# 0_1.net
KiCad netlist of a schematic drawn in EAGLE
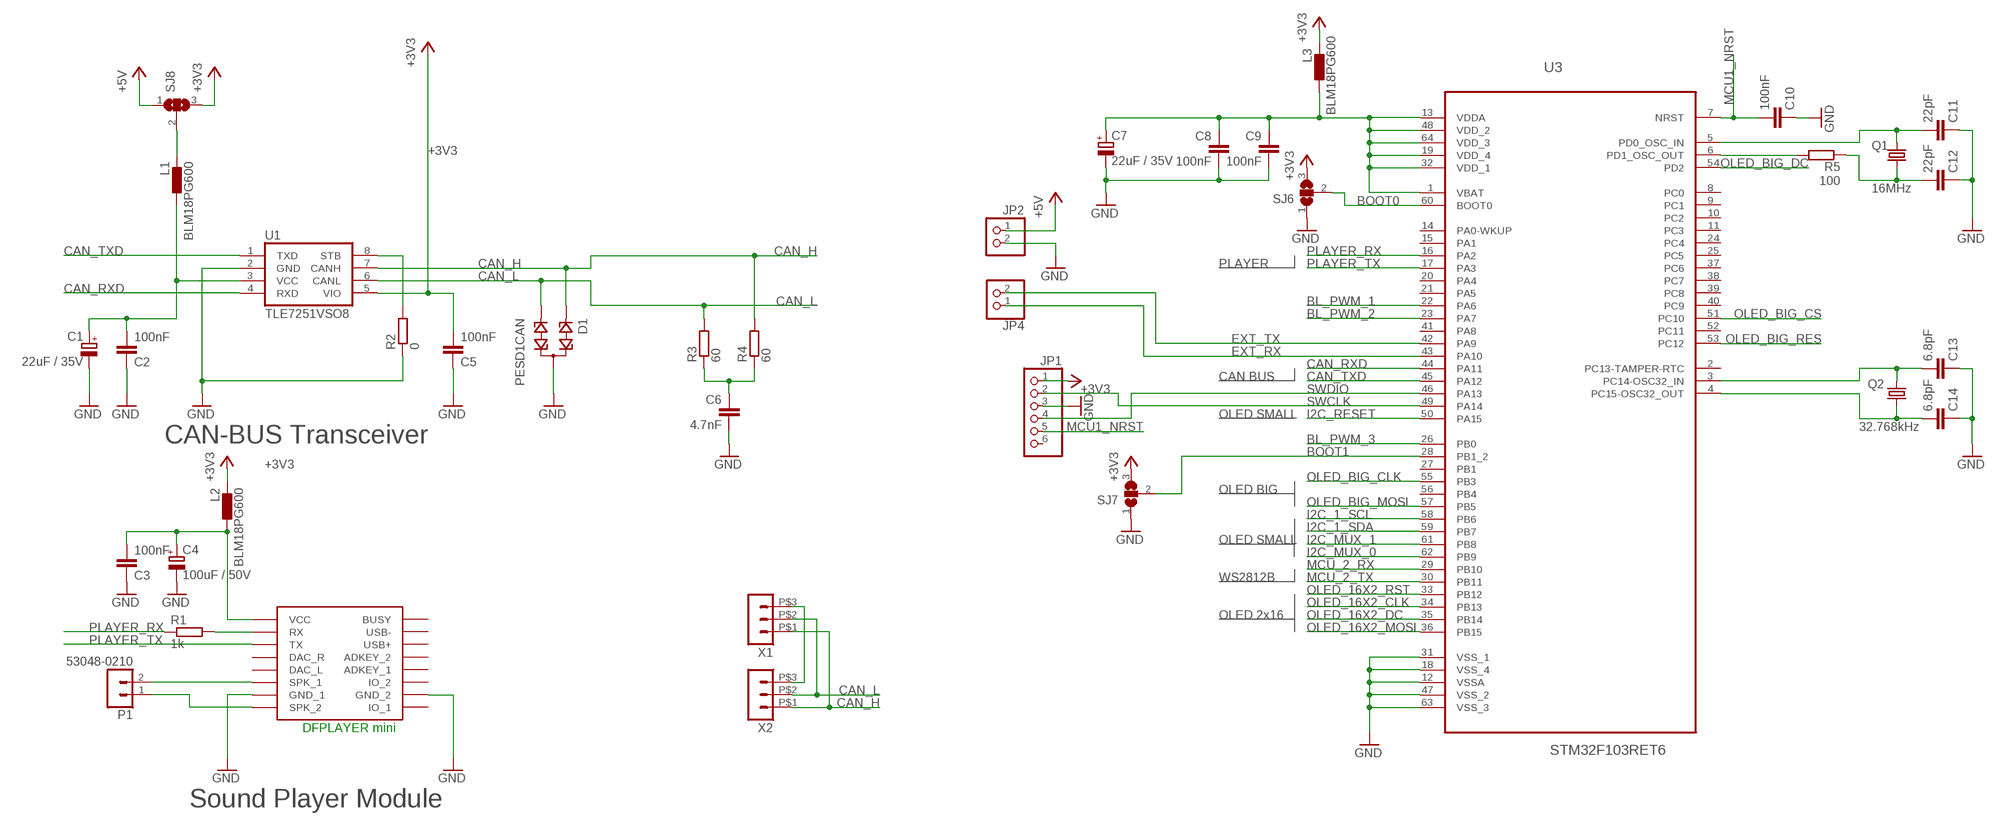
[diagram p0: schematic, sheet 1]
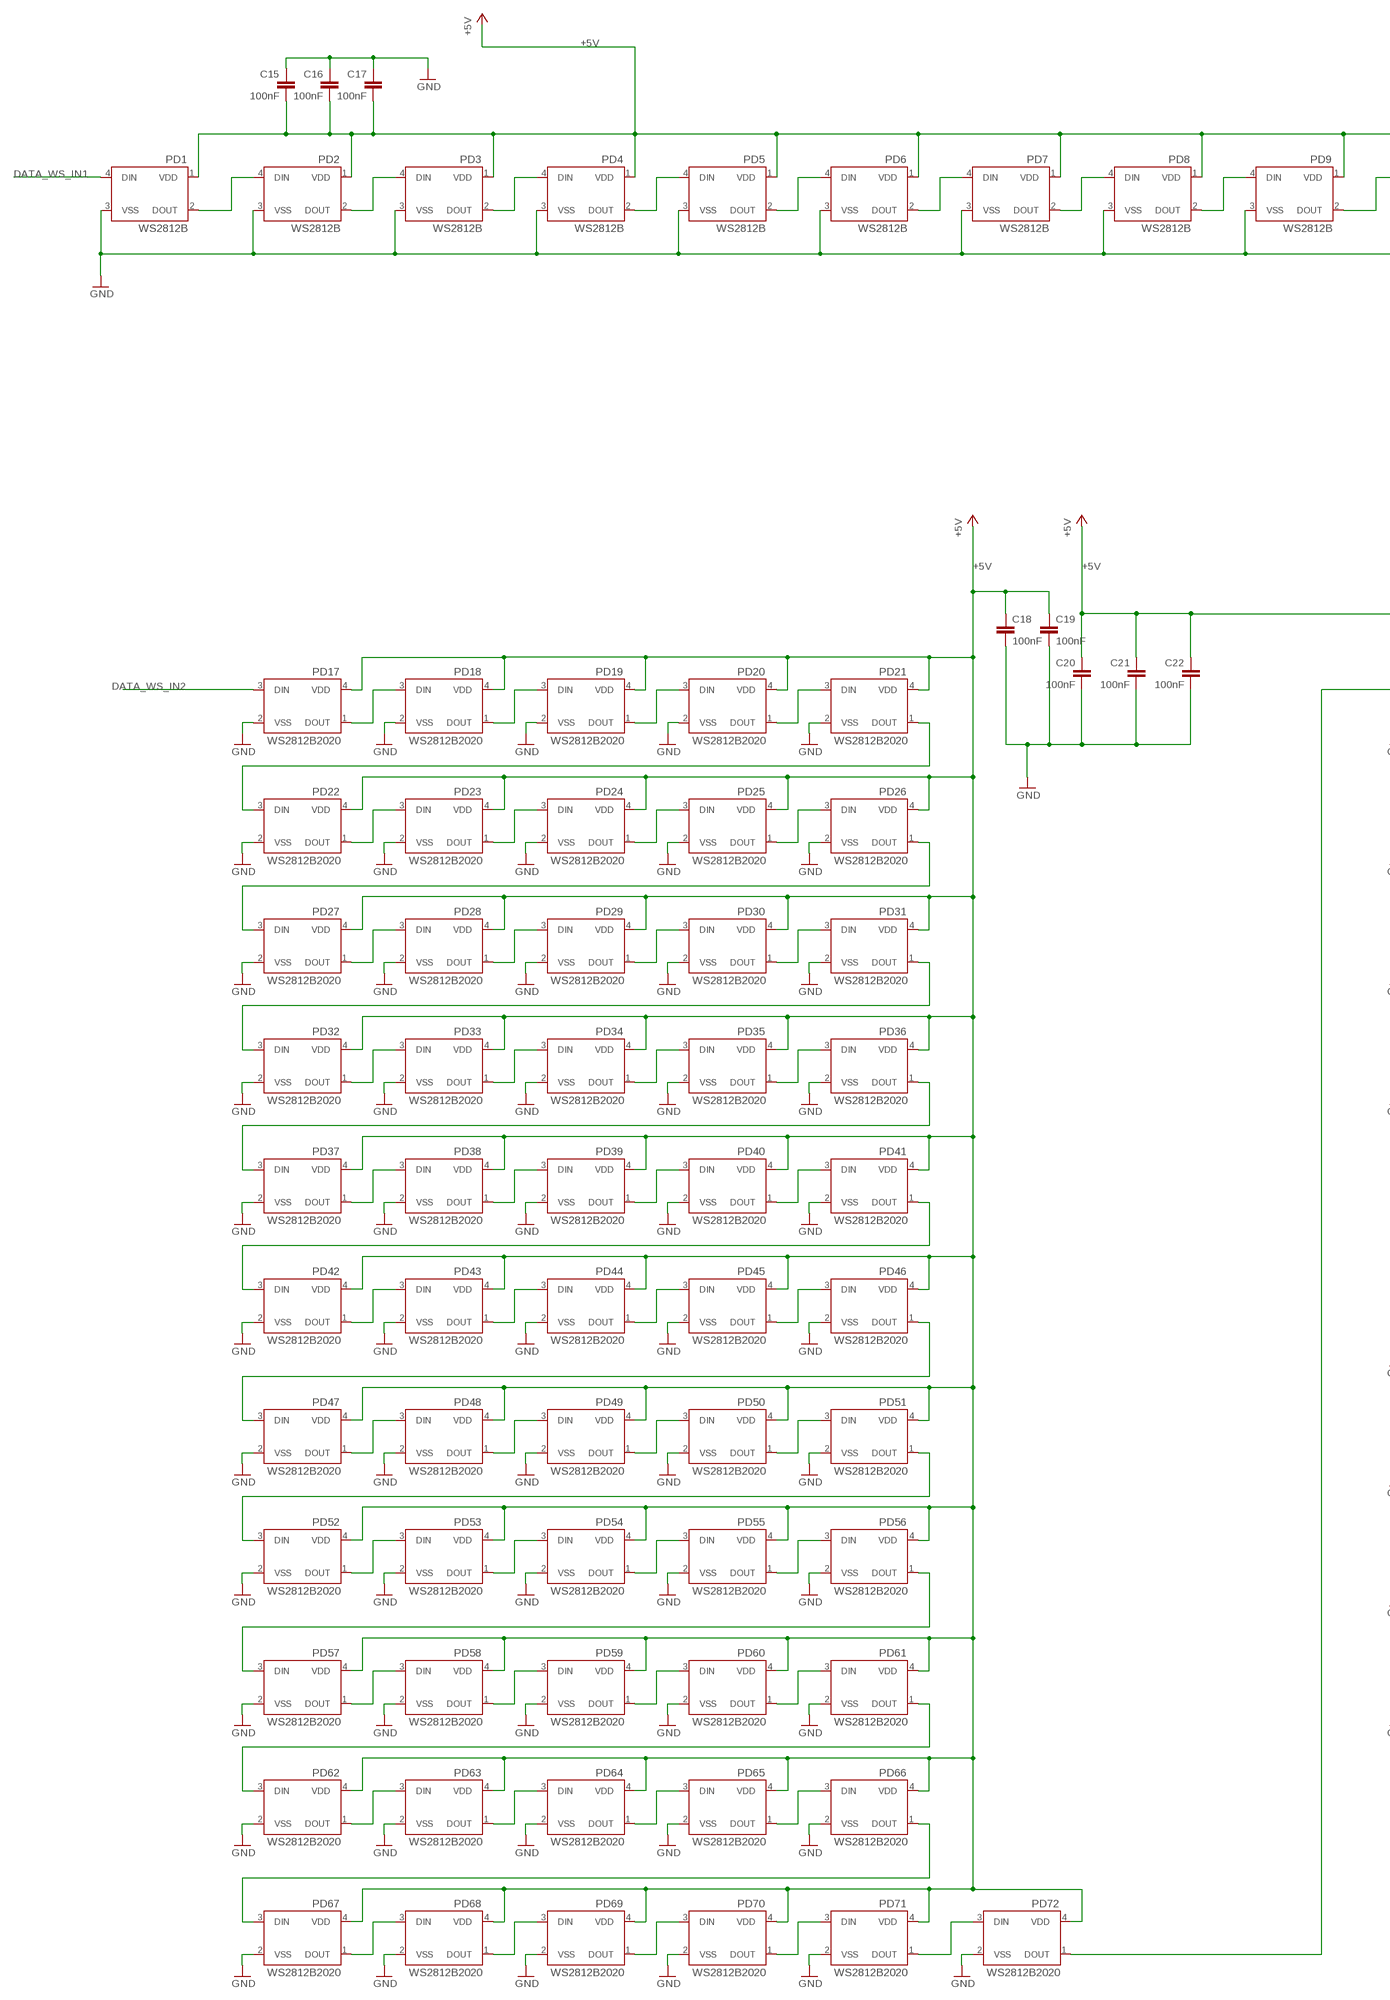
[diagram p1: schematic, sheet 2, part 1 of 2]
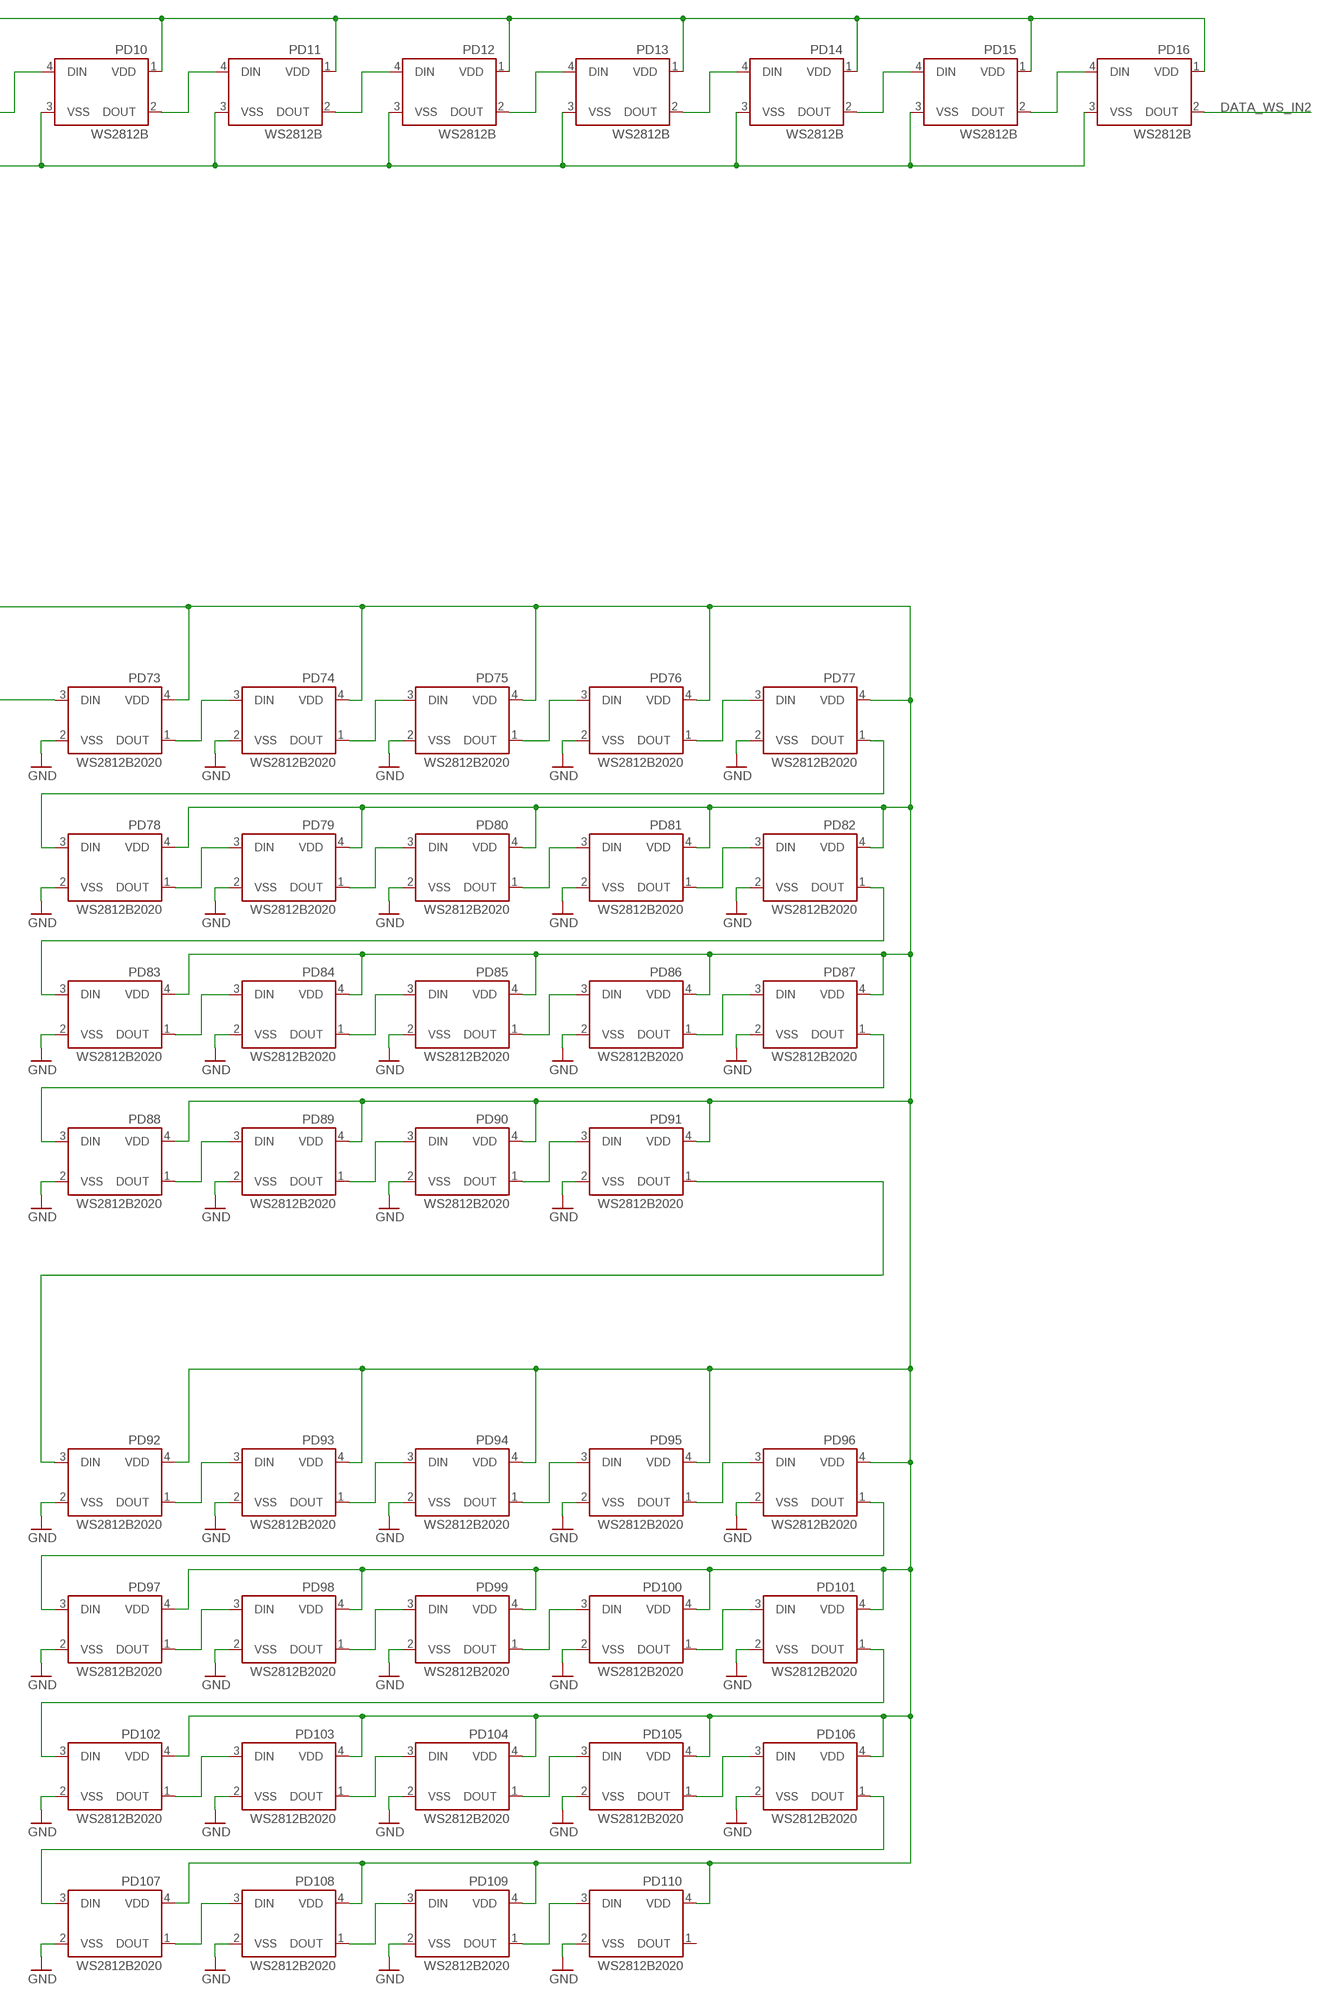
[diagram p2: schematic, sheet 2, part 2 of 2]
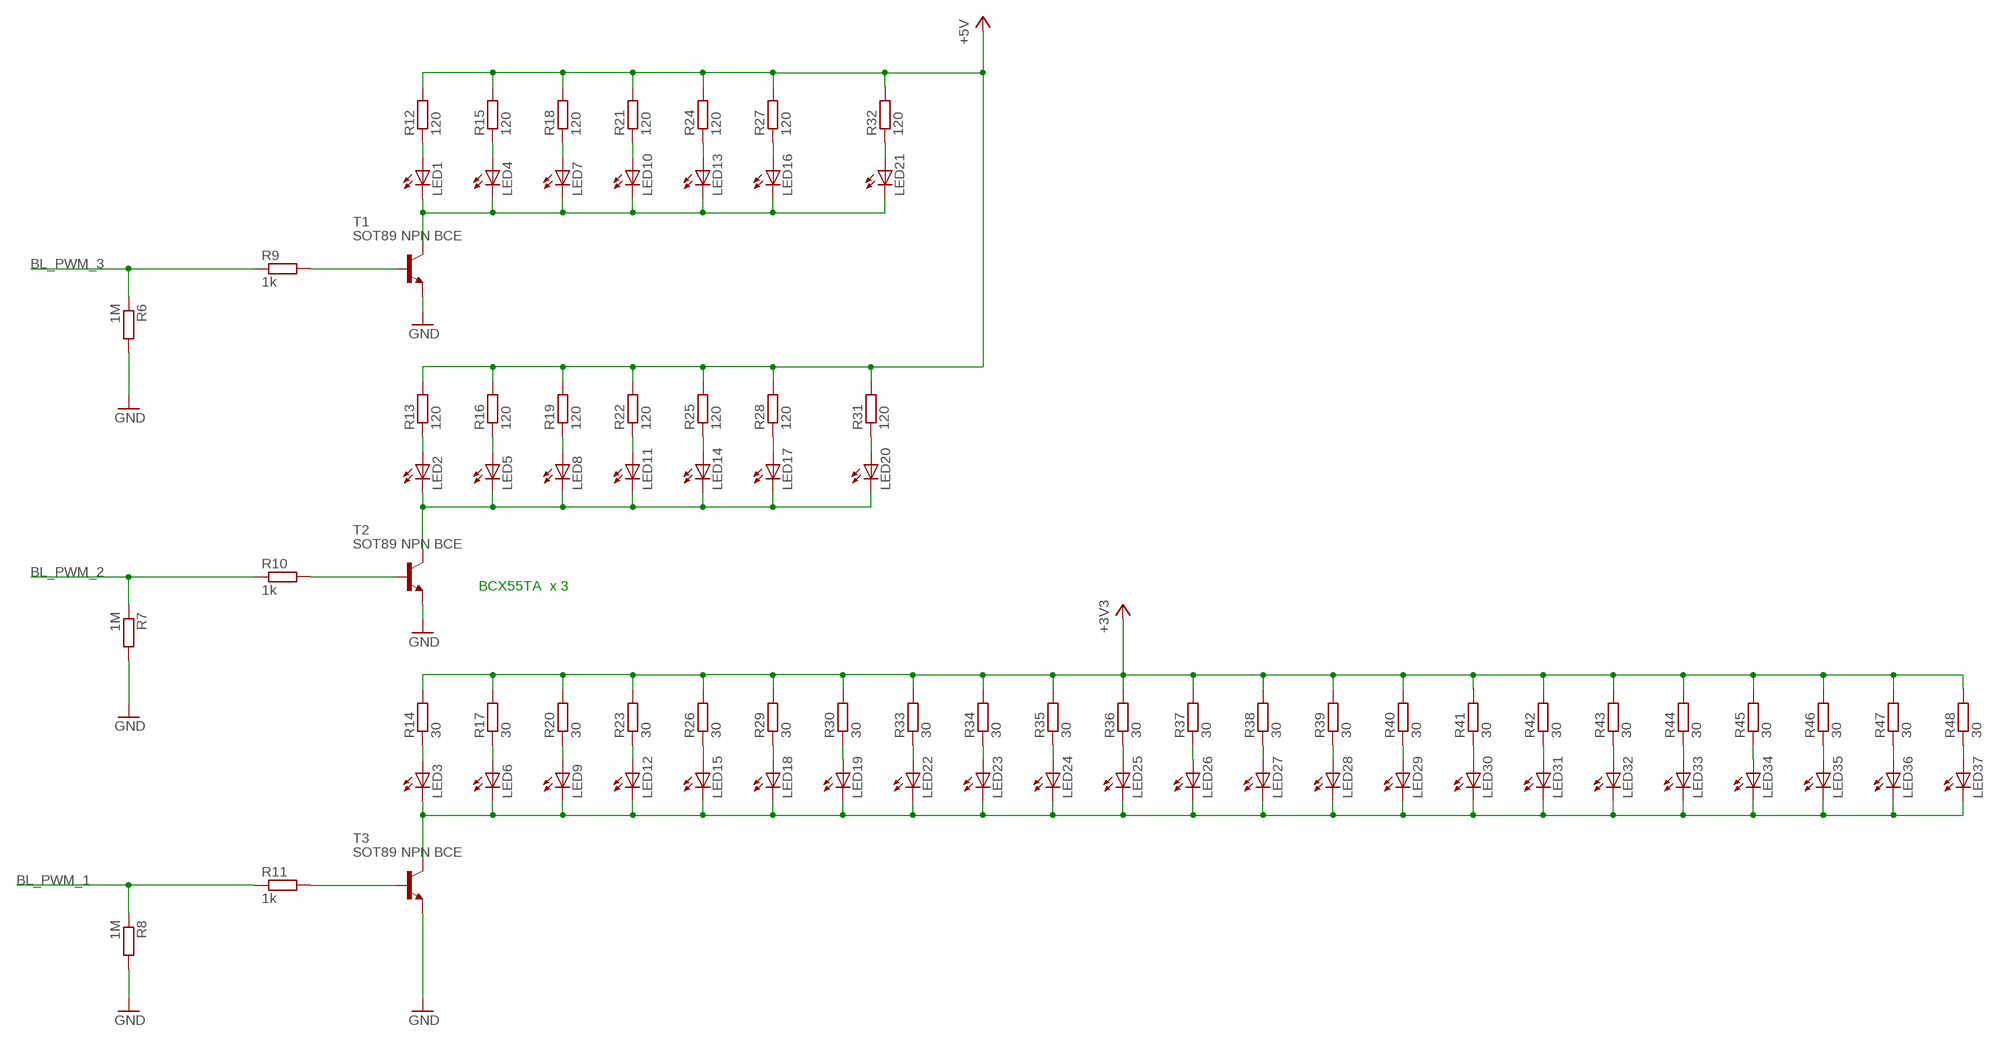
[diagram p3: schematic, sheet 3]
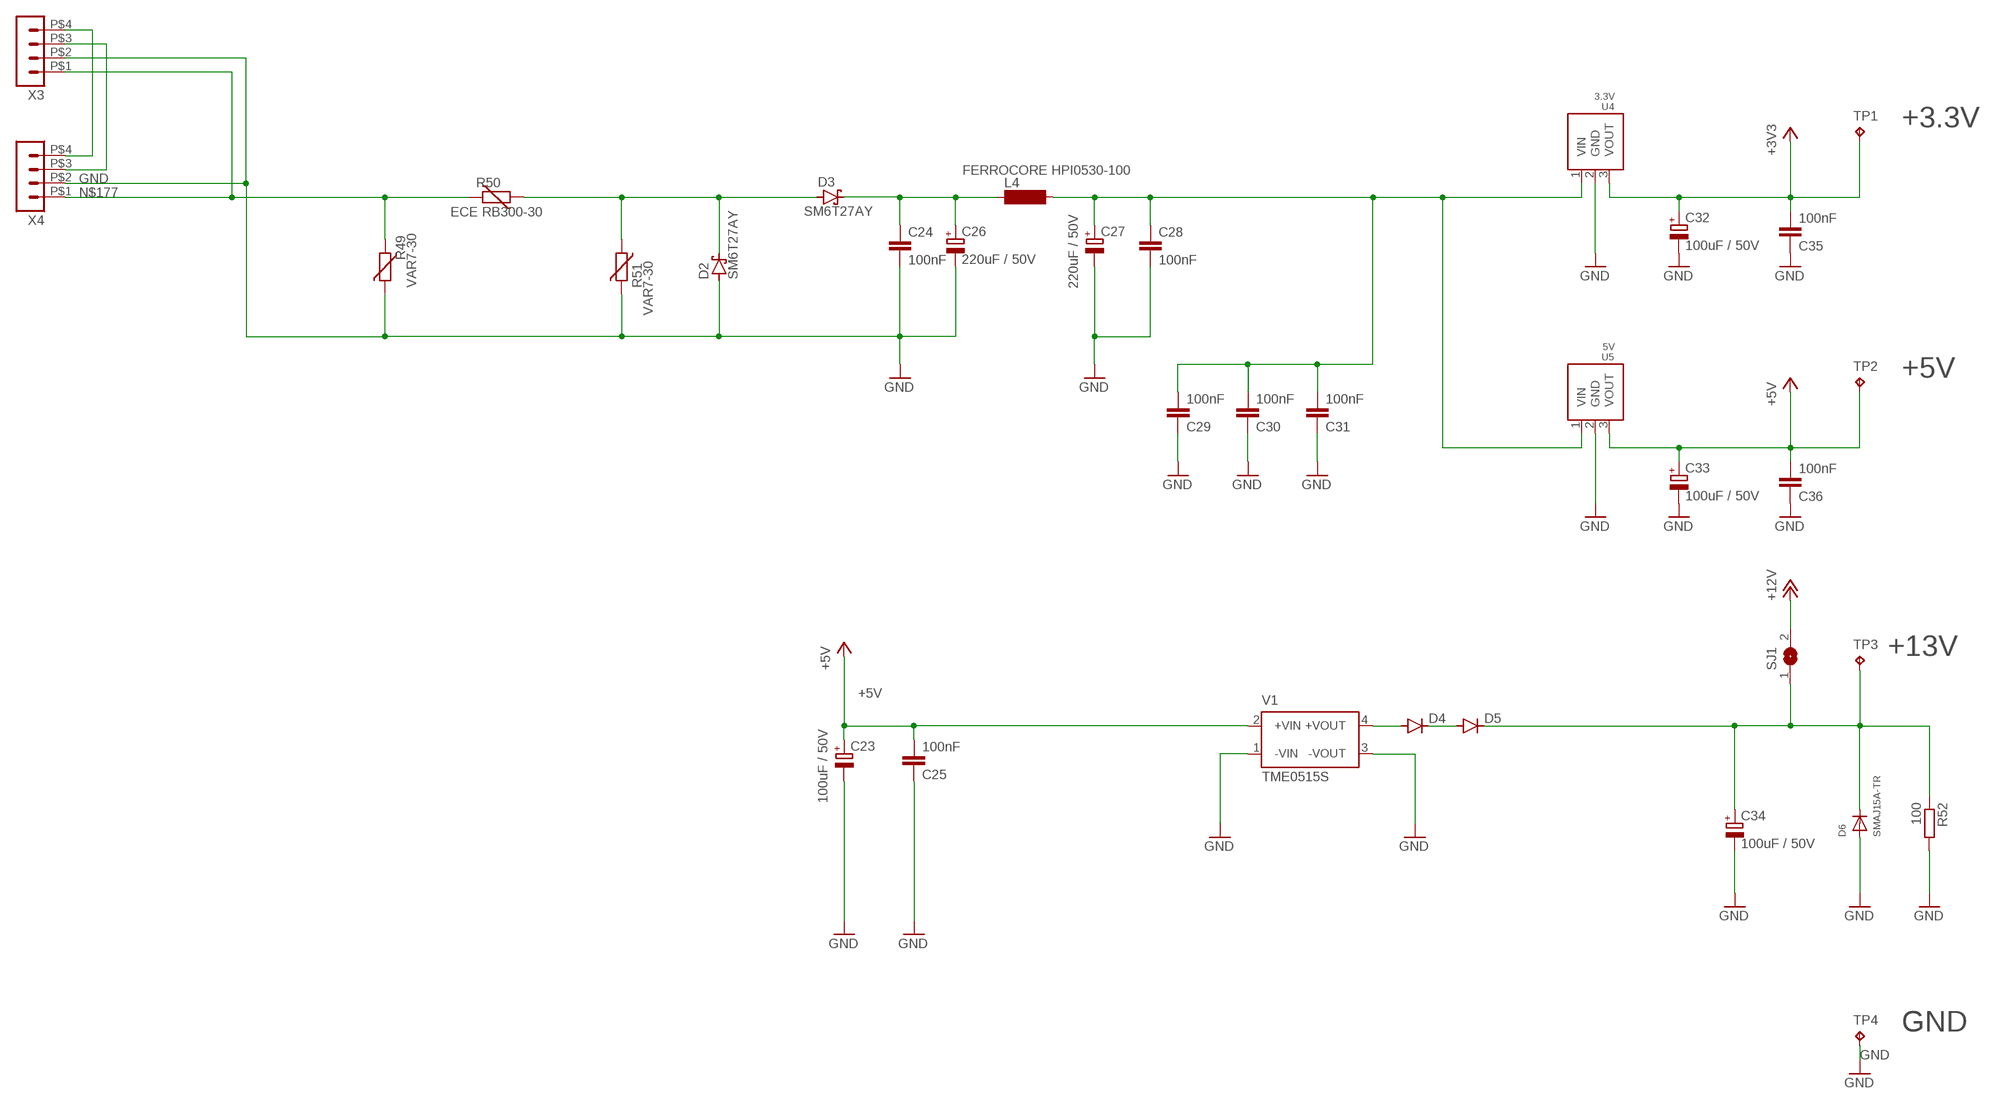
[diagram p4: schematic, sheet 4]
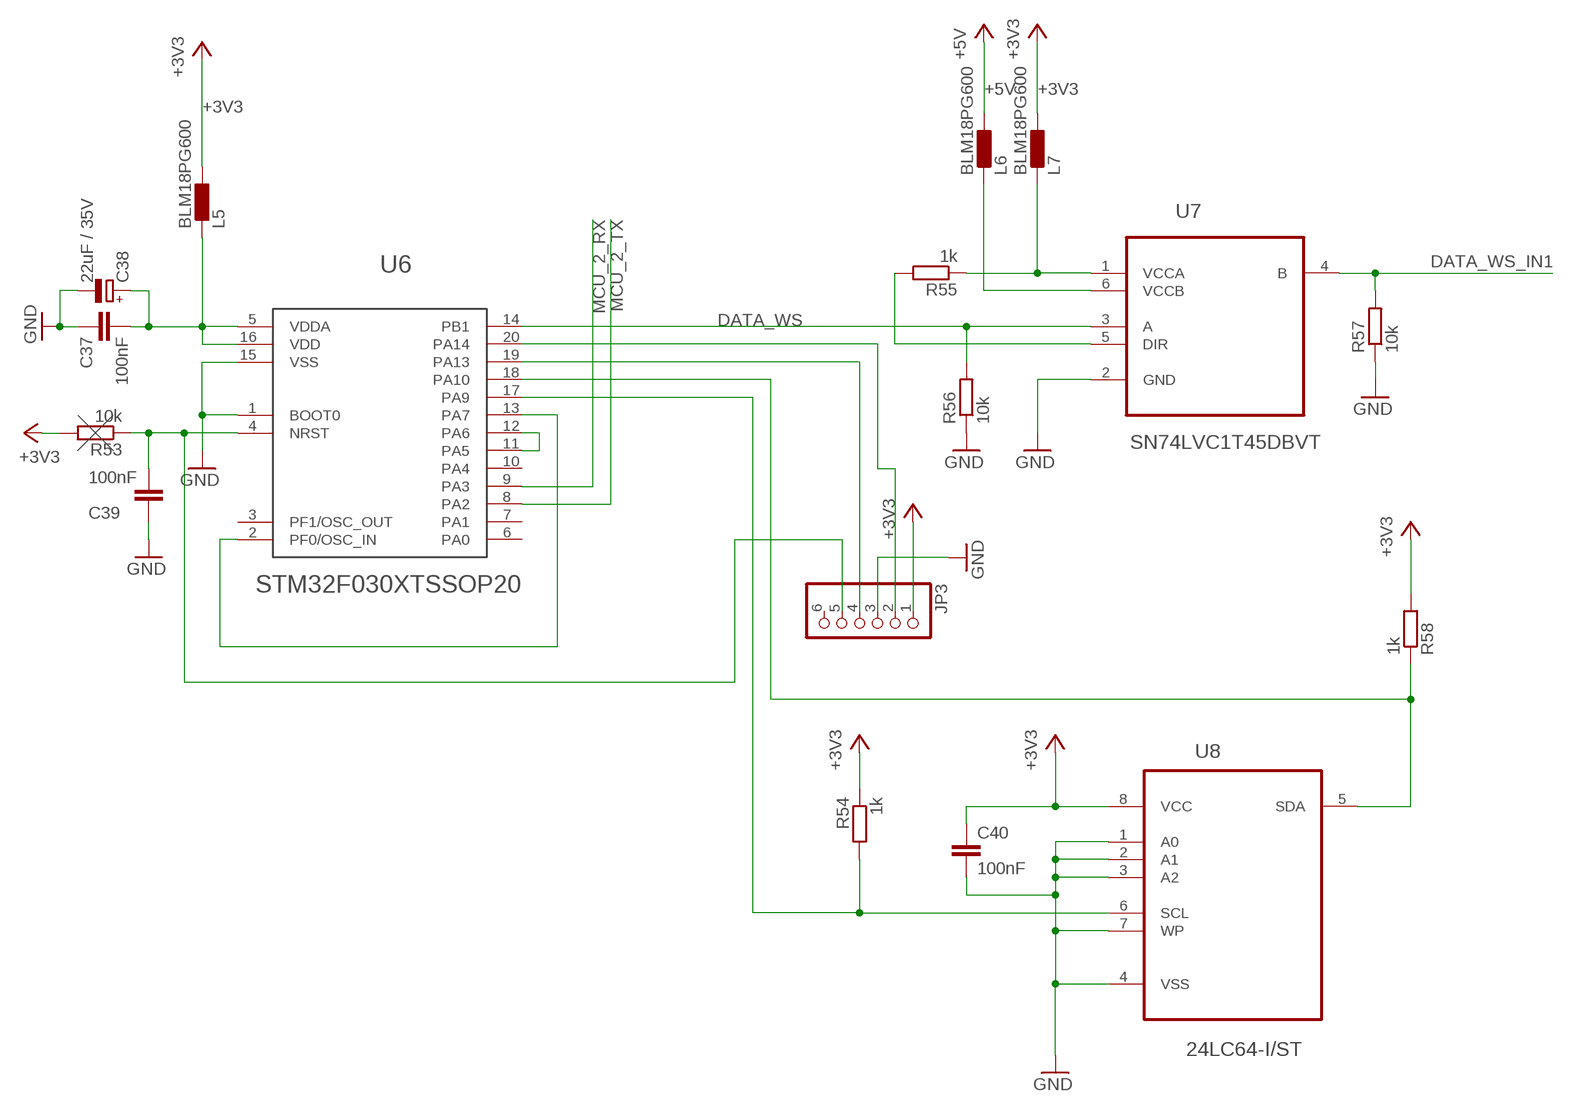
[diagram p5: schematic, sheet 5]
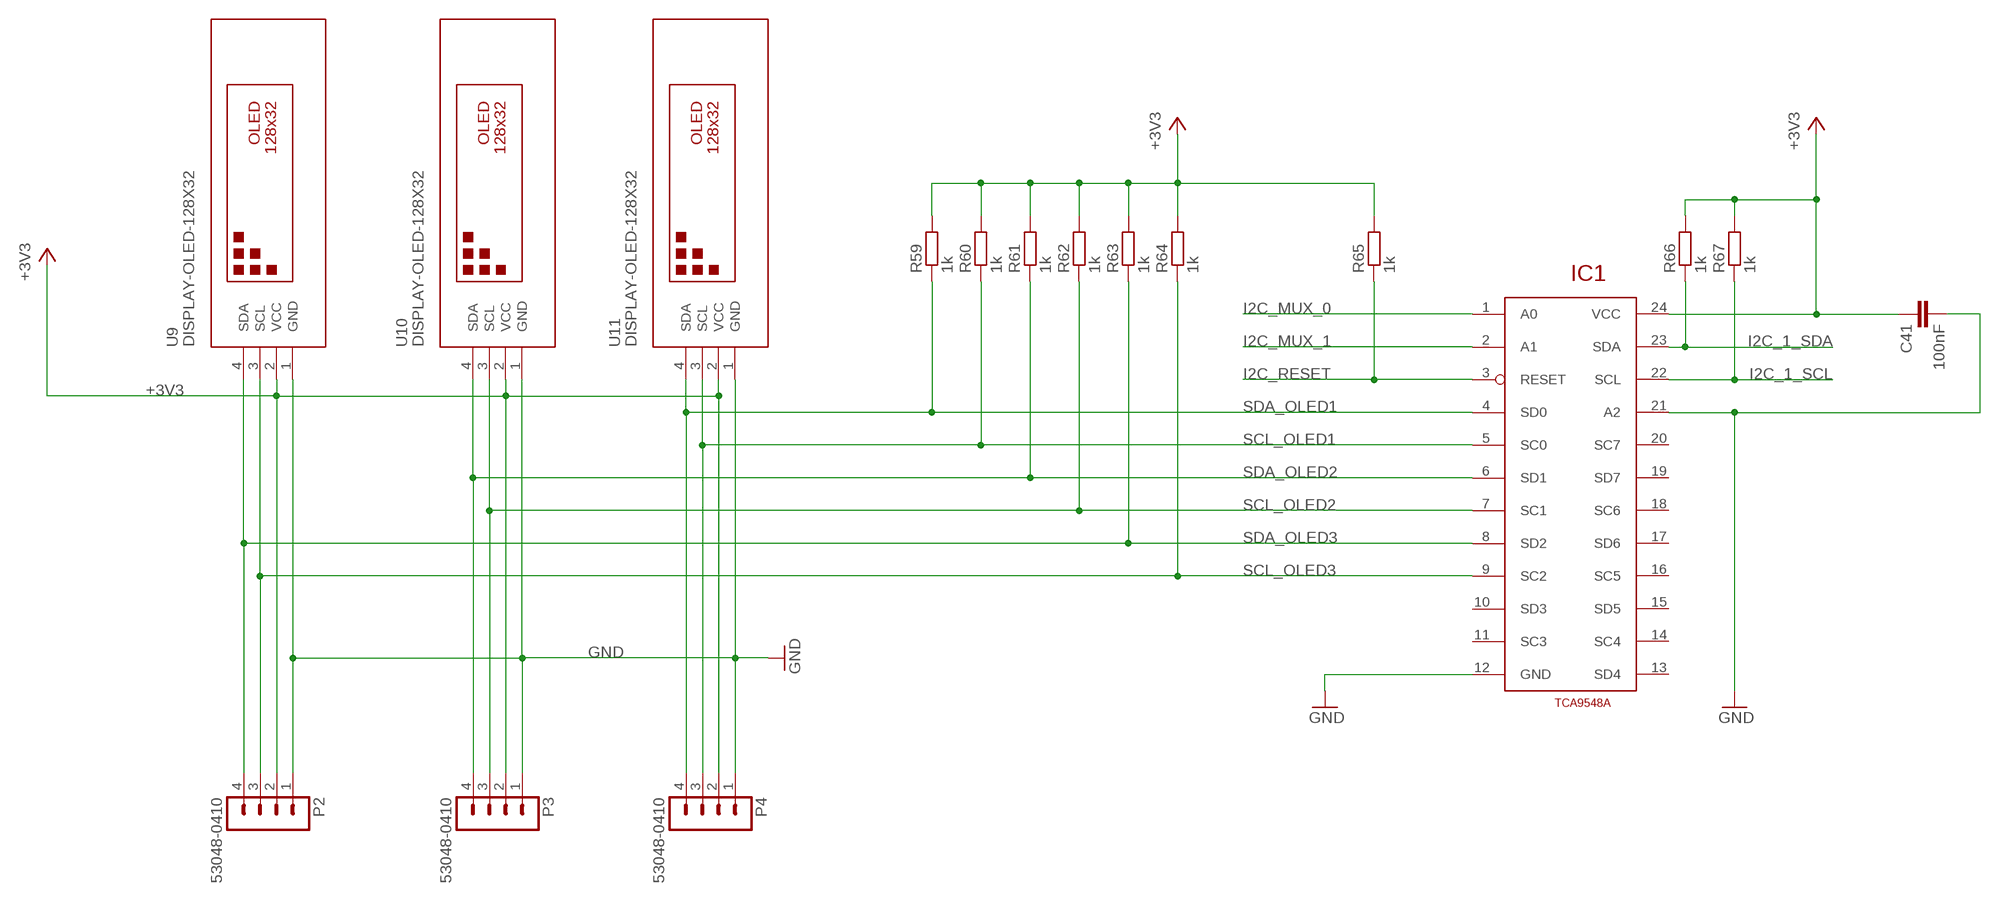
[diagram p6: schematic, sheet 6]
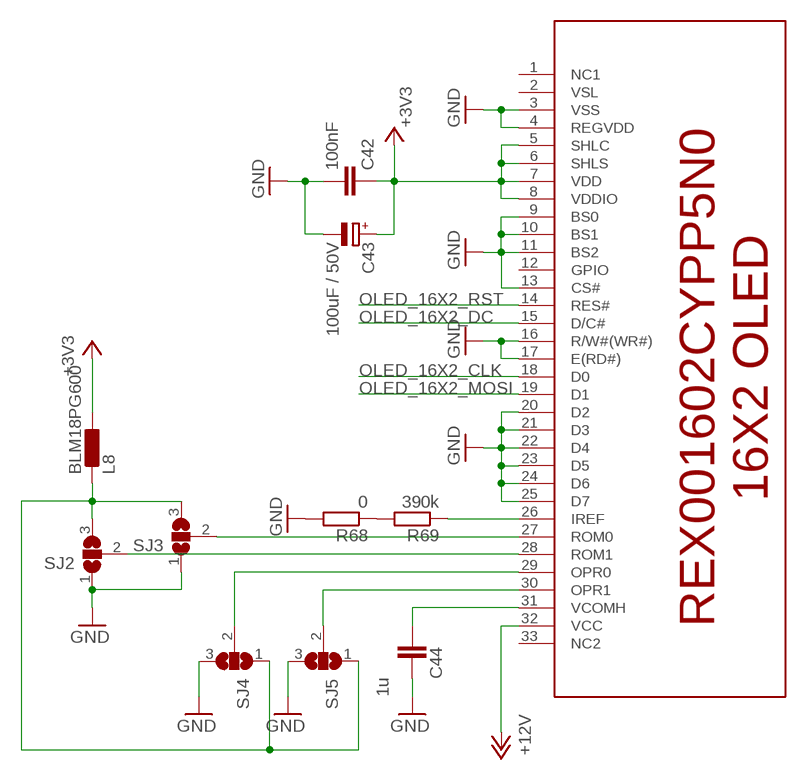
[diagram p7: schematic, sheet 7]
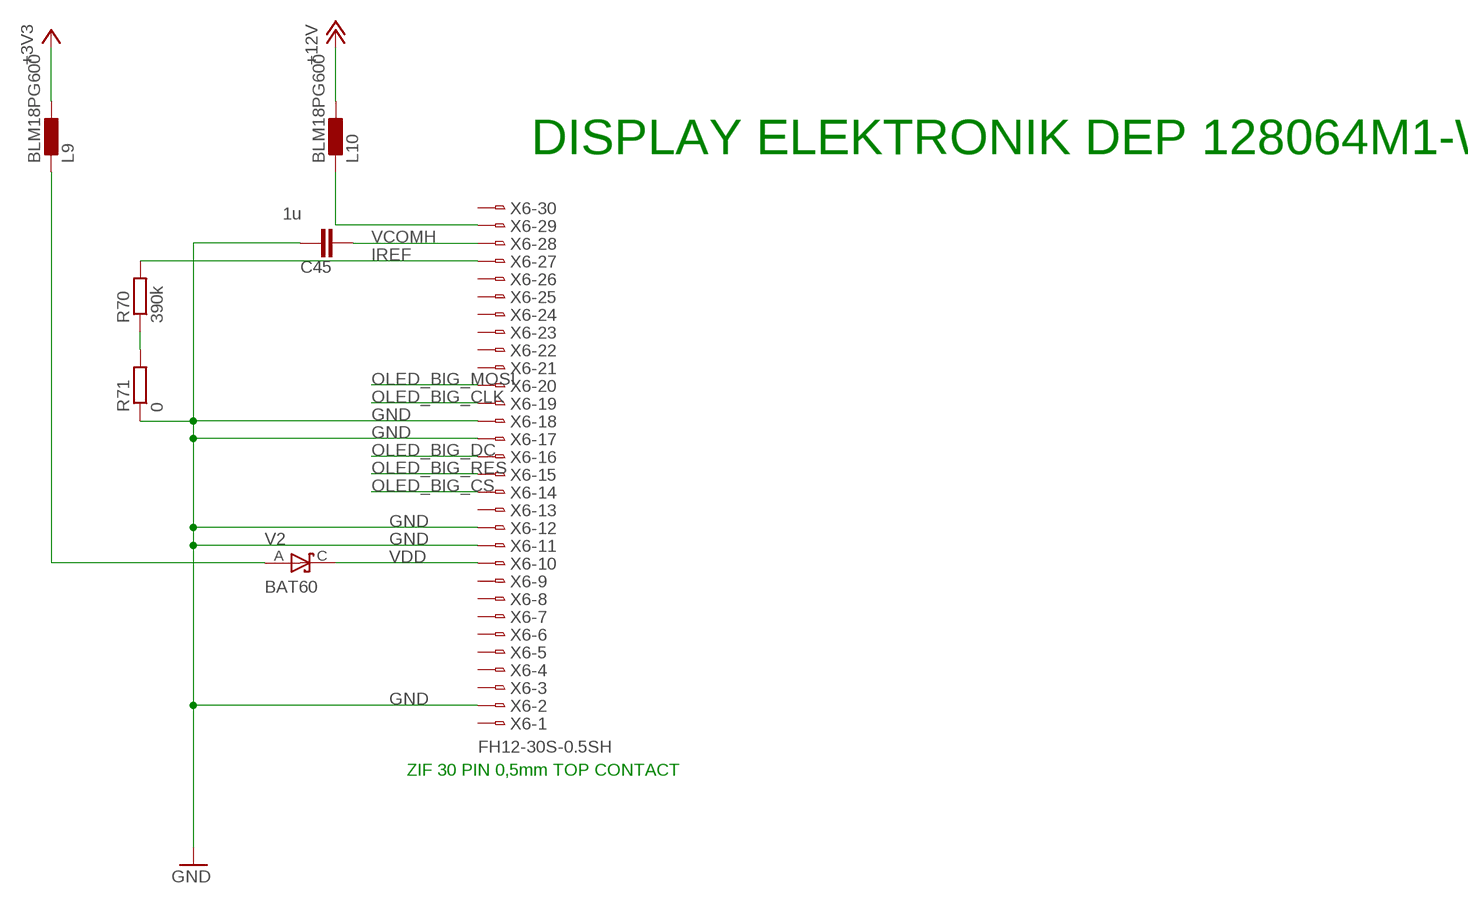
[diagram p8: schematic, sheet 8]

(export (version "E")
  (design (tool "Eeschema 10.0.6"))
  (components
    (comp (ref "C45")
      (value "1u")
      (footprint "eagle-import:C0805K")
      (libsource (lib "eagle-import") (part "C-EUC0805K"))
    )
    (comp (ref "L9")
      (value "BLM18PG600")
      (footprint "eagle-import:L1608")
      (libsource (lib "eagle-import") (part "L_EU_L0603"))
    )
    (comp (ref "L10")
      (value "BLM18PG600")
      (footprint "eagle-import:L1608")
      (libsource (lib "eagle-import") (part "L_EU_L0603"))
    )
    (comp (ref "R70")
      (value "390k")
      (footprint "eagle-import:R0805")
      (libsource (lib "eagle-import") (part "R-EU_R0805"))
    )
    (comp (ref "R71")
      (value "0")
      (footprint "eagle-import:R0805")
      (libsource (lib "eagle-import") (part "R-EU_R0805"))
    )
    (comp (ref "V2")
      (value "BAT60")
      (footprint "eagle-import:SOD323-R")
      (libsource (lib "eagle-import") (part "BAT60"))
    )
    (comp (ref "X6")
      (value "FH12-30S-0.5SH")
      (footprint "eagle-import:FH12-30S-0.5SH")
      (fields (field (name "MPN") "FH12-30S-0.5SH(55)"))
      (libsource (lib "eagle-import") (part "FH12-30S-0.5SH"))
    )
    (comp (ref "C37")
      (value "100nF")
      (footprint "eagle-import:C0805K")
      (libsource (lib "eagle-import") (part "rcl_334_C-EUC0805K"))
    )
    (comp (ref "C38")
      (value "22uF / 35V")
      (footprint "eagle-import:SMC_D")
      (libsource (lib "eagle-import") (part "CPOL-EUSMCD"))
    )
    (comp (ref "C39")
      (value "100nF")
      (footprint "eagle-import:C0805K")
      (libsource (lib "eagle-import") (part "rcl_334_C-EUC0805K"))
    )
    (comp (ref "C40")
      (value "100nF")
      (footprint "eagle-import:C0805K")
      (libsource (lib "eagle-import") (part "rcl_334_C-EUC0805K"))
    )
    (comp (ref "JP3")
      (value "PINHD-1X6")
      (footprint "eagle-import:1X06")
      (libsource (lib "eagle-import") (part "PINHD-1X6"))
    )
    (comp (ref "L5")
      (value "BLM18PG600")
      (footprint "eagle-import:L1608")
      (libsource (lib "eagle-import") (part "L_EU_L0603"))
    )
    (comp (ref "L6")
      (value "BLM18PG600")
      (footprint "eagle-import:L1608")
      (libsource (lib "eagle-import") (part "L_EU_L0603"))
    )
    (comp (ref "L7")
      (value "BLM18PG600")
      (footprint "eagle-import:L1608")
      (libsource (lib "eagle-import") (part "L_EU_L0603"))
    )
    (comp (ref "R53")
      (value "10k")
      (footprint "eagle-import:R0805")
      (libsource (lib "eagle-import") (part "R-EU_R0805"))
    )
    (comp (ref "R54")
      (value "1k")
      (footprint "eagle-import:R0805")
      (libsource (lib "eagle-import") (part "R-EU_R0805"))
    )
    (comp (ref "R55")
      (value "1k")
      (footprint "eagle-import:R0805")
      (libsource (lib "eagle-import") (part "R-EU_R0805"))
    )
    (comp (ref "R56")
      (value "10k")
      (footprint "eagle-import:R0805")
      (libsource (lib "eagle-import") (part "R-EU_R0805"))
    )
    (comp (ref "R57")
      (value "10k")
      (footprint "eagle-import:R0805")
      (libsource (lib "eagle-import") (part "R-EU_R0805"))
    )
    (comp (ref "R58")
      (value "1k")
      (footprint "eagle-import:R0805")
      (libsource (lib "eagle-import") (part "R-EU_R0805"))
    )
    (comp (ref "U6")
      (value "STM32F030XTSSOP20")
      (footprint "eagle-import:TSSOP-20")
      (libsource (lib "eagle-import") (part "STM32F030XTSSOP20"))
    )
    (comp (ref "U7")
      (value "SN74LVC1T45DBVT")
      (footprint "eagle-import:SOT95P280X145-6N")
      (fields (field (name "MF") "Texas Instruments"))
      (libsource (lib "eagle-import") (part "SN74LVC1T45DBVT"))
    )
    (comp (ref "U8")
      (value "24LC64-I/ST")
      (footprint "eagle-import:SOP65P638X110-8N")
      (fields (field (name "MF") "Microchip"))
      (libsource (lib "eagle-import") (part "24LC64-I/ST"))
    )
    (comp (ref "C42")
      (value "100nF")
      (footprint "eagle-import:C0805K")
      (libsource (lib "eagle-import") (part "rcl_334_C-EUC0805K"))
    )
    (comp (ref "C43")
      (value "100uF / 50V")
      (footprint "eagle-import:PANASONIC_F")
      (libsource (lib "eagle-import") (part "CPOL-EUF"))
    )
    (comp (ref "C44")
      (value "1u")
      (footprint "eagle-import:C0805K")
      (libsource (lib "eagle-import") (part "C-EUC0805K"))
    )
    (comp (ref "DISPLAY1")
      (value "REX001602CYPP5N0")
      (footprint "eagle-import:33PIN_LCD16X2")
      (libsource (lib "eagle-import") (part "REX001602CYPP5N0"))
    )
    (comp (ref "L8")
      (value "BLM18PG600")
      (footprint "eagle-import:L1608")
      (libsource (lib "eagle-import") (part "L_EU_L0603"))
    )
    (comp (ref "R68")
      (value "0")
      (footprint "eagle-import:R0805")
      (libsource (lib "eagle-import") (part "R-EU_R0805"))
    )
    (comp (ref "R69")
      (value "390k")
      (footprint "eagle-import:R0805")
      (libsource (lib "eagle-import") (part "R-EU_R0805"))
    )
    (comp (ref "SJ2")
      (value "SJ2W")
      (footprint "eagle-import:SJ_2")
      (libsource (lib "eagle-import") (part "SJ2W"))
    )
    (comp (ref "SJ3")
      (value "SJ2W")
      (footprint "eagle-import:SJ_2")
      (libsource (lib "eagle-import") (part "SJ2W"))
    )
    (comp (ref "SJ4")
      (value "SJ2W")
      (footprint "eagle-import:SJ_2")
      (libsource (lib "eagle-import") (part "SJ2W"))
    )
    (comp (ref "SJ5")
      (value "SJ2W")
      (footprint "eagle-import:SJ_2")
      (libsource (lib "eagle-import") (part "SJ2W"))
    )
    (comp (ref "C23")
      (value "100uF / 50V")
      (footprint "eagle-import:PANASONIC_F")
      (libsource (lib "eagle-import") (part "CPOL-EUF"))
    )
    (comp (ref "C24")
      (value "100nF")
      (footprint "eagle-import:C1206K")
      (libsource (lib "eagle-import") (part "rcl_334_C-EUC1206K"))
    )
    (comp (ref "C25")
      (value "100nF")
      (footprint "eagle-import:C0805K")
      (libsource (lib "eagle-import") (part "rcl_334_C-EUC0805K"))
    )
    (comp (ref "C26")
      (value "220uF / 50V")
      (footprint "eagle-import:PANASONIC_G")
      (libsource (lib "eagle-import") (part "CPOL-EUG"))
    )
    (comp (ref "C27")
      (value "220uF / 50V")
      (footprint "eagle-import:PANASONIC_G")
      (libsource (lib "eagle-import") (part "CPOL-EUG"))
    )
    (comp (ref "C28")
      (value "100nF")
      (footprint "eagle-import:C1206K")
      (libsource (lib "eagle-import") (part "rcl_334_C-EUC1206K"))
    )
    (comp (ref "C29")
      (value "100nF")
      (footprint "eagle-import:C0805K")
      (libsource (lib "eagle-import") (part "rcl_334_C-EUC0805K"))
    )
    (comp (ref "C30")
      (value "100nF")
      (footprint "eagle-import:C0805K")
      (libsource (lib "eagle-import") (part "rcl_334_C-EUC0805K"))
    )
    (comp (ref "C31")
      (value "100nF")
      (footprint "eagle-import:C0805K")
      (libsource (lib "eagle-import") (part "rcl_334_C-EUC0805K"))
    )
    (comp (ref "C32")
      (value "100uF / 50V")
      (footprint "eagle-import:PANASONIC_F")
      (libsource (lib "eagle-import") (part "CPOL-EUF"))
    )
    (comp (ref "C33")
      (value "100uF / 50V")
      (footprint "eagle-import:PANASONIC_F")
      (libsource (lib "eagle-import") (part "CPOL-EUF"))
    )
    (comp (ref "C34")
      (value "100uF / 50V")
      (footprint "eagle-import:PANASONIC_F")
      (libsource (lib "eagle-import") (part "CPOL-EUF"))
    )
    (comp (ref "C35")
      (value "100nF")
      (footprint "eagle-import:C0805K")
      (libsource (lib "eagle-import") (part "rcl_334_C-EUC0805K"))
    )
    (comp (ref "C36")
      (value "100nF")
      (footprint "eagle-import:C0805K")
      (libsource (lib "eagle-import") (part "rcl_334_C-EUC0805K"))
    )
    (comp (ref "D2")
      (value "SM6T27AY")
      (footprint "eagle-import:SMB")
      (libsource (lib "eagle-import") (part "SCHOTTKY-DIODESMD"))
    )
    (comp (ref "D3")
      (value "SM6T27AY")
      (footprint "eagle-import:SMB")
      (libsource (lib "eagle-import") (part "SCHOTTKY-DIODESMD"))
    )
    (comp (ref "D4")
      (value "DIODE-SOD123")
      (footprint "eagle-import:SOD123")
      (libsource (lib "eagle-import") (part "DIODE-SOD123"))
    )
    (comp (ref "D5")
      (value "DIODE-SOD123")
      (footprint "eagle-import:SOD123")
      (libsource (lib "eagle-import") (part "DIODE-SOD123"))
    )
    (comp (ref "D6")
      (value "SMAJ15A-TR")
      (footprint "eagle-import:SMADIODE")
      (libsource (lib "eagle-import") (part "DIODESMA"))
    )
    (comp (ref "L4")
      (value "FERROCORE HPI0530-100")
      (footprint "eagle-import:MS85")
      (libsource (lib "eagle-import") (part "MS85"))
    )
    (comp (ref "R49")
      (value "VAR7-30")
      (footprint "eagle-import:S07K11")
      (libsource (lib "eagle-import") (part "VARISTORS07K11"))
    )
    (comp (ref "R50")
      (value "ECE RB300-30")
      (footprint "eagle-import:S07K11")
      (libsource (lib "eagle-import") (part "VARISTORS07K11"))
    )
    (comp (ref "R51")
      (value "VAR7-30")
      (footprint "eagle-import:S07K11")
      (libsource (lib "eagle-import") (part "VARISTORS07K11"))
    )
    (comp (ref "R52")
      (value "100")
      (footprint "eagle-import:R0805")
      (libsource (lib "eagle-import") (part "R-EU_R0805"))
    )
    (comp (ref "SJ1") (value "SJ") (footprint "eagle-import:SJ") (libsource (lib "eagle-import") (part "SJ")))
    (comp (ref "TP1")
      (value "3V3")
      (footprint "eagle-import:TP18SQ")
      (libsource (lib "eagle-import") (part "TPTP18SQ"))
    )
    (comp (ref "TP2")
      (value "5V")
      (footprint "eagle-import:TP18SQ")
      (libsource (lib "eagle-import") (part "TPTP18SQ"))
    )
    (comp (ref "TP3")
      (value "12V")
      (footprint "eagle-import:TP18SQ")
      (libsource (lib "eagle-import") (part "TPTP18SQ"))
    )
    (comp (ref "TP4")
      (value "GND")
      (footprint "eagle-import:TP18SQ")
      (libsource (lib "eagle-import") (part "TPTP18SQ"))
    )
    (comp (ref "U4")
      (value "3.3V")
      (footprint "eagle-import:FDSM-173XXXX42")
      (libsource (lib "eagle-import") (part "FDSM_SIP-3_173010542"))
    )
    (comp (ref "U5")
      (value "5V")
      (footprint "eagle-import:FDSM-173XXXX42")
      (libsource (lib "eagle-import") (part "FDSM_SIP-3_173010542"))
    )
    (comp (ref "V1")
      (value "TME0515S")
      (footprint "eagle-import:TME")
      (fields (field (name "MPN") "TME 0515S"))
      (libsource (lib "eagle-import") (part "TME?0515S"))
    )
    (comp (ref "X3")
      (value "HEADER_POS4_43045-0412")
      (footprint "eagle-import:43045-0412")
      (libsource (lib "eagle-import") (part "HEADER_POS4_?43045-0412"))
    )
    (comp (ref "X4")
      (value "HEADER_POS4_43045-0412")
      (footprint "eagle-import:43045-0412")
      (libsource (lib "eagle-import") (part "HEADER_POS4_?43045-0412"))
    )
    (comp (ref "C41")
      (value "100nF")
      (footprint "eagle-import:C0805K")
      (libsource (lib "eagle-import") (part "rcl_334_C-EUC0805K"))
    )
    (comp (ref "IC1")
      (value "TCA9548A")
      (footprint "eagle-import:TSSOP24")
      (libsource (lib "eagle-import") (part "TCA9548A"))
    )
    (comp (ref "P2")
      (value "53048-0410")
      (footprint "eagle-import:53048-0410")
      (libsource (lib "eagle-import") (part "53048-0410"))
    )
    (comp (ref "P3")
      (value "53048-0410")
      (footprint "eagle-import:53048-0410")
      (libsource (lib "eagle-import") (part "53048-0410"))
    )
    (comp (ref "P4")
      (value "53048-0410")
      (footprint "eagle-import:53048-0410")
      (libsource (lib "eagle-import") (part "53048-0410"))
    )
    (comp (ref "R59")
      (value "1k")
      (footprint "eagle-import:R0805")
      (libsource (lib "eagle-import") (part "R-EU_R0805"))
    )
    (comp (ref "R60")
      (value "1k")
      (footprint "eagle-import:R0805")
      (libsource (lib "eagle-import") (part "R-EU_R0805"))
    )
    (comp (ref "R61")
      (value "1k")
      (footprint "eagle-import:R0805")
      (libsource (lib "eagle-import") (part "R-EU_R0805"))
    )
    (comp (ref "R62")
      (value "1k")
      (footprint "eagle-import:R0805")
      (libsource (lib "eagle-import") (part "R-EU_R0805"))
    )
    (comp (ref "R63")
      (value "1k")
      (footprint "eagle-import:R0805")
      (libsource (lib "eagle-import") (part "R-EU_R0805"))
    )
    (comp (ref "R64")
      (value "1k")
      (footprint "eagle-import:R0805")
      (libsource (lib "eagle-import") (part "R-EU_R0805"))
    )
    (comp (ref "R65")
      (value "1k")
      (footprint "eagle-import:R0805")
      (libsource (lib "eagle-import") (part "R-EU_R0805"))
    )
    (comp (ref "R66")
      (value "1k")
      (footprint "eagle-import:R0805")
      (libsource (lib "eagle-import") (part "R-EU_R0805"))
    )
    (comp (ref "R67")
      (value "1k")
      (footprint "eagle-import:R0805")
      (libsource (lib "eagle-import") (part "R-EU_R0805"))
    )
    (comp (ref "U9")
      (value "DISPLAY-OLED-128X32")
      (footprint "eagle-import:DISPLAY-OLED-128X32")
      (libsource (lib "eagle-import") (part "DISPLAY-OLED-128X32"))
    )
    (comp (ref "U10")
      (value "DISPLAY-OLED-128X32")
      (footprint "eagle-import:DISPLAY-OLED-128X32")
      (libsource (lib "eagle-import") (part "DISPLAY-OLED-128X32"))
    )
    (comp (ref "U11")
      (value "DISPLAY-OLED-128X32")
      (footprint "eagle-import:DISPLAY-OLED-128X32")
      (libsource (lib "eagle-import") (part "DISPLAY-OLED-128X32"))
    )
    (comp (ref "LED1")
      (value "LEDCHIPLED_0603")
      (footprint "eagle-import:CHIPLED_0603")
      (libsource (lib "eagle-import") (part "LEDCHIPLED_0603"))
    )
    (comp (ref "LED2")
      (value "LEDCHIPLED_0603")
      (footprint "eagle-import:CHIPLED_0603")
      (libsource (lib "eagle-import") (part "LEDCHIPLED_0603"))
    )
    (comp (ref "LED3")
      (value "LEDCHIPLED_0603")
      (footprint "eagle-import:CHIPLED_0603")
      (libsource (lib "eagle-import") (part "LEDCHIPLED_0603"))
    )
    (comp (ref "LED4")
      (value "LEDCHIPLED_0603")
      (footprint "eagle-import:CHIPLED_0603")
      (libsource (lib "eagle-import") (part "LEDCHIPLED_0603"))
    )
    (comp (ref "LED5")
      (value "LEDCHIPLED_0603")
      (footprint "eagle-import:CHIPLED_0603")
      (libsource (lib "eagle-import") (part "LEDCHIPLED_0603"))
    )
    (comp (ref "LED6")
      (value "LEDCHIPLED_0603")
      (footprint "eagle-import:CHIPLED_0603")
      (libsource (lib "eagle-import") (part "LEDCHIPLED_0603"))
    )
    (comp (ref "LED7")
      (value "LEDCHIPLED_0603")
      (footprint "eagle-import:CHIPLED_0603")
      (libsource (lib "eagle-import") (part "LEDCHIPLED_0603"))
    )
    (comp (ref "LED8")
      (value "LEDCHIPLED_0603")
      (footprint "eagle-import:CHIPLED_0603")
      (libsource (lib "eagle-import") (part "LEDCHIPLED_0603"))
    )
    (comp (ref "LED9")
      (value "LEDCHIPLED_0603")
      (footprint "eagle-import:CHIPLED_0603")
      (libsource (lib "eagle-import") (part "LEDCHIPLED_0603"))
    )
    (comp (ref "LED10")
      (value "LEDCHIPLED_0603")
      (footprint "eagle-import:CHIPLED_0603")
      (libsource (lib "eagle-import") (part "LEDCHIPLED_0603"))
    )
    (comp (ref "LED11")
      (value "LEDCHIPLED_0603")
      (footprint "eagle-import:CHIPLED_0603")
      (libsource (lib "eagle-import") (part "LEDCHIPLED_0603"))
    )
    (comp (ref "LED12")
      (value "LEDCHIPLED_0603")
      (footprint "eagle-import:CHIPLED_0603")
      (libsource (lib "eagle-import") (part "LEDCHIPLED_0603"))
    )
    (comp (ref "LED13")
      (value "LEDCHIPLED_0603")
      (footprint "eagle-import:CHIPLED_0603")
      (libsource (lib "eagle-import") (part "LEDCHIPLED_0603"))
    )
    (comp (ref "LED14")
      (value "LEDCHIPLED_0603")
      (footprint "eagle-import:CHIPLED_0603")
      (libsource (lib "eagle-import") (part "LEDCHIPLED_0603"))
    )
    (comp (ref "LED15")
      (value "LEDCHIPLED_0603")
      (footprint "eagle-import:CHIPLED_0603")
      (libsource (lib "eagle-import") (part "LEDCHIPLED_0603"))
    )
    (comp (ref "LED16")
      (value "LEDCHIPLED_0603")
      (footprint "eagle-import:CHIPLED_0603")
      (libsource (lib "eagle-import") (part "LEDCHIPLED_0603"))
    )
    (comp (ref "LED17")
      (value "LEDCHIPLED_0603")
      (footprint "eagle-import:CHIPLED_0603")
      (libsource (lib "eagle-import") (part "LEDCHIPLED_0603"))
    )
    (comp (ref "LED18")
      (value "LEDCHIPLED_0603")
      (footprint "eagle-import:CHIPLED_0603")
      (libsource (lib "eagle-import") (part "LEDCHIPLED_0603"))
    )
    (comp (ref "LED19")
      (value "LEDCHIPLED_0603")
      (footprint "eagle-import:CHIPLED_0603")
      (libsource (lib "eagle-import") (part "LEDCHIPLED_0603"))
    )
    (comp (ref "LED20")
      (value "LEDCHIPLED_0603")
      (footprint "eagle-import:CHIPLED_0603")
      (libsource (lib "eagle-import") (part "LEDCHIPLED_0603"))
    )
    (comp (ref "LED21")
      (value "LEDCHIPLED_0603")
      (footprint "eagle-import:CHIPLED_0603")
      (libsource (lib "eagle-import") (part "LEDCHIPLED_0603"))
    )
    (comp (ref "LED22")
      (value "LEDCHIPLED_0603")
      (footprint "eagle-import:CHIPLED_0603")
      (libsource (lib "eagle-import") (part "LEDCHIPLED_0603"))
    )
    (comp (ref "LED23")
      (value "LEDCHIPLED_0603")
      (footprint "eagle-import:CHIPLED_0603")
      (libsource (lib "eagle-import") (part "LEDCHIPLED_0603"))
    )
    (comp (ref "LED24")
      (value "LEDCHIPLED_0603")
      (footprint "eagle-import:CHIPLED_0603")
      (libsource (lib "eagle-import") (part "LEDCHIPLED_0603"))
    )
    (comp (ref "LED25")
      (value "LEDCHIPLED_0603")
      (footprint "eagle-import:CHIPLED_0603")
      (libsource (lib "eagle-import") (part "LEDCHIPLED_0603"))
    )
    (comp (ref "LED26")
      (value "LEDCHIPLED_0603")
      (footprint "eagle-import:CHIPLED_0603")
      (libsource (lib "eagle-import") (part "LEDCHIPLED_0603"))
    )
    (comp (ref "LED27")
      (value "LEDCHIPLED_0603")
      (footprint "eagle-import:CHIPLED_0603")
      (libsource (lib "eagle-import") (part "LEDCHIPLED_0603"))
    )
    (comp (ref "LED28")
      (value "LEDCHIPLED_0603")
      (footprint "eagle-import:CHIPLED_0603")
      (libsource (lib "eagle-import") (part "LEDCHIPLED_0603"))
    )
    (comp (ref "LED29")
      (value "LEDCHIPLED_0603")
      (footprint "eagle-import:CHIPLED_0603")
      (libsource (lib "eagle-import") (part "LEDCHIPLED_0603"))
    )
    (comp (ref "LED30")
      (value "LEDCHIPLED_0603")
      (footprint "eagle-import:CHIPLED_0603")
      (libsource (lib "eagle-import") (part "LEDCHIPLED_0603"))
    )
    (comp (ref "LED31")
      (value "LEDCHIPLED_0603")
      (footprint "eagle-import:CHIPLED_0603")
      (libsource (lib "eagle-import") (part "LEDCHIPLED_0603"))
    )
    (comp (ref "LED32")
      (value "LEDCHIPLED_0603")
      (footprint "eagle-import:CHIPLED_0603")
      (libsource (lib "eagle-import") (part "LEDCHIPLED_0603"))
    )
    (comp (ref "LED33")
      (value "LEDCHIPLED_0603")
      (footprint "eagle-import:CHIPLED_0603")
      (libsource (lib "eagle-import") (part "LEDCHIPLED_0603"))
    )
    (comp (ref "LED34")
      (value "LEDCHIPLED_0603")
      (footprint "eagle-import:CHIPLED_0603")
      (libsource (lib "eagle-import") (part "LEDCHIPLED_0603"))
    )
    (comp (ref "LED35")
      (value "LEDCHIPLED_0603")
      (footprint "eagle-import:CHIPLED_0603")
      (libsource (lib "eagle-import") (part "LEDCHIPLED_0603"))
    )
    (comp (ref "LED36")
      (value "LEDCHIPLED_0603")
      (footprint "eagle-import:CHIPLED_0603")
      (libsource (lib "eagle-import") (part "LEDCHIPLED_0603"))
    )
    (comp (ref "LED37")
      (value "LEDCHIPLED_0603")
      (footprint "eagle-import:CHIPLED_0603")
      (libsource (lib "eagle-import") (part "LEDCHIPLED_0603"))
    )
    (comp (ref "R6")
      (value "1M")
      (footprint "eagle-import:R0805")
      (libsource (lib "eagle-import") (part "R-EU_R0805"))
    )
    (comp (ref "R7")
      (value "1M")
      (footprint "eagle-import:R0805")
      (libsource (lib "eagle-import") (part "R-EU_R0805"))
    )
    (comp (ref "R8")
      (value "1M")
      (footprint "eagle-import:R0805")
      (libsource (lib "eagle-import") (part "R-EU_R0805"))
    )
    (comp (ref "R9")
      (value "1k")
      (footprint "eagle-import:R0805")
      (libsource (lib "eagle-import") (part "R-EU_R0805"))
    )
    (comp (ref "R10")
      (value "1k")
      (footprint "eagle-import:R0805")
      (libsource (lib "eagle-import") (part "R-EU_R0805"))
    )
    (comp (ref "R11")
      (value "1k")
      (footprint "eagle-import:R0805")
      (libsource (lib "eagle-import") (part "R-EU_R0805"))
    )
    (comp (ref "R12")
      (value "120")
      (footprint "eagle-import:R0805")
      (libsource (lib "eagle-import") (part "R-EU_R0805"))
    )
    (comp (ref "R13")
      (value "120")
      (footprint "eagle-import:R0805")
      (libsource (lib "eagle-import") (part "R-EU_R0805"))
    )
    (comp (ref "R14")
      (value "30")
      (footprint "eagle-import:R0805")
      (libsource (lib "eagle-import") (part "R-EU_R0805"))
    )
    (comp (ref "R15")
      (value "120")
      (footprint "eagle-import:R0805")
      (libsource (lib "eagle-import") (part "R-EU_R0805"))
    )
    (comp (ref "R16")
      (value "120")
      (footprint "eagle-import:R0805")
      (libsource (lib "eagle-import") (part "R-EU_R0805"))
    )
    (comp (ref "R17")
      (value "30")
      (footprint "eagle-import:R0805")
      (libsource (lib "eagle-import") (part "R-EU_R0805"))
    )
    (comp (ref "R18")
      (value "120")
      (footprint "eagle-import:R0805")
      (libsource (lib "eagle-import") (part "R-EU_R0805"))
    )
    (comp (ref "R19")
      (value "120")
      (footprint "eagle-import:R0805")
      (libsource (lib "eagle-import") (part "R-EU_R0805"))
    )
    (comp (ref "R20")
      (value "30")
      (footprint "eagle-import:R0805")
      (libsource (lib "eagle-import") (part "R-EU_R0805"))
    )
    (comp (ref "R21")
      (value "120")
      (footprint "eagle-import:R0805")
      (libsource (lib "eagle-import") (part "R-EU_R0805"))
    )
    (comp (ref "R22")
      (value "120")
      (footprint "eagle-import:R0805")
      (libsource (lib "eagle-import") (part "R-EU_R0805"))
    )
    (comp (ref "R23")
      (value "30")
      (footprint "eagle-import:R0805")
      (libsource (lib "eagle-import") (part "R-EU_R0805"))
    )
    (comp (ref "R24")
      (value "120")
      (footprint "eagle-import:R0805")
      (libsource (lib "eagle-import") (part "R-EU_R0805"))
    )
    (comp (ref "R25")
      (value "120")
      (footprint "eagle-import:R0805")
      (libsource (lib "eagle-import") (part "R-EU_R0805"))
    )
    (comp (ref "R26")
      (value "30")
      (footprint "eagle-import:R0805")
      (libsource (lib "eagle-import") (part "R-EU_R0805"))
    )
    (comp (ref "R27")
      (value "120")
      (footprint "eagle-import:R0805")
      (libsource (lib "eagle-import") (part "R-EU_R0805"))
    )
    (comp (ref "R28")
      (value "120")
      (footprint "eagle-import:R0805")
      (libsource (lib "eagle-import") (part "R-EU_R0805"))
    )
    (comp (ref "R29")
      (value "30")
      (footprint "eagle-import:R0805")
      (libsource (lib "eagle-import") (part "R-EU_R0805"))
    )
    (comp (ref "R30")
      (value "30")
      (footprint "eagle-import:R0805")
      (libsource (lib "eagle-import") (part "R-EU_R0805"))
    )
    (comp (ref "R31")
      (value "120")
      (footprint "eagle-import:R0805")
      (libsource (lib "eagle-import") (part "R-EU_R0805"))
    )
    (comp (ref "R32")
      (value "120")
      (footprint "eagle-import:R0805")
      (libsource (lib "eagle-import") (part "R-EU_R0805"))
    )
    (comp (ref "R33")
      (value "30")
      (footprint "eagle-import:R0805")
      (libsource (lib "eagle-import") (part "R-EU_R0805"))
    )
    (comp (ref "R34")
      (value "30")
      (footprint "eagle-import:R0805")
      (libsource (lib "eagle-import") (part "R-EU_R0805"))
    )
    (comp (ref "R35")
      (value "30")
      (footprint "eagle-import:R0805")
      (libsource (lib "eagle-import") (part "R-EU_R0805"))
    )
    (comp (ref "R36")
      (value "30")
      (footprint "eagle-import:R0805")
      (libsource (lib "eagle-import") (part "R-EU_R0805"))
    )
    (comp (ref "R37")
      (value "30")
      (footprint "eagle-import:R0805")
      (libsource (lib "eagle-import") (part "R-EU_R0805"))
    )
    (comp (ref "R38")
      (value "30")
      (footprint "eagle-import:R0805")
      (libsource (lib "eagle-import") (part "R-EU_R0805"))
    )
    (comp (ref "R39")
      (value "30")
      (footprint "eagle-import:R0805")
      (libsource (lib "eagle-import") (part "R-EU_R0805"))
    )
    (comp (ref "R40")
      (value "30")
      (footprint "eagle-import:R0805")
      (libsource (lib "eagle-import") (part "R-EU_R0805"))
    )
    (comp (ref "R41")
      (value "30")
      (footprint "eagle-import:R0805")
      (libsource (lib "eagle-import") (part "R-EU_R0805"))
    )
    (comp (ref "R42")
      (value "30")
      (footprint "eagle-import:R0805")
      (libsource (lib "eagle-import") (part "R-EU_R0805"))
    )
    (comp (ref "R43")
      (value "30")
      (footprint "eagle-import:R0805")
      (libsource (lib "eagle-import") (part "R-EU_R0805"))
    )
    (comp (ref "R44")
      (value "30")
      (footprint "eagle-import:R0805")
      (libsource (lib "eagle-import") (part "R-EU_R0805"))
    )
    (comp (ref "R45")
      (value "30")
      (footprint "eagle-import:R0805")
      (libsource (lib "eagle-import") (part "R-EU_R0805"))
    )
    (comp (ref "R46")
      (value "30")
      (footprint "eagle-import:R0805")
      (libsource (lib "eagle-import") (part "R-EU_R0805"))
    )
    (comp (ref "R47")
      (value "30")
      (footprint "eagle-import:R0805")
      (libsource (lib "eagle-import") (part "R-EU_R0805"))
    )
    (comp (ref "R48")
      (value "30")
      (footprint "eagle-import:R0805")
      (libsource (lib "eagle-import") (part "R-EU_R0805"))
    )
    (comp (ref "T1")
      (value "SOT89 NPN BCE")
      (footprint "eagle-import:SOT89-BCE")
      (libsource (lib "eagle-import") (part "-NPN-SOT89-BCE"))
    )
    (comp (ref "T2")
      (value "SOT89 NPN BCE")
      (footprint "eagle-import:SOT89-BCE")
      (libsource (lib "eagle-import") (part "-NPN-SOT89-BCE"))
    )
    (comp (ref "T3")
      (value "SOT89 NPN BCE")
      (footprint "eagle-import:SOT89-BCE")
      (libsource (lib "eagle-import") (part "-NPN-SOT89-BCE"))
    )
    (comp (ref "C15")
      (value "100nF")
      (footprint "eagle-import:C0805K")
      (libsource (lib "eagle-import") (part "rcl_334_C-EUC0805K"))
    )
    (comp (ref "C16")
      (value "100nF")
      (footprint "eagle-import:C0805K")
      (libsource (lib "eagle-import") (part "rcl_334_C-EUC0805K"))
    )
    (comp (ref "C17")
      (value "100nF")
      (footprint "eagle-import:C0805K")
      (libsource (lib "eagle-import") (part "rcl_334_C-EUC0805K"))
    )
    (comp (ref "C18")
      (value "100nF")
      (footprint "eagle-import:C0805K")
      (libsource (lib "eagle-import") (part "rcl_334_C-EUC0805K"))
    )
    (comp (ref "C19")
      (value "100nF")
      (footprint "eagle-import:C0805K")
      (libsource (lib "eagle-import") (part "rcl_334_C-EUC0805K"))
    )
    (comp (ref "C20")
      (value "100nF")
      (footprint "eagle-import:C0805K")
      (libsource (lib "eagle-import") (part "rcl_334_C-EUC0805K"))
    )
    (comp (ref "C21")
      (value "100nF")
      (footprint "eagle-import:C0805K")
      (libsource (lib "eagle-import") (part "rcl_334_C-EUC0805K"))
    )
    (comp (ref "C22")
      (value "100nF")
      (footprint "eagle-import:C0805K")
      (libsource (lib "eagle-import") (part "rcl_334_C-EUC0805K"))
    )
    (comp (ref "PD1")
      (value "WS2812B")
      (footprint "eagle-import:5050")
      (fields (field (name "MF") "Adafruit Industries"))
      (libsource (lib "eagle-import") (part "WS2812B"))
    )
    (comp (ref "PD2")
      (value "WS2812B")
      (footprint "eagle-import:5050")
      (fields (field (name "MF") "Adafruit Industries"))
      (libsource (lib "eagle-import") (part "WS2812B"))
    )
    (comp (ref "PD3")
      (value "WS2812B")
      (footprint "eagle-import:5050")
      (fields (field (name "MF") "Adafruit Industries"))
      (libsource (lib "eagle-import") (part "WS2812B"))
    )
    (comp (ref "PD4")
      (value "WS2812B")
      (footprint "eagle-import:5050")
      (fields (field (name "MF") "Adafruit Industries"))
      (libsource (lib "eagle-import") (part "WS2812B"))
    )
    (comp (ref "PD5")
      (value "WS2812B")
      (footprint "eagle-import:5050")
      (fields (field (name "MF") "Adafruit Industries"))
      (libsource (lib "eagle-import") (part "WS2812B"))
    )
    (comp (ref "PD6")
      (value "WS2812B")
      (footprint "eagle-import:5050")
      (fields (field (name "MF") "Adafruit Industries"))
      (libsource (lib "eagle-import") (part "WS2812B"))
    )
    (comp (ref "PD7")
      (value "WS2812B")
      (footprint "eagle-import:5050")
      (fields (field (name "MF") "Adafruit Industries"))
      (libsource (lib "eagle-import") (part "WS2812B"))
    )
    (comp (ref "PD8")
      (value "WS2812B")
      (footprint "eagle-import:5050")
      (fields (field (name "MF") "Adafruit Industries"))
      (libsource (lib "eagle-import") (part "WS2812B"))
    )
    (comp (ref "PD9")
      (value "WS2812B")
      (footprint "eagle-import:5050")
      (fields (field (name "MF") "Adafruit Industries"))
      (libsource (lib "eagle-import") (part "WS2812B"))
    )
    (comp (ref "PD10")
      (value "WS2812B")
      (footprint "eagle-import:5050")
      (fields (field (name "MF") "Adafruit Industries"))
      (libsource (lib "eagle-import") (part "WS2812B"))
    )
    (comp (ref "PD11")
      (value "WS2812B")
      (footprint "eagle-import:5050")
      (fields (field (name "MF") "Adafruit Industries"))
      (libsource (lib "eagle-import") (part "WS2812B"))
    )
    (comp (ref "PD12")
      (value "WS2812B")
      (footprint "eagle-import:5050")
      (fields (field (name "MF") "Adafruit Industries"))
      (libsource (lib "eagle-import") (part "WS2812B"))
    )
    (comp (ref "PD13")
      (value "WS2812B")
      (footprint "eagle-import:5050")
      (fields (field (name "MF") "Adafruit Industries"))
      (libsource (lib "eagle-import") (part "WS2812B"))
    )
    (comp (ref "PD14")
      (value "WS2812B")
      (footprint "eagle-import:5050")
      (fields (field (name "MF") "Adafruit Industries"))
      (libsource (lib "eagle-import") (part "WS2812B"))
    )
    (comp (ref "PD15")
      (value "WS2812B")
      (footprint "eagle-import:5050")
      (fields (field (name "MF") "Adafruit Industries"))
      (libsource (lib "eagle-import") (part "WS2812B"))
    )
    (comp (ref "PD16")
      (value "WS2812B")
      (footprint "eagle-import:5050")
      (fields (field (name "MF") "Adafruit Industries"))
      (libsource (lib "eagle-import") (part "WS2812B"))
    )
    (comp (ref "PD17")
      (value "WS2812B2020")
      (footprint "eagle-import:LED_WS2812-2020")
      (libsource (lib "eagle-import") (part "WS2812B2020"))
    )
    (comp (ref "PD18")
      (value "WS2812B2020")
      (footprint "eagle-import:LED_WS2812-2020")
      (libsource (lib "eagle-import") (part "WS2812B2020"))
    )
    (comp (ref "PD19")
      (value "WS2812B2020")
      (footprint "eagle-import:LED_WS2812-2020")
      (libsource (lib "eagle-import") (part "WS2812B2020"))
    )
    (comp (ref "PD20")
      (value "WS2812B2020")
      (footprint "eagle-import:LED_WS2812-2020")
      (libsource (lib "eagle-import") (part "WS2812B2020"))
    )
    (comp (ref "PD21")
      (value "WS2812B2020")
      (footprint "eagle-import:LED_WS2812-2020")
      (libsource (lib "eagle-import") (part "WS2812B2020"))
    )
    (comp (ref "PD22")
      (value "WS2812B2020")
      (footprint "eagle-import:LED_WS2812-2020")
      (libsource (lib "eagle-import") (part "WS2812B2020"))
    )
    (comp (ref "PD23")
      (value "WS2812B2020")
      (footprint "eagle-import:LED_WS2812-2020")
      (libsource (lib "eagle-import") (part "WS2812B2020"))
    )
    (comp (ref "PD24")
      (value "WS2812B2020")
      (footprint "eagle-import:LED_WS2812-2020")
      (libsource (lib "eagle-import") (part "WS2812B2020"))
    )
    (comp (ref "PD25")
      (value "WS2812B2020")
      (footprint "eagle-import:LED_WS2812-2020")
      (libsource (lib "eagle-import") (part "WS2812B2020"))
    )
    (comp (ref "PD26")
      (value "WS2812B2020")
      (footprint "eagle-import:LED_WS2812-2020")
      (libsource (lib "eagle-import") (part "WS2812B2020"))
    )
    (comp (ref "PD27")
      (value "WS2812B2020")
      (footprint "eagle-import:LED_WS2812-2020")
      (libsource (lib "eagle-import") (part "WS2812B2020"))
    )
    (comp (ref "PD28")
      (value "WS2812B2020")
      (footprint "eagle-import:LED_WS2812-2020")
      (libsource (lib "eagle-import") (part "WS2812B2020"))
    )
    (comp (ref "PD29")
      (value "WS2812B2020")
      (footprint "eagle-import:LED_WS2812-2020")
      (libsource (lib "eagle-import") (part "WS2812B2020"))
    )
    (comp (ref "PD30")
      (value "WS2812B2020")
      (footprint "eagle-import:LED_WS2812-2020")
      (libsource (lib "eagle-import") (part "WS2812B2020"))
    )
    (comp (ref "PD31")
      (value "WS2812B2020")
      (footprint "eagle-import:LED_WS2812-2020")
      (libsource (lib "eagle-import") (part "WS2812B2020"))
    )
    (comp (ref "PD32")
      (value "WS2812B2020")
      (footprint "eagle-import:LED_WS2812-2020")
      (libsource (lib "eagle-import") (part "WS2812B2020"))
    )
    (comp (ref "PD33")
      (value "WS2812B2020")
      (footprint "eagle-import:LED_WS2812-2020")
      (libsource (lib "eagle-import") (part "WS2812B2020"))
    )
    (comp (ref "PD34")
      (value "WS2812B2020")
      (footprint "eagle-import:LED_WS2812-2020")
      (libsource (lib "eagle-import") (part "WS2812B2020"))
    )
    (comp (ref "PD35")
      (value "WS2812B2020")
      (footprint "eagle-import:LED_WS2812-2020")
      (libsource (lib "eagle-import") (part "WS2812B2020"))
    )
    (comp (ref "PD36")
      (value "WS2812B2020")
      (footprint "eagle-import:LED_WS2812-2020")
      (libsource (lib "eagle-import") (part "WS2812B2020"))
    )
    (comp (ref "PD37")
      (value "WS2812B2020")
      (footprint "eagle-import:LED_WS2812-2020")
      (libsource (lib "eagle-import") (part "WS2812B2020"))
    )
    (comp (ref "PD38")
      (value "WS2812B2020")
      (footprint "eagle-import:LED_WS2812-2020")
      (libsource (lib "eagle-import") (part "WS2812B2020"))
    )
    (comp (ref "PD39")
      (value "WS2812B2020")
      (footprint "eagle-import:LED_WS2812-2020")
      (libsource (lib "eagle-import") (part "WS2812B2020"))
    )
    (comp (ref "PD40")
      (value "WS2812B2020")
      (footprint "eagle-import:LED_WS2812-2020")
      (libsource (lib "eagle-import") (part "WS2812B2020"))
    )
    (comp (ref "PD41")
      (value "WS2812B2020")
      (footprint "eagle-import:LED_WS2812-2020")
      (libsource (lib "eagle-import") (part "WS2812B2020"))
    )
    (comp (ref "PD42")
      (value "WS2812B2020")
      (footprint "eagle-import:LED_WS2812-2020")
      (libsource (lib "eagle-import") (part "WS2812B2020"))
    )
    (comp (ref "PD43")
      (value "WS2812B2020")
      (footprint "eagle-import:LED_WS2812-2020")
      (libsource (lib "eagle-import") (part "WS2812B2020"))
    )
    (comp (ref "PD44")
      (value "WS2812B2020")
      (footprint "eagle-import:LED_WS2812-2020")
      (libsource (lib "eagle-import") (part "WS2812B2020"))
    )
    (comp (ref "PD45")
      (value "WS2812B2020")
      (footprint "eagle-import:LED_WS2812-2020")
      (libsource (lib "eagle-import") (part "WS2812B2020"))
    )
    (comp (ref "PD46")
      (value "WS2812B2020")
      (footprint "eagle-import:LED_WS2812-2020")
      (libsource (lib "eagle-import") (part "WS2812B2020"))
    )
    (comp (ref "PD47")
      (value "WS2812B2020")
      (footprint "eagle-import:LED_WS2812-2020")
      (libsource (lib "eagle-import") (part "WS2812B2020"))
    )
    (comp (ref "PD48")
      (value "WS2812B2020")
      (footprint "eagle-import:LED_WS2812-2020")
      (libsource (lib "eagle-import") (part "WS2812B2020"))
    )
    (comp (ref "PD49")
      (value "WS2812B2020")
      (footprint "eagle-import:LED_WS2812-2020")
      (libsource (lib "eagle-import") (part "WS2812B2020"))
    )
    (comp (ref "PD50")
      (value "WS2812B2020")
      (footprint "eagle-import:LED_WS2812-2020")
      (libsource (lib "eagle-import") (part "WS2812B2020"))
    )
    (comp (ref "PD51")
      (value "WS2812B2020")
      (footprint "eagle-import:LED_WS2812-2020")
      (libsource (lib "eagle-import") (part "WS2812B2020"))
    )
    (comp (ref "PD52")
      (value "WS2812B2020")
      (footprint "eagle-import:LED_WS2812-2020")
      (libsource (lib "eagle-import") (part "WS2812B2020"))
    )
    (comp (ref "PD53")
      (value "WS2812B2020")
      (footprint "eagle-import:LED_WS2812-2020")
      (libsource (lib "eagle-import") (part "WS2812B2020"))
    )
    (comp (ref "PD54")
      (value "WS2812B2020")
      (footprint "eagle-import:LED_WS2812-2020")
      (libsource (lib "eagle-import") (part "WS2812B2020"))
    )
    (comp (ref "PD55")
      (value "WS2812B2020")
      (footprint "eagle-import:LED_WS2812-2020")
      (libsource (lib "eagle-import") (part "WS2812B2020"))
    )
    (comp (ref "PD56")
      (value "WS2812B2020")
      (footprint "eagle-import:LED_WS2812-2020")
      (libsource (lib "eagle-import") (part "WS2812B2020"))
    )
    (comp (ref "PD57")
      (value "WS2812B2020")
      (footprint "eagle-import:LED_WS2812-2020")
      (libsource (lib "eagle-import") (part "WS2812B2020"))
    )
    (comp (ref "PD58")
      (value "WS2812B2020")
      (footprint "eagle-import:LED_WS2812-2020")
      (libsource (lib "eagle-import") (part "WS2812B2020"))
    )
    (comp (ref "PD59")
      (value "WS2812B2020")
      (footprint "eagle-import:LED_WS2812-2020")
      (libsource (lib "eagle-import") (part "WS2812B2020"))
    )
    (comp (ref "PD60")
      (value "WS2812B2020")
      (footprint "eagle-import:LED_WS2812-2020")
      (libsource (lib "eagle-import") (part "WS2812B2020"))
    )
    (comp (ref "PD61")
      (value "WS2812B2020")
      (footprint "eagle-import:LED_WS2812-2020")
      (libsource (lib "eagle-import") (part "WS2812B2020"))
    )
    (comp (ref "PD62")
      (value "WS2812B2020")
      (footprint "eagle-import:LED_WS2812-2020")
      (libsource (lib "eagle-import") (part "WS2812B2020"))
    )
    (comp (ref "PD63")
      (value "WS2812B2020")
      (footprint "eagle-import:LED_WS2812-2020")
      (libsource (lib "eagle-import") (part "WS2812B2020"))
    )
    (comp (ref "PD64")
      (value "WS2812B2020")
      (footprint "eagle-import:LED_WS2812-2020")
      (libsource (lib "eagle-import") (part "WS2812B2020"))
    )
    (comp (ref "PD65")
      (value "WS2812B2020")
      (footprint "eagle-import:LED_WS2812-2020")
      (libsource (lib "eagle-import") (part "WS2812B2020"))
    )
    (comp (ref "PD66")
      (value "WS2812B2020")
      (footprint "eagle-import:LED_WS2812-2020")
      (libsource (lib "eagle-import") (part "WS2812B2020"))
    )
    (comp (ref "PD67")
      (value "WS2812B2020")
      (footprint "eagle-import:LED_WS2812-2020")
      (libsource (lib "eagle-import") (part "WS2812B2020"))
    )
    (comp (ref "PD68")
      (value "WS2812B2020")
      (footprint "eagle-import:LED_WS2812-2020")
      (libsource (lib "eagle-import") (part "WS2812B2020"))
    )
    (comp (ref "PD69")
      (value "WS2812B2020")
      (footprint "eagle-import:LED_WS2812-2020")
      (libsource (lib "eagle-import") (part "WS2812B2020"))
    )
    (comp (ref "PD70")
      (value "WS2812B2020")
      (footprint "eagle-import:LED_WS2812-2020")
      (libsource (lib "eagle-import") (part "WS2812B2020"))
    )
    (comp (ref "PD71")
      (value "WS2812B2020")
      (footprint "eagle-import:LED_WS2812-2020")
      (libsource (lib "eagle-import") (part "WS2812B2020"))
    )
    (comp (ref "PD72")
      (value "WS2812B2020")
      (footprint "eagle-import:LED_WS2812-2020")
      (libsource (lib "eagle-import") (part "WS2812B2020"))
    )
    (comp (ref "PD73")
      (value "WS2812B2020")
      (footprint "eagle-import:LED_WS2812-2020")
      (libsource (lib "eagle-import") (part "WS2812B2020"))
    )
    (comp (ref "PD74")
      (value "WS2812B2020")
      (footprint "eagle-import:LED_WS2812-2020")
      (libsource (lib "eagle-import") (part "WS2812B2020"))
    )
    (comp (ref "PD75")
      (value "WS2812B2020")
      (footprint "eagle-import:LED_WS2812-2020")
      (libsource (lib "eagle-import") (part "WS2812B2020"))
    )
    (comp (ref "PD76")
      (value "WS2812B2020")
      (footprint "eagle-import:LED_WS2812-2020")
      (libsource (lib "eagle-import") (part "WS2812B2020"))
    )
    (comp (ref "PD77")
      (value "WS2812B2020")
      (footprint "eagle-import:LED_WS2812-2020")
      (libsource (lib "eagle-import") (part "WS2812B2020"))
    )
    (comp (ref "PD78")
      (value "WS2812B2020")
      (footprint "eagle-import:LED_WS2812-2020")
      (libsource (lib "eagle-import") (part "WS2812B2020"))
    )
    (comp (ref "PD79")
      (value "WS2812B2020")
      (footprint "eagle-import:LED_WS2812-2020")
      (libsource (lib "eagle-import") (part "WS2812B2020"))
    )
    (comp (ref "PD80")
      (value "WS2812B2020")
      (footprint "eagle-import:LED_WS2812-2020")
      (libsource (lib "eagle-import") (part "WS2812B2020"))
    )
    (comp (ref "PD81")
      (value "WS2812B2020")
      (footprint "eagle-import:LED_WS2812-2020")
      (libsource (lib "eagle-import") (part "WS2812B2020"))
    )
    (comp (ref "PD82")
      (value "WS2812B2020")
      (footprint "eagle-import:LED_WS2812-2020")
      (libsource (lib "eagle-import") (part "WS2812B2020"))
    )
    (comp (ref "PD83")
      (value "WS2812B2020")
      (footprint "eagle-import:LED_WS2812-2020")
      (libsource (lib "eagle-import") (part "WS2812B2020"))
    )
    (comp (ref "PD84")
      (value "WS2812B2020")
      (footprint "eagle-import:LED_WS2812-2020")
      (libsource (lib "eagle-import") (part "WS2812B2020"))
    )
    (comp (ref "PD85")
      (value "WS2812B2020")
      (footprint "eagle-import:LED_WS2812-2020")
      (libsource (lib "eagle-import") (part "WS2812B2020"))
    )
    (comp (ref "PD86")
      (value "WS2812B2020")
      (footprint "eagle-import:LED_WS2812-2020")
      (libsource (lib "eagle-import") (part "WS2812B2020"))
    )
    (comp (ref "PD87")
      (value "WS2812B2020")
      (footprint "eagle-import:LED_WS2812-2020")
      (libsource (lib "eagle-import") (part "WS2812B2020"))
    )
    (comp (ref "PD88")
      (value "WS2812B2020")
      (footprint "eagle-import:LED_WS2812-2020")
      (libsource (lib "eagle-import") (part "WS2812B2020"))
    )
    (comp (ref "PD89")
      (value "WS2812B2020")
      (footprint "eagle-import:LED_WS2812-2020")
      (libsource (lib "eagle-import") (part "WS2812B2020"))
    )
    (comp (ref "PD90")
      (value "WS2812B2020")
      (footprint "eagle-import:LED_WS2812-2020")
      (libsource (lib "eagle-import") (part "WS2812B2020"))
    )
    (comp (ref "PD91")
      (value "WS2812B2020")
      (footprint "eagle-import:LED_WS2812-2020")
      (libsource (lib "eagle-import") (part "WS2812B2020"))
    )
    (comp (ref "PD92")
      (value "WS2812B2020")
      (footprint "eagle-import:LED_WS2812-2020")
      (libsource (lib "eagle-import") (part "WS2812B2020"))
    )
    (comp (ref "PD93")
      (value "WS2812B2020")
      (footprint "eagle-import:LED_WS2812-2020")
      (libsource (lib "eagle-import") (part "WS2812B2020"))
    )
    (comp (ref "PD94")
      (value "WS2812B2020")
      (footprint "eagle-import:LED_WS2812-2020")
      (libsource (lib "eagle-import") (part "WS2812B2020"))
    )
    (comp (ref "PD95")
      (value "WS2812B2020")
      (footprint "eagle-import:LED_WS2812-2020")
      (libsource (lib "eagle-import") (part "WS2812B2020"))
    )
    (comp (ref "PD96")
      (value "WS2812B2020")
      (footprint "eagle-import:LED_WS2812-2020")
      (libsource (lib "eagle-import") (part "WS2812B2020"))
    )
    (comp (ref "PD97")
      (value "WS2812B2020")
      (footprint "eagle-import:LED_WS2812-2020")
      (libsource (lib "eagle-import") (part "WS2812B2020"))
    )
    (comp (ref "PD98")
      (value "WS2812B2020")
      (footprint "eagle-import:LED_WS2812-2020")
      (libsource (lib "eagle-import") (part "WS2812B2020"))
    )
    (comp (ref "PD99")
      (value "WS2812B2020")
      (footprint "eagle-import:LED_WS2812-2020")
      (libsource (lib "eagle-import") (part "WS2812B2020"))
    )
    (comp (ref "PD100")
      (value "WS2812B2020")
      (footprint "eagle-import:LED_WS2812-2020")
      (libsource (lib "eagle-import") (part "WS2812B2020"))
    )
    (comp (ref "PD101")
      (value "WS2812B2020")
      (footprint "eagle-import:LED_WS2812-2020")
      (libsource (lib "eagle-import") (part "WS2812B2020"))
    )
    (comp (ref "PD102")
      (value "WS2812B2020")
      (footprint "eagle-import:LED_WS2812-2020")
      (libsource (lib "eagle-import") (part "WS2812B2020"))
    )
    (comp (ref "PD103")
      (value "WS2812B2020")
      (footprint "eagle-import:LED_WS2812-2020")
      (libsource (lib "eagle-import") (part "WS2812B2020"))
    )
    (comp (ref "PD104")
      (value "WS2812B2020")
      (footprint "eagle-import:LED_WS2812-2020")
      (libsource (lib "eagle-import") (part "WS2812B2020"))
    )
    (comp (ref "PD105")
      (value "WS2812B2020")
      (footprint "eagle-import:LED_WS2812-2020")
      (libsource (lib "eagle-import") (part "WS2812B2020"))
    )
    (comp (ref "PD106")
      (value "WS2812B2020")
      (footprint "eagle-import:LED_WS2812-2020")
      (libsource (lib "eagle-import") (part "WS2812B2020"))
    )
    (comp (ref "PD107")
      (value "WS2812B2020")
      (footprint "eagle-import:LED_WS2812-2020")
      (libsource (lib "eagle-import") (part "WS2812B2020"))
    )
    (comp (ref "PD108")
      (value "WS2812B2020")
      (footprint "eagle-import:LED_WS2812-2020")
      (libsource (lib "eagle-import") (part "WS2812B2020"))
    )
    (comp (ref "PD109")
      (value "WS2812B2020")
      (footprint "eagle-import:LED_WS2812-2020")
      (libsource (lib "eagle-import") (part "WS2812B2020"))
    )
    (comp (ref "PD110")
      (value "WS2812B2020")
      (footprint "eagle-import:LED_WS2812-2020")
      (libsource (lib "eagle-import") (part "WS2812B2020"))
    )
    (comp (ref "C1")
      (value "22uF / 35V")
      (footprint "eagle-import:SMC_D")
      (libsource (lib "eagle-import") (part "CPOL-EUSMCD"))
    )
    (comp (ref "C2")
      (value "100nF")
      (footprint "eagle-import:C0805K")
      (libsource (lib "eagle-import") (part "rcl_334_C-EUC0805K"))
    )
    (comp (ref "C3")
      (value "100nF")
      (footprint "eagle-import:C0805K")
      (libsource (lib "eagle-import") (part "rcl_334_C-EUC0805K"))
    )
    (comp (ref "C4")
      (value "100uF / 50V")
      (footprint "eagle-import:PANASONIC_F")
      (libsource (lib "eagle-import") (part "CPOL-EUF"))
    )
    (comp (ref "C5")
      (value "100nF")
      (footprint "eagle-import:C0805K")
      (libsource (lib "eagle-import") (part "rcl_334_C-EUC0805K"))
    )
    (comp (ref "C6")
      (value "4.7nF")
      (footprint "eagle-import:C0805K")
      (libsource (lib "eagle-import") (part "rcl_334_C-EUC0805K"))
    )
    (comp (ref "C7")
      (value "22uF / 35V")
      (footprint "eagle-import:SMC_D")
      (libsource (lib "eagle-import") (part "CPOL-EUSMCD"))
    )
    (comp (ref "C8")
      (value "100nF")
      (footprint "eagle-import:C0805K")
      (libsource (lib "eagle-import") (part "rcl_334_C-EUC0805K"))
    )
    (comp (ref "C9")
      (value "100nF")
      (footprint "eagle-import:C0805K")
      (libsource (lib "eagle-import") (part "rcl_334_C-EUC0805K"))
    )
    (comp (ref "C10")
      (value "100nF")
      (footprint "eagle-import:C0805K")
      (libsource (lib "eagle-import") (part "rcl_334_C-EUC0805K"))
    )
    (comp (ref "C11")
      (value "22pF")
      (footprint "eagle-import:C0805K")
      (libsource (lib "eagle-import") (part "rcl_334_C-EUC0805K"))
    )
    (comp (ref "C12")
      (value "22pF")
      (footprint "eagle-import:C0805K")
      (libsource (lib "eagle-import") (part "rcl_334_C-EUC0805K"))
    )
    (comp (ref "C13")
      (value "6.8pF")
      (footprint "eagle-import:C0805K")
      (libsource (lib "eagle-import") (part "rcl_334_C-EUC0805K"))
    )
    (comp (ref "C14")
      (value "6.8pF")
      (footprint "eagle-import:C0805K")
      (libsource (lib "eagle-import") (part "rcl_334_C-EUC0805K"))
    )
    (comp (ref "D1")
      (value "PESD1CAN")
      (footprint "eagle-import:SOT23")
      (libsource (lib "eagle-import") (part "PESD1CAN"))
    )
    (comp (ref "JP1")
      (value "PINHD-1X6")
      (footprint "eagle-import:1X06")
      (libsource (lib "eagle-import") (part "PINHD-1X6"))
    )
    (comp (ref "JP2")
      (value "PINHD-1X2")
      (footprint "eagle-import:1X02")
      (libsource (lib "eagle-import") (part "PINHD-1X2"))
    )
    (comp (ref "JP4")
      (value "PINHD-1X2")
      (footprint "eagle-import:1X02")
      (libsource (lib "eagle-import") (part "PINHD-1X2"))
    )
    (comp (ref "L1")
      (value "BLM18PG600")
      (footprint "eagle-import:L1608")
      (libsource (lib "eagle-import") (part "L_EU_L0603"))
    )
    (comp (ref "L2")
      (value "BLM18PG600")
      (footprint "eagle-import:L1608")
      (libsource (lib "eagle-import") (part "L_EU_L0603"))
    )
    (comp (ref "L3")
      (value "BLM18PG600")
      (footprint "eagle-import:L1608")
      (libsource (lib "eagle-import") (part "L_EU_L0603"))
    )
    (comp (ref "P1")
      (value "53048-0210")
      (footprint "eagle-import:53048-0210")
      (libsource (lib "eagle-import") (part "53048-0210"))
    )
    (comp (ref "Q1")
      (value "16MHz")
      (footprint "eagle-import:SM49")
      (libsource (lib "eagle-import") (part "CRYSTALSM49"))
    )
    (comp (ref "Q2")
      (value "32.768kHz")
      (footprint "eagle-import:SMD4_270")
      (libsource (lib "eagle-import") (part "MC-306"))
    )
    (comp (ref "R1")
      (value "1k")
      (footprint "eagle-import:R0805")
      (libsource (lib "eagle-import") (part "R-EU_R0805"))
    )
    (comp (ref "R2")
      (value "0")
      (footprint "eagle-import:R0805")
      (libsource (lib "eagle-import") (part "R-EU_R0805"))
    )
    (comp (ref "R3")
      (value "60")
      (footprint "eagle-import:R0805")
      (libsource (lib "eagle-import") (part "R-EU_R0805"))
    )
    (comp (ref "R4")
      (value "60")
      (footprint "eagle-import:R0805")
      (libsource (lib "eagle-import") (part "R-EU_R0805"))
    )
    (comp (ref "R5")
      (value "100")
      (footprint "eagle-import:R0805")
      (libsource (lib "eagle-import") (part "R-EU_R0805"))
    )
    (comp (ref "SJ6")
      (value "SJ2W")
      (footprint "eagle-import:SJ_2")
      (libsource (lib "eagle-import") (part "SJ2W"))
    )
    (comp (ref "SJ7")
      (value "SJ2W")
      (footprint "eagle-import:SJ_2")
      (libsource (lib "eagle-import") (part "SJ2W"))
    )
    (comp (ref "SJ8")
      (value "SJ2W")
      (footprint "eagle-import:SJ_2")
      (libsource (lib "eagle-import") (part "SJ2W"))
    )
    (comp (ref "U1")
      (value "TLE7251VSO8")
      (footprint "eagle-import:SO8")
      (libsource (lib "eagle-import") (part "TLE7251VSO8"))
    )
    (comp (ref "U2")
      (value "DFPLAYER")
      (footprint "eagle-import:DFPLAYER")
      (libsource (lib "eagle-import") (part "DFPLAYER"))
    )
    (comp (ref "U3")
      (value "STM32F103RET6")
      (footprint "eagle-import:QFP50P1200X1200X160-64N")
      (libsource (lib "eagle-import") (part "STM32F103RET6"))
    )
    (comp (ref "X1")
      (value "HEADER_POS3_43650-0315")
      (footprint "eagle-import:43650-0315")
      (libsource (lib "eagle-import") (part "HEADER_POS3_?43650-0315"))
    )
    (comp (ref "X2")
      (value "HEADER_POS3_43650-0315")
      (footprint "eagle-import:43650-0315")
      (libsource (lib "eagle-import") (part "HEADER_POS3_?43650-0315"))
    )
  )
  (nets
    (net (code "1") (name "+3V3") (class "Default")
      (node (ref "C32") (pin "+") (pinfunction "+_+") (pintype "passive"))
      (node (ref "C35") (pin "2") (pinfunction "2_2") (pintype "passive"))
      (node (ref "C40") (pin "1") (pinfunction "1_1") (pintype "passive"))
      (node (ref "C41") (pin "1") (pinfunction "1_1") (pintype "passive"))
      (node (ref "C42") (pin "1") (pinfunction "1_1") (pintype "passive"))
      (node (ref "C43") (pin "+") (pinfunction "+_+") (pintype "passive"))
      (node (ref "C5") (pin "2") (pinfunction "2_2") (pintype "passive"))
      (node (ref "DISPLAY1") (pin "5") (pinfunction "SHLC_5") (pintype "bidirectional"))
      (node (ref "DISPLAY1") (pin "6") (pinfunction "SHLS_6") (pintype "bidirectional"))
      (node (ref "DISPLAY1") (pin "7") (pinfunction "VDD_7") (pintype "bidirectional"))
      (node (ref "DISPLAY1") (pin "8") (pinfunction "VDDIO_8") (pintype "bidirectional"))
      (node (ref "IC1") (pin "24") (pinfunction "VCC_24") (pintype "bidirectional"))
      (node (ref "JP1") (pin "1") (pinfunction "1_1") (pintype "passive"))
      (node (ref "JP3") (pin "1") (pinfunction "1_1") (pintype "passive"))
      (node (ref "L2") (pin "2") (pinfunction "2_2") (pintype "passive"))
      (node (ref "L3") (pin "2") (pinfunction "2_2") (pintype "passive"))
      (node (ref "L5") (pin "1") (pinfunction "1_1") (pintype "passive"))
      (node (ref "L7") (pin "1") (pinfunction "1_1") (pintype "passive"))
      (node (ref "L8") (pin "1") (pinfunction "1_1") (pintype "passive"))
      (node (ref "L9") (pin "1") (pinfunction "1_1") (pintype "passive"))
      (node (ref "P2") (pin "2") (pinfunction "2_2") (pintype "passive"))
      (node (ref "P3") (pin "2") (pinfunction "2_2") (pintype "passive"))
      (node (ref "P4") (pin "2") (pinfunction "2_2") (pintype "passive"))
      (node (ref "R14") (pin "2") (pinfunction "2_2") (pintype "passive"))
      (node (ref "R17") (pin "2") (pinfunction "2_2") (pintype "passive"))
      (node (ref "R20") (pin "2") (pinfunction "2_2") (pintype "passive"))
      (node (ref "R23") (pin "2") (pinfunction "2_2") (pintype "passive"))
      (node (ref "R26") (pin "2") (pinfunction "2_2") (pintype "passive"))
      (node (ref "R29") (pin "2") (pinfunction "2_2") (pintype "passive"))
      (node (ref "R30") (pin "2") (pinfunction "2_2") (pintype "passive"))
      (node (ref "R33") (pin "2") (pinfunction "2_2") (pintype "passive"))
      (node (ref "R34") (pin "2") (pinfunction "2_2") (pintype "passive"))
      (node (ref "R35") (pin "2") (pinfunction "2_2") (pintype "passive"))
      (node (ref "R36") (pin "2") (pinfunction "2_2") (pintype "passive"))
      (node (ref "R37") (pin "2") (pinfunction "2_2") (pintype "passive"))
      (node (ref "R38") (pin "2") (pinfunction "2_2") (pintype "passive"))
      (node (ref "R39") (pin "2") (pinfunction "2_2") (pintype "passive"))
      (node (ref "R40") (pin "2") (pinfunction "2_2") (pintype "passive"))
      (node (ref "R41") (pin "2") (pinfunction "2_2") (pintype "passive"))
      (node (ref "R42") (pin "2") (pinfunction "2_2") (pintype "passive"))
      (node (ref "R43") (pin "2") (pinfunction "2_2") (pintype "passive"))
      (node (ref "R44") (pin "2") (pinfunction "2_2") (pintype "passive"))
      (node (ref "R45") (pin "2") (pinfunction "2_2") (pintype "passive"))
      (node (ref "R46") (pin "2") (pinfunction "2_2") (pintype "passive"))
      (node (ref "R47") (pin "2") (pinfunction "2_2") (pintype "passive"))
      (node (ref "R48") (pin "2") (pinfunction "2_2") (pintype "passive"))
      (node (ref "R53") (pin "2") (pinfunction "2_2") (pintype "passive"))
      (node (ref "R54") (pin "1") (pinfunction "1_1") (pintype "passive"))
      (node (ref "R58") (pin "2") (pinfunction "2_2") (pintype "passive"))
      (node (ref "R59") (pin "2") (pinfunction "2_2") (pintype "passive"))
      (node (ref "R60") (pin "2") (pinfunction "2_2") (pintype "passive"))
      (node (ref "R61") (pin "2") (pinfunction "2_2") (pintype "passive"))
      (node (ref "R62") (pin "2") (pinfunction "2_2") (pintype "passive"))
      (node (ref "R63") (pin "2") (pinfunction "2_2") (pintype "passive"))
      (node (ref "R64") (pin "2") (pinfunction "2_2") (pintype "passive"))
      (node (ref "R65") (pin "2") (pinfunction "2_2") (pintype "passive"))
      (node (ref "R66") (pin "2") (pinfunction "2_2") (pintype "passive"))
      (node (ref "R67") (pin "2") (pinfunction "2_2") (pintype "passive"))
      (node (ref "SJ6") (pin "3") (pinfunction "3_3") (pintype "passive"))
      (node (ref "SJ7") (pin "3") (pinfunction "3_3") (pintype "passive"))
      (node (ref "SJ8") (pin "3") (pinfunction "3_3") (pintype "passive"))
      (node (ref "TP1") (pin "TP") (pinfunction "TP_TP") (pintype "input"))
      (node (ref "U1") (pin "5") (pinfunction "VIO_5") (pintype "bidirectional"))
      (node (ref "U10") (pin "2") (pinfunction "VCC_2") (pintype "power_in"))
      (node (ref "U11") (pin "2") (pinfunction "VCC_2") (pintype "power_in"))
      (node (ref "U4") (pin "3") (pinfunction "VOUT_3") (pintype "output"))
      (node (ref "U8") (pin "8") (pinfunction "VCC_8") (pintype "power_in"))
      (node (ref "U9") (pin "2") (pinfunction "VCC_2") (pintype "power_in"))
    )
    (net (code "2") (name "+5V") (class "Default")
      (node (ref "C15") (pin "2") (pinfunction "2_2") (pintype "passive"))
      (node (ref "C16") (pin "2") (pinfunction "2_2") (pintype "passive"))
      (node (ref "C17") (pin "2") (pinfunction "2_2") (pintype "passive"))
      (node (ref "C18") (pin "1") (pinfunction "1_1") (pintype "passive"))
      (node (ref "C19") (pin "1") (pinfunction "1_1") (pintype "passive"))
      (node (ref "C20") (pin "1") (pinfunction "1_1") (pintype "passive"))
      (node (ref "C21") (pin "1") (pinfunction "1_1") (pintype "passive"))
      (node (ref "C22") (pin "1") (pinfunction "1_1") (pintype "passive"))
      (node (ref "C23") (pin "+") (pinfunction "+_+") (pintype "passive"))
      (node (ref "C25") (pin "2") (pinfunction "2_2") (pintype "passive"))
      (node (ref "C33") (pin "+") (pinfunction "+_+") (pintype "passive"))
      (node (ref "C36") (pin "2") (pinfunction "2_2") (pintype "passive"))
      (node (ref "JP2") (pin "1") (pinfunction "1_1") (pintype "passive"))
      (node (ref "L6") (pin "1") (pinfunction "1_1") (pintype "passive"))
      (node (ref "PD1") (pin "1") (pinfunction "VDD_1") (pintype "power_in"))
      (node (ref "PD10") (pin "1") (pinfunction "VDD_1") (pintype "power_in"))
      (node (ref "PD100") (pin "4") (pinfunction "VDD_4") (pintype "power_in"))
      (node (ref "PD101") (pin "4") (pinfunction "VDD_4") (pintype "power_in"))
      (node (ref "PD102") (pin "4") (pinfunction "VDD_4") (pintype "power_in"))
      (node (ref "PD103") (pin "4") (pinfunction "VDD_4") (pintype "power_in"))
      (node (ref "PD104") (pin "4") (pinfunction "VDD_4") (pintype "power_in"))
      (node (ref "PD105") (pin "4") (pinfunction "VDD_4") (pintype "power_in"))
      (node (ref "PD106") (pin "4") (pinfunction "VDD_4") (pintype "power_in"))
      (node (ref "PD107") (pin "4") (pinfunction "VDD_4") (pintype "power_in"))
      (node (ref "PD108") (pin "4") (pinfunction "VDD_4") (pintype "power_in"))
      (node (ref "PD109") (pin "4") (pinfunction "VDD_4") (pintype "power_in"))
      (node (ref "PD11") (pin "1") (pinfunction "VDD_1") (pintype "power_in"))
      (node (ref "PD110") (pin "4") (pinfunction "VDD_4") (pintype "power_in"))
      (node (ref "PD12") (pin "1") (pinfunction "VDD_1") (pintype "power_in"))
      (node (ref "PD13") (pin "1") (pinfunction "VDD_1") (pintype "power_in"))
      (node (ref "PD14") (pin "1") (pinfunction "VDD_1") (pintype "power_in"))
      (node (ref "PD15") (pin "1") (pinfunction "VDD_1") (pintype "power_in"))
      (node (ref "PD16") (pin "1") (pinfunction "VDD_1") (pintype "power_in"))
      (node (ref "PD17") (pin "4") (pinfunction "VDD_4") (pintype "power_in"))
      (node (ref "PD18") (pin "4") (pinfunction "VDD_4") (pintype "power_in"))
      (node (ref "PD19") (pin "4") (pinfunction "VDD_4") (pintype "power_in"))
      (node (ref "PD2") (pin "1") (pinfunction "VDD_1") (pintype "power_in"))
      (node (ref "PD20") (pin "4") (pinfunction "VDD_4") (pintype "power_in"))
      (node (ref "PD21") (pin "4") (pinfunction "VDD_4") (pintype "power_in"))
      (node (ref "PD22") (pin "4") (pinfunction "VDD_4") (pintype "power_in"))
      (node (ref "PD23") (pin "4") (pinfunction "VDD_4") (pintype "power_in"))
      (node (ref "PD24") (pin "4") (pinfunction "VDD_4") (pintype "power_in"))
      (node (ref "PD25") (pin "4") (pinfunction "VDD_4") (pintype "power_in"))
      (node (ref "PD26") (pin "4") (pinfunction "VDD_4") (pintype "power_in"))
      (node (ref "PD27") (pin "4") (pinfunction "VDD_4") (pintype "power_in"))
      (node (ref "PD28") (pin "4") (pinfunction "VDD_4") (pintype "power_in"))
      (node (ref "PD29") (pin "4") (pinfunction "VDD_4") (pintype "power_in"))
      (node (ref "PD3") (pin "1") (pinfunction "VDD_1") (pintype "power_in"))
      (node (ref "PD30") (pin "4") (pinfunction "VDD_4") (pintype "power_in"))
      (node (ref "PD31") (pin "4") (pinfunction "VDD_4") (pintype "power_in"))
      (node (ref "PD32") (pin "4") (pinfunction "VDD_4") (pintype "power_in"))
      (node (ref "PD33") (pin "4") (pinfunction "VDD_4") (pintype "power_in"))
      (node (ref "PD34") (pin "4") (pinfunction "VDD_4") (pintype "power_in"))
      (node (ref "PD35") (pin "4") (pinfunction "VDD_4") (pintype "power_in"))
      (node (ref "PD36") (pin "4") (pinfunction "VDD_4") (pintype "power_in"))
      (node (ref "PD37") (pin "4") (pinfunction "VDD_4") (pintype "power_in"))
      (node (ref "PD38") (pin "4") (pinfunction "VDD_4") (pintype "power_in"))
      (node (ref "PD39") (pin "4") (pinfunction "VDD_4") (pintype "power_in"))
      (node (ref "PD4") (pin "1") (pinfunction "VDD_1") (pintype "power_in"))
      (node (ref "PD40") (pin "4") (pinfunction "VDD_4") (pintype "power_in"))
      (node (ref "PD41") (pin "4") (pinfunction "VDD_4") (pintype "power_in"))
      (node (ref "PD42") (pin "4") (pinfunction "VDD_4") (pintype "power_in"))
      (node (ref "PD43") (pin "4") (pinfunction "VDD_4") (pintype "power_in"))
      (node (ref "PD44") (pin "4") (pinfunction "VDD_4") (pintype "power_in"))
      (node (ref "PD45") (pin "4") (pinfunction "VDD_4") (pintype "power_in"))
      (node (ref "PD46") (pin "4") (pinfunction "VDD_4") (pintype "power_in"))
      (node (ref "PD47") (pin "4") (pinfunction "VDD_4") (pintype "power_in"))
      (node (ref "PD48") (pin "4") (pinfunction "VDD_4") (pintype "power_in"))
      (node (ref "PD49") (pin "4") (pinfunction "VDD_4") (pintype "power_in"))
      (node (ref "PD5") (pin "1") (pinfunction "VDD_1") (pintype "power_in"))
      (node (ref "PD50") (pin "4") (pinfunction "VDD_4") (pintype "power_in"))
      (node (ref "PD51") (pin "4") (pinfunction "VDD_4") (pintype "power_in"))
      (node (ref "PD52") (pin "4") (pinfunction "VDD_4") (pintype "power_in"))
      (node (ref "PD53") (pin "4") (pinfunction "VDD_4") (pintype "power_in"))
      (node (ref "PD54") (pin "4") (pinfunction "VDD_4") (pintype "power_in"))
      (node (ref "PD55") (pin "4") (pinfunction "VDD_4") (pintype "power_in"))
      (node (ref "PD56") (pin "4") (pinfunction "VDD_4") (pintype "power_in"))
      (node (ref "PD57") (pin "4") (pinfunction "VDD_4") (pintype "power_in"))
      (node (ref "PD58") (pin "4") (pinfunction "VDD_4") (pintype "power_in"))
      (node (ref "PD59") (pin "4") (pinfunction "VDD_4") (pintype "power_in"))
      (node (ref "PD6") (pin "1") (pinfunction "VDD_1") (pintype "power_in"))
      (node (ref "PD60") (pin "4") (pinfunction "VDD_4") (pintype "power_in"))
      (node (ref "PD61") (pin "4") (pinfunction "VDD_4") (pintype "power_in"))
      (node (ref "PD62") (pin "4") (pinfunction "VDD_4") (pintype "power_in"))
      (node (ref "PD63") (pin "4") (pinfunction "VDD_4") (pintype "power_in"))
      (node (ref "PD64") (pin "4") (pinfunction "VDD_4") (pintype "power_in"))
      (node (ref "PD65") (pin "4") (pinfunction "VDD_4") (pintype "power_in"))
      (node (ref "PD66") (pin "4") (pinfunction "VDD_4") (pintype "power_in"))
      (node (ref "PD67") (pin "4") (pinfunction "VDD_4") (pintype "power_in"))
      (node (ref "PD68") (pin "4") (pinfunction "VDD_4") (pintype "power_in"))
      (node (ref "PD69") (pin "4") (pinfunction "VDD_4") (pintype "power_in"))
      (node (ref "PD7") (pin "1") (pinfunction "VDD_1") (pintype "power_in"))
      (node (ref "PD70") (pin "4") (pinfunction "VDD_4") (pintype "power_in"))
      (node (ref "PD71") (pin "4") (pinfunction "VDD_4") (pintype "power_in"))
      (node (ref "PD72") (pin "4") (pinfunction "VDD_4") (pintype "power_in"))
      (node (ref "PD73") (pin "4") (pinfunction "VDD_4") (pintype "power_in"))
      (node (ref "PD74") (pin "4") (pinfunction "VDD_4") (pintype "power_in"))
      (node (ref "PD75") (pin "4") (pinfunction "VDD_4") (pintype "power_in"))
      (node (ref "PD76") (pin "4") (pinfunction "VDD_4") (pintype "power_in"))
      (node (ref "PD77") (pin "4") (pinfunction "VDD_4") (pintype "power_in"))
      (node (ref "PD78") (pin "4") (pinfunction "VDD_4") (pintype "power_in"))
      (node (ref "PD79") (pin "4") (pinfunction "VDD_4") (pintype "power_in"))
      (node (ref "PD8") (pin "1") (pinfunction "VDD_1") (pintype "power_in"))
      (node (ref "PD80") (pin "4") (pinfunction "VDD_4") (pintype "power_in"))
      (node (ref "PD81") (pin "4") (pinfunction "VDD_4") (pintype "power_in"))
      (node (ref "PD82") (pin "4") (pinfunction "VDD_4") (pintype "power_in"))
      (node (ref "PD83") (pin "4") (pinfunction "VDD_4") (pintype "power_in"))
      (node (ref "PD84") (pin "4") (pinfunction "VDD_4") (pintype "power_in"))
      (node (ref "PD85") (pin "4") (pinfunction "VDD_4") (pintype "power_in"))
      (node (ref "PD86") (pin "4") (pinfunction "VDD_4") (pintype "power_in"))
      (node (ref "PD87") (pin "4") (pinfunction "VDD_4") (pintype "power_in"))
      (node (ref "PD88") (pin "4") (pinfunction "VDD_4") (pintype "power_in"))
      (node (ref "PD89") (pin "4") (pinfunction "VDD_4") (pintype "power_in"))
      (node (ref "PD9") (pin "1") (pinfunction "VDD_1") (pintype "power_in"))
      (node (ref "PD90") (pin "4") (pinfunction "VDD_4") (pintype "power_in"))
      (node (ref "PD91") (pin "4") (pinfunction "VDD_4") (pintype "power_in"))
      (node (ref "PD92") (pin "4") (pinfunction "VDD_4") (pintype "power_in"))
      (node (ref "PD93") (pin "4") (pinfunction "VDD_4") (pintype "power_in"))
      (node (ref "PD94") (pin "4") (pinfunction "VDD_4") (pintype "power_in"))
      (node (ref "PD95") (pin "4") (pinfunction "VDD_4") (pintype "power_in"))
      (node (ref "PD96") (pin "4") (pinfunction "VDD_4") (pintype "power_in"))
      (node (ref "PD97") (pin "4") (pinfunction "VDD_4") (pintype "power_in"))
      (node (ref "PD98") (pin "4") (pinfunction "VDD_4") (pintype "power_in"))
      (node (ref "PD99") (pin "4") (pinfunction "VDD_4") (pintype "power_in"))
      (node (ref "R12") (pin "2") (pinfunction "2_2") (pintype "passive"))
      (node (ref "R13") (pin "2") (pinfunction "2_2") (pintype "passive"))
      (node (ref "R15") (pin "2") (pinfunction "2_2") (pintype "passive"))
      (node (ref "R16") (pin "2") (pinfunction "2_2") (pintype "passive"))
      (node (ref "R18") (pin "2") (pinfunction "2_2") (pintype "passive"))
      (node (ref "R19") (pin "2") (pinfunction "2_2") (pintype "passive"))
      (node (ref "R21") (pin "2") (pinfunction "2_2") (pintype "passive"))
      (node (ref "R22") (pin "2") (pinfunction "2_2") (pintype "passive"))
      (node (ref "R24") (pin "2") (pinfunction "2_2") (pintype "passive"))
      (node (ref "R25") (pin "2") (pinfunction "2_2") (pintype "passive"))
      (node (ref "R27") (pin "2") (pinfunction "2_2") (pintype "passive"))
      (node (ref "R28") (pin "2") (pinfunction "2_2") (pintype "passive"))
      (node (ref "R31") (pin "2") (pinfunction "2_2") (pintype "passive"))
      (node (ref "R32") (pin "2") (pinfunction "2_2") (pintype "passive"))
      (node (ref "SJ8") (pin "1") (pinfunction "1_1") (pintype "passive"))
      (node (ref "TP2") (pin "TP") (pinfunction "TP_TP") (pintype "input"))
      (node (ref "U5") (pin "3") (pinfunction "VOUT_3") (pintype "output"))
      (node (ref "V1") (pin "2") (pinfunction "+VIN_2") (pintype "passive"))
    )
    (net (code "3") (name "+12V") (class "Default")
      (node (ref "DISPLAY1") (pin "32") (pinfunction "VCC_32") (pintype "bidirectional"))
      (node (ref "L10") (pin "1") (pinfunction "1_1") (pintype "passive"))
      (node (ref "SJ1") (pin "2") (pinfunction "2_2") (pintype "passive"))
    )
    (net (code "4") (name "BL_PWM_1") (class "Default")
      (node (ref "R11") (pin "1") (pinfunction "1_1") (pintype "passive"))
      (node (ref "R8") (pin "1") (pinfunction "1_1") (pintype "passive"))
      (node (ref "U3") (pin "22") (pinfunction "PA6_22") (pintype "bidirectional"))
    )
    (net (code "5") (name "BL_PWM_2") (class "Default")
      (node (ref "R10") (pin "1") (pinfunction "1_1") (pintype "passive"))
      (node (ref "R7") (pin "1") (pinfunction "1_1") (pintype "passive"))
      (node (ref "U3") (pin "23") (pinfunction "PA7_23") (pintype "power_in"))
    )
    (net (code "6") (name "BL_PWM_3") (class "Default")
      (node (ref "R6") (pin "1") (pinfunction "1_1") (pintype "passive"))
      (node (ref "R9") (pin "1") (pinfunction "1_1") (pintype "passive"))
      (node (ref "U3") (pin "26") (pinfunction "PB0_26") (pintype "bidirectional"))
    )
    (net (code "7") (name "BOOT0") (class "Default")
      (node (ref "SJ6") (pin "2") (pinfunction "2_2") (pintype "passive"))
      (node (ref "U3") (pin "60") (pinfunction "BOOT0_60") (pintype "passive"))
    )
    (net (code "8") (name "BOOT1") (class "Default")
      (node (ref "SJ7") (pin "2") (pinfunction "2_2") (pintype "passive"))
      (node (ref "U3") (pin "28") (pinfunction "PB1_2_28") (pintype "bidirectional"))
    )
    (net (code "9") (name "CAN_H") (class "Default")
      (node (ref "D1") (pin "1") (pinfunction "1_1") (pintype "passive"))
      (node (ref "R4") (pin "2") (pinfunction "2_2") (pintype "passive"))
      (node (ref "U1") (pin "7") (pinfunction "CANH_7") (pintype "bidirectional"))
      (node (ref "X1") (pin "P$1") (pinfunction "1_P$1") (pintype "passive"))
      (node (ref "X2") (pin "P$1") (pinfunction "1_P$1") (pintype "passive"))
    )
    (net (code "10") (name "CAN_L") (class "Default")
      (node (ref "D1") (pin "2") (pinfunction "2_2") (pintype "passive"))
      (node (ref "R3") (pin "2") (pinfunction "2_2") (pintype "passive"))
      (node (ref "U1") (pin "6") (pinfunction "CANL_6") (pintype "bidirectional"))
      (node (ref "X1") (pin "P$2") (pinfunction "2_P$2") (pintype "passive"))
      (node (ref "X2") (pin "P$2") (pinfunction "2_P$2") (pintype "passive"))
    )
    (net (code "11") (name "CAN_RXD") (class "Default")
      (node (ref "U1") (pin "4") (pinfunction "RXD_4") (pintype "bidirectional"))
      (node (ref "U3") (pin "44") (pinfunction "PA11_44") (pintype "bidirectional"))
    )
    (net (code "12") (name "CAN_TXD") (class "Default")
      (node (ref "U1") (pin "1") (pinfunction "TXD_1") (pintype "bidirectional"))
      (node (ref "U3") (pin "45") (pinfunction "PA12_45") (pintype "bidirectional"))
    )
    (net (code "13") (name "DATA_WS") (class "Default")
      (node (ref "R56") (pin "2") (pinfunction "2_2") (pintype "passive"))
      (node (ref "U6") (pin "14") (pinfunction "PB1_14") (pintype "bidirectional"))
      (node (ref "U7") (pin "3") (pinfunction "A_3") (pintype "input"))
    )
    (net (code "14") (name "DATA_WS_IN1") (class "Default")
      (node (ref "PD1") (pin "4") (pinfunction "DIN_4") (pintype "input"))
      (node (ref "R57") (pin "2") (pinfunction "2_2") (pintype "passive"))
      (node (ref "U7") (pin "4") (pinfunction "B_4") (pintype "output"))
    )
    (net (code "15") (name "DATA_WS_IN2") (class "Default")
      (node (ref "PD16") (pin "2") (pinfunction "DOUT_2") (pintype "output"))
      (node (ref "PD17") (pin "3") (pinfunction "DIN_3") (pintype "input"))
    )
    (net (code "16") (name "EXT_RX") (class "Default")
      (node (ref "JP4") (pin "1") (pinfunction "1_1") (pintype "passive"))
      (node (ref "U3") (pin "43") (pinfunction "PA10_43") (pintype "bidirectional"))
    )
    (net (code "17") (name "EXT_TX") (class "Default")
      (node (ref "JP4") (pin "2") (pinfunction "2_2") (pintype "passive"))
      (node (ref "U3") (pin "42") (pinfunction "PA9_42") (pintype "bidirectional"))
    )
    (net (code "18") (name "GND") (class "Default")
      (node (ref "C1") (pin "-") (pinfunction "-_-") (pintype "passive"))
      (node (ref "C10") (pin "1") (pinfunction "1_1") (pintype "passive"))
      (node (ref "C11") (pin "1") (pinfunction "1_1") (pintype "passive"))
      (node (ref "C12") (pin "1") (pinfunction "1_1") (pintype "passive"))
      (node (ref "C13") (pin "1") (pinfunction "1_1") (pintype "passive"))
      (node (ref "C14") (pin "1") (pinfunction "1_1") (pintype "passive"))
      (node (ref "C15") (pin "1") (pinfunction "1_1") (pintype "passive"))
      (node (ref "C16") (pin "1") (pinfunction "1_1") (pintype "passive"))
      (node (ref "C17") (pin "1") (pinfunction "1_1") (pintype "passive"))
      (node (ref "C18") (pin "2") (pinfunction "2_2") (pintype "passive"))
      (node (ref "C19") (pin "2") (pinfunction "2_2") (pintype "passive"))
      (node (ref "C2") (pin "1") (pinfunction "1_1") (pintype "passive"))
      (node (ref "C20") (pin "2") (pinfunction "2_2") (pintype "passive"))
      (node (ref "C21") (pin "2") (pinfunction "2_2") (pintype "passive"))
      (node (ref "C22") (pin "2") (pinfunction "2_2") (pintype "passive"))
      (node (ref "C23") (pin "-") (pinfunction "-_-") (pintype "passive"))
      (node (ref "C24") (pin "2") (pinfunction "2_2") (pintype "passive"))
      (node (ref "C25") (pin "1") (pinfunction "1_1") (pintype "passive"))
      (node (ref "C26") (pin "-") (pinfunction "-_-") (pintype "passive"))
      (node (ref "C27") (pin "-") (pinfunction "-_-") (pintype "passive"))
      (node (ref "C28") (pin "2") (pinfunction "2_2") (pintype "passive"))
      (node (ref "C29") (pin "1") (pinfunction "1_1") (pintype "passive"))
      (node (ref "C3") (pin "1") (pinfunction "1_1") (pintype "passive"))
      (node (ref "C30") (pin "1") (pinfunction "1_1") (pintype "passive"))
      (node (ref "C31") (pin "1") (pinfunction "1_1") (pintype "passive"))
      (node (ref "C32") (pin "-") (pinfunction "-_-") (pintype "passive"))
      (node (ref "C33") (pin "-") (pinfunction "-_-") (pintype "passive"))
      (node (ref "C34") (pin "-") (pinfunction "-_-") (pintype "passive"))
      (node (ref "C35") (pin "1") (pinfunction "1_1") (pintype "passive"))
      (node (ref "C36") (pin "1") (pinfunction "1_1") (pintype "passive"))
      (node (ref "C37") (pin "1") (pinfunction "1_1") (pintype "passive"))
      (node (ref "C38") (pin "-") (pinfunction "-_-") (pintype "passive"))
      (node (ref "C39") (pin "1") (pinfunction "1_1") (pintype "passive"))
      (node (ref "C4") (pin "-") (pinfunction "-_-") (pintype "passive"))
      (node (ref "C40") (pin "2") (pinfunction "2_2") (pintype "passive"))
      (node (ref "C41") (pin "2") (pinfunction "2_2") (pintype "passive"))
      (node (ref "C42") (pin "2") (pinfunction "2_2") (pintype "passive"))
      (node (ref "C43") (pin "-") (pinfunction "-_-") (pintype "passive"))
      (node (ref "C44") (pin "1") (pinfunction "1_1") (pintype "passive"))
      (node (ref "C45") (pin "1") (pinfunction "1_1") (pintype "passive"))
      (node (ref "C5") (pin "1") (pinfunction "1_1") (pintype "passive"))
      (node (ref "C6") (pin "2") (pinfunction "2_2") (pintype "passive"))
      (node (ref "C7") (pin "-") (pinfunction "-_-") (pintype "passive"))
      (node (ref "C8") (pin "2") (pinfunction "2_2") (pintype "passive"))
      (node (ref "C9") (pin "2") (pinfunction "2_2") (pintype "passive"))
      (node (ref "D1") (pin "3") (pinfunction "3_3") (pintype "passive"))
      (node (ref "D2") (pin "A") (pinfunction "A_A") (pintype "passive"))
      (node (ref "D6") (pin "A") (pinfunction "A_A") (pintype "passive"))
      (node (ref "DISPLAY1") (pin "10") (pinfunction "BS1_10") (pintype "bidirectional"))
      (node (ref "DISPLAY1") (pin "11") (pinfunction "BS2_11") (pintype "bidirectional"))
      (node (ref "DISPLAY1") (pin "13") (pinfunction "CS#_13") (pintype "bidirectional"))
      (node (ref "DISPLAY1") (pin "16") (pinfunction "R/W#(WR#)_16") (pintype "bidirectional"))
      (node (ref "DISPLAY1") (pin "17") (pinfunction "E(RD#)_17") (pintype "bidirectional"))
      (node (ref "DISPLAY1") (pin "20") (pinfunction "D2_20") (pintype "bidirectional"))
      (node (ref "DISPLAY1") (pin "21") (pinfunction "D3_21") (pintype "bidirectional"))
      (node (ref "DISPLAY1") (pin "22") (pinfunction "D4_22") (pintype "bidirectional"))
      (node (ref "DISPLAY1") (pin "23") (pinfunction "D5_23") (pintype "bidirectional"))
      (node (ref "DISPLAY1") (pin "24") (pinfunction "D6_24") (pintype "bidirectional"))
      (node (ref "DISPLAY1") (pin "25") (pinfunction "D7_25") (pintype "bidirectional"))
      (node (ref "DISPLAY1") (pin "3") (pinfunction "VSS_3") (pintype "bidirectional"))
      (node (ref "DISPLAY1") (pin "4") (pinfunction "REGVDD_4") (pintype "bidirectional"))
      (node (ref "DISPLAY1") (pin "9") (pinfunction "BS0_9") (pintype "bidirectional"))
      (node (ref "IC1") (pin "12") (pinfunction "GND_12") (pintype "bidirectional"))
      (node (ref "IC1") (pin "21") (pinfunction "A2_21") (pintype "bidirectional"))
      (node (ref "JP1") (pin "3") (pinfunction "3_3") (pintype "passive"))
      (node (ref "JP2") (pin "2") (pinfunction "2_2") (pintype "passive"))
      (node (ref "JP3") (pin "3") (pinfunction "3_3") (pintype "passive"))
      (node (ref "P2") (pin "1") (pinfunction "1_1") (pintype "passive"))
      (node (ref "P3") (pin "1") (pinfunction "1_1") (pintype "passive"))
      (node (ref "P4") (pin "1") (pinfunction "1_1") (pintype "passive"))
      (node (ref "PD1") (pin "3") (pinfunction "VSS_3") (pintype "power_in"))
      (node (ref "PD10") (pin "3") (pinfunction "VSS_3") (pintype "power_in"))
      (node (ref "PD100") (pin "2") (pinfunction "VSS_2") (pintype "power_in"))
      (node (ref "PD101") (pin "2") (pinfunction "VSS_2") (pintype "power_in"))
      (node (ref "PD102") (pin "2") (pinfunction "VSS_2") (pintype "power_in"))
      (node (ref "PD103") (pin "2") (pinfunction "VSS_2") (pintype "power_in"))
      (node (ref "PD104") (pin "2") (pinfunction "VSS_2") (pintype "power_in"))
      (node (ref "PD105") (pin "2") (pinfunction "VSS_2") (pintype "power_in"))
      (node (ref "PD106") (pin "2") (pinfunction "VSS_2") (pintype "power_in"))
      (node (ref "PD107") (pin "2") (pinfunction "VSS_2") (pintype "power_in"))
      (node (ref "PD108") (pin "2") (pinfunction "VSS_2") (pintype "power_in"))
      (node (ref "PD109") (pin "2") (pinfunction "VSS_2") (pintype "power_in"))
      (node (ref "PD11") (pin "3") (pinfunction "VSS_3") (pintype "power_in"))
      (node (ref "PD110") (pin "2") (pinfunction "VSS_2") (pintype "power_in"))
      (node (ref "PD12") (pin "3") (pinfunction "VSS_3") (pintype "power_in"))
      (node (ref "PD13") (pin "3") (pinfunction "VSS_3") (pintype "power_in"))
      (node (ref "PD14") (pin "3") (pinfunction "VSS_3") (pintype "power_in"))
      (node (ref "PD15") (pin "3") (pinfunction "VSS_3") (pintype "power_in"))
      (node (ref "PD16") (pin "3") (pinfunction "VSS_3") (pintype "power_in"))
      (node (ref "PD17") (pin "2") (pinfunction "VSS_2") (pintype "power_in"))
      (node (ref "PD18") (pin "2") (pinfunction "VSS_2") (pintype "power_in"))
      (node (ref "PD19") (pin "2") (pinfunction "VSS_2") (pintype "power_in"))
      (node (ref "PD2") (pin "3") (pinfunction "VSS_3") (pintype "power_in"))
      (node (ref "PD20") (pin "2") (pinfunction "VSS_2") (pintype "power_in"))
      (node (ref "PD21") (pin "2") (pinfunction "VSS_2") (pintype "power_in"))
      (node (ref "PD22") (pin "2") (pinfunction "VSS_2") (pintype "power_in"))
      (node (ref "PD23") (pin "2") (pinfunction "VSS_2") (pintype "power_in"))
      (node (ref "PD24") (pin "2") (pinfunction "VSS_2") (pintype "power_in"))
      (node (ref "PD25") (pin "2") (pinfunction "VSS_2") (pintype "power_in"))
      (node (ref "PD26") (pin "2") (pinfunction "VSS_2") (pintype "power_in"))
      (node (ref "PD27") (pin "2") (pinfunction "VSS_2") (pintype "power_in"))
      (node (ref "PD28") (pin "2") (pinfunction "VSS_2") (pintype "power_in"))
      (node (ref "PD29") (pin "2") (pinfunction "VSS_2") (pintype "power_in"))
      (node (ref "PD3") (pin "3") (pinfunction "VSS_3") (pintype "power_in"))
      (node (ref "PD30") (pin "2") (pinfunction "VSS_2") (pintype "power_in"))
      (node (ref "PD31") (pin "2") (pinfunction "VSS_2") (pintype "power_in"))
      (node (ref "PD32") (pin "2") (pinfunction "VSS_2") (pintype "power_in"))
      (node (ref "PD33") (pin "2") (pinfunction "VSS_2") (pintype "power_in"))
      (node (ref "PD34") (pin "2") (pinfunction "VSS_2") (pintype "power_in"))
      (node (ref "PD35") (pin "2") (pinfunction "VSS_2") (pintype "power_in"))
      (node (ref "PD36") (pin "2") (pinfunction "VSS_2") (pintype "power_in"))
      (node (ref "PD37") (pin "2") (pinfunction "VSS_2") (pintype "power_in"))
      (node (ref "PD38") (pin "2") (pinfunction "VSS_2") (pintype "power_in"))
      (node (ref "PD39") (pin "2") (pinfunction "VSS_2") (pintype "power_in"))
      (node (ref "PD4") (pin "3") (pinfunction "VSS_3") (pintype "power_in"))
      (node (ref "PD40") (pin "2") (pinfunction "VSS_2") (pintype "power_in"))
      (node (ref "PD41") (pin "2") (pinfunction "VSS_2") (pintype "power_in"))
      (node (ref "PD42") (pin "2") (pinfunction "VSS_2") (pintype "power_in"))
      (node (ref "PD43") (pin "2") (pinfunction "VSS_2") (pintype "power_in"))
      (node (ref "PD44") (pin "2") (pinfunction "VSS_2") (pintype "power_in"))
      (node (ref "PD45") (pin "2") (pinfunction "VSS_2") (pintype "power_in"))
      (node (ref "PD46") (pin "2") (pinfunction "VSS_2") (pintype "power_in"))
      (node (ref "PD47") (pin "2") (pinfunction "VSS_2") (pintype "power_in"))
      (node (ref "PD48") (pin "2") (pinfunction "VSS_2") (pintype "power_in"))
      (node (ref "PD49") (pin "2") (pinfunction "VSS_2") (pintype "power_in"))
      (node (ref "PD5") (pin "3") (pinfunction "VSS_3") (pintype "power_in"))
      (node (ref "PD50") (pin "2") (pinfunction "VSS_2") (pintype "power_in"))
      (node (ref "PD51") (pin "2") (pinfunction "VSS_2") (pintype "power_in"))
      (node (ref "PD52") (pin "2") (pinfunction "VSS_2") (pintype "power_in"))
      (node (ref "PD53") (pin "2") (pinfunction "VSS_2") (pintype "power_in"))
      (node (ref "PD54") (pin "2") (pinfunction "VSS_2") (pintype "power_in"))
      (node (ref "PD55") (pin "2") (pinfunction "VSS_2") (pintype "power_in"))
      (node (ref "PD56") (pin "2") (pinfunction "VSS_2") (pintype "power_in"))
      (node (ref "PD57") (pin "2") (pinfunction "VSS_2") (pintype "power_in"))
      (node (ref "PD58") (pin "2") (pinfunction "VSS_2") (pintype "power_in"))
      (node (ref "PD59") (pin "2") (pinfunction "VSS_2") (pintype "power_in"))
      (node (ref "PD6") (pin "3") (pinfunction "VSS_3") (pintype "power_in"))
      (node (ref "PD60") (pin "2") (pinfunction "VSS_2") (pintype "power_in"))
      (node (ref "PD61") (pin "2") (pinfunction "VSS_2") (pintype "power_in"))
      (node (ref "PD62") (pin "2") (pinfunction "VSS_2") (pintype "power_in"))
      (node (ref "PD63") (pin "2") (pinfunction "VSS_2") (pintype "power_in"))
      (node (ref "PD64") (pin "2") (pinfunction "VSS_2") (pintype "power_in"))
      (node (ref "PD65") (pin "2") (pinfunction "VSS_2") (pintype "power_in"))
      (node (ref "PD66") (pin "2") (pinfunction "VSS_2") (pintype "power_in"))
      (node (ref "PD67") (pin "2") (pinfunction "VSS_2") (pintype "power_in"))
      (node (ref "PD68") (pin "2") (pinfunction "VSS_2") (pintype "power_in"))
      (node (ref "PD69") (pin "2") (pinfunction "VSS_2") (pintype "power_in"))
      (node (ref "PD7") (pin "3") (pinfunction "VSS_3") (pintype "power_in"))
      (node (ref "PD70") (pin "2") (pinfunction "VSS_2") (pintype "power_in"))
      (node (ref "PD71") (pin "2") (pinfunction "VSS_2") (pintype "power_in"))
      (node (ref "PD72") (pin "2") (pinfunction "VSS_2") (pintype "power_in"))
      (node (ref "PD73") (pin "2") (pinfunction "VSS_2") (pintype "power_in"))
      (node (ref "PD74") (pin "2") (pinfunction "VSS_2") (pintype "power_in"))
      (node (ref "PD75") (pin "2") (pinfunction "VSS_2") (pintype "power_in"))
      (node (ref "PD76") (pin "2") (pinfunction "VSS_2") (pintype "power_in"))
      (node (ref "PD77") (pin "2") (pinfunction "VSS_2") (pintype "power_in"))
      (node (ref "PD78") (pin "2") (pinfunction "VSS_2") (pintype "power_in"))
      (node (ref "PD79") (pin "2") (pinfunction "VSS_2") (pintype "power_in"))
      (node (ref "PD8") (pin "3") (pinfunction "VSS_3") (pintype "power_in"))
      (node (ref "PD80") (pin "2") (pinfunction "VSS_2") (pintype "power_in"))
      (node (ref "PD81") (pin "2") (pinfunction "VSS_2") (pintype "power_in"))
      (node (ref "PD82") (pin "2") (pinfunction "VSS_2") (pintype "power_in"))
      (node (ref "PD83") (pin "2") (pinfunction "VSS_2") (pintype "power_in"))
      (node (ref "PD84") (pin "2") (pinfunction "VSS_2") (pintype "power_in"))
      (node (ref "PD85") (pin "2") (pinfunction "VSS_2") (pintype "power_in"))
      (node (ref "PD86") (pin "2") (pinfunction "VSS_2") (pintype "power_in"))
      (node (ref "PD87") (pin "2") (pinfunction "VSS_2") (pintype "power_in"))
      (node (ref "PD88") (pin "2") (pinfunction "VSS_2") (pintype "power_in"))
      (node (ref "PD89") (pin "2") (pinfunction "VSS_2") (pintype "power_in"))
      (node (ref "PD9") (pin "3") (pinfunction "VSS_3") (pintype "power_in"))
      (node (ref "PD90") (pin "2") (pinfunction "VSS_2") (pintype "power_in"))
      (node (ref "PD91") (pin "2") (pinfunction "VSS_2") (pintype "power_in"))
      (node (ref "PD92") (pin "2") (pinfunction "VSS_2") (pintype "power_in"))
      (node (ref "PD93") (pin "2") (pinfunction "VSS_2") (pintype "power_in"))
      (node (ref "PD94") (pin "2") (pinfunction "VSS_2") (pintype "power_in"))
      (node (ref "PD95") (pin "2") (pinfunction "VSS_2") (pintype "power_in"))
      (node (ref "PD96") (pin "2") (pinfunction "VSS_2") (pintype "power_in"))
      (node (ref "PD97") (pin "2") (pinfunction "VSS_2") (pintype "power_in"))
      (node (ref "PD98") (pin "2") (pinfunction "VSS_2") (pintype "power_in"))
      (node (ref "PD99") (pin "2") (pinfunction "VSS_2") (pintype "power_in"))
      (node (ref "R2") (pin "1") (pinfunction "1_1") (pintype "passive"))
      (node (ref "R49") (pin "2") (pinfunction "2_2") (pintype "passive"))
      (node (ref "R51") (pin "2") (pinfunction "2_2") (pintype "passive"))
      (node (ref "R52") (pin "2") (pinfunction "2_2") (pintype "passive"))
      (node (ref "R56") (pin "1") (pinfunction "1_1") (pintype "passive"))
      (node (ref "R57") (pin "1") (pinfunction "1_1") (pintype "passive"))
      (node (ref "R6") (pin "2") (pinfunction "2_2") (pintype "passive"))
      (node (ref "R68") (pin "2") (pinfunction "2_2") (pintype "passive"))
      (node (ref "R7") (pin "2") (pinfunction "2_2") (pintype "passive"))
      (node (ref "R71") (pin "1") (pinfunction "1_1") (pintype "passive"))
      (node (ref "R8") (pin "2") (pinfunction "2_2") (pintype "passive"))
      (node (ref "SJ2") (pin "1") (pinfunction "1_1") (pintype "passive"))
      (node (ref "SJ3") (pin "1") (pinfunction "1_1") (pintype "passive"))
      (node (ref "SJ4") (pin "3") (pinfunction "3_3") (pintype "passive"))
      (node (ref "SJ5") (pin "3") (pinfunction "3_3") (pintype "passive"))
      (node (ref "SJ6") (pin "1") (pinfunction "1_1") (pintype "passive"))
      (node (ref "SJ7") (pin "1") (pinfunction "1_1") (pintype "passive"))
      (node (ref "T1") (pin "E") (pinfunction "E_E") (pintype "passive"))
      (node (ref "T2") (pin "E") (pinfunction "E_E") (pintype "passive"))
      (node (ref "T3") (pin "E") (pinfunction "E_E") (pintype "passive"))
      (node (ref "TP4") (pin "TP") (pinfunction "TP_TP") (pintype "input"))
      (node (ref "U1") (pin "2") (pinfunction "GND_2") (pintype "bidirectional"))
      (node (ref "U10") (pin "1") (pinfunction "GND_1") (pintype "power_in"))
      (node (ref "U11") (pin "1") (pinfunction "GND_1") (pintype "power_in"))
      (node (ref "U2") (pin "GND_1") (pinfunction "GND_1_GND_1") (pintype "bidirectional"))
      (node (ref "U2") (pin "GND_2") (pinfunction "GND_2_GND_2") (pintype "bidirectional"))
      (node (ref "U3") (pin "12") (pinfunction "VSSA_12") (pintype "passive"))
      (node (ref "U3") (pin "18") (pinfunction "VSS_4_18") (pintype "passive"))
      (node (ref "U3") (pin "31") (pinfunction "VSS_1_31") (pintype "passive"))
      (node (ref "U3") (pin "47") (pinfunction "VSS_2_47") (pintype "passive"))
      (node (ref "U3") (pin "63") (pinfunction "VSS_3_63") (pintype "passive"))
      (node (ref "U4") (pin "2") (pinfunction "GND_2") (pintype "power_in"))
      (node (ref "U5") (pin "2") (pinfunction "GND_2") (pintype "power_in"))
      (node (ref "U6") (pin "1") (pinfunction "BOOT0_1") (pintype "bidirectional"))
      (node (ref "U6") (pin "15") (pinfunction "VSS_15") (pintype "bidirectional"))
      (node (ref "U7") (pin "2") (pinfunction "GND_2") (pintype "passive"))
      (node (ref "U8") (pin "1") (pinfunction "A0_1") (pintype "input"))
      (node (ref "U8") (pin "2") (pinfunction "A1_2") (pintype "input"))
      (node (ref "U8") (pin "3") (pinfunction "A2_3") (pintype "input"))
      (node (ref "U8") (pin "4") (pinfunction "VSS_4") (pintype "passive"))
      (node (ref "U8") (pin "7") (pinfunction "WP_7") (pintype "input"))
      (node (ref "U9") (pin "1") (pinfunction "GND_1") (pintype "power_in"))
      (node (ref "V1") (pin "1") (pinfunction "-VIN_1") (pintype "passive"))
      (node (ref "V1") (pin "3") (pinfunction "-VOUT_3") (pintype "passive"))
      (node (ref "X3") (pin "P$2") (pinfunction "2_P$2") (pintype "passive"))
      (node (ref "X4") (pin "P$2") (pinfunction "2_P$2") (pintype "passive"))
      (node (ref "X6") (pin "11") (pinfunction "1_11") (pintype "passive"))
      (node (ref "X6") (pin "12") (pinfunction "1_12") (pintype "passive"))
      (node (ref "X6") (pin "17") (pinfunction "1_17") (pintype "passive"))
      (node (ref "X6") (pin "18") (pinfunction "1_18") (pintype "passive"))
      (node (ref "X6") (pin "2") (pinfunction "1_2") (pintype "passive"))
    )
    (net (code "19") (name "I2C_1_SCL") (class "Default")
      (node (ref "IC1") (pin "22") (pinfunction "SCL_22") (pintype "bidirectional"))
      (node (ref "R67") (pin "1") (pinfunction "1_1") (pintype "passive"))
      (node (ref "U3") (pin "58") (pinfunction "PB6_58") (pintype "bidirectional"))
    )
    (net (code "20") (name "I2C_1_SDA") (class "Default")
      (node (ref "IC1") (pin "23") (pinfunction "SDA_23") (pintype "bidirectional"))
      (node (ref "R66") (pin "1") (pinfunction "1_1") (pintype "passive"))
      (node (ref "U3") (pin "59") (pinfunction "PB7_59") (pintype "power_in"))
    )
    (net (code "21") (name "I2C_MUX_0") (class "Default")
      (node (ref "IC1") (pin "1") (pinfunction "A0_1") (pintype "bidirectional"))
      (node (ref "U3") (pin "62") (pinfunction "PB9_62") (pintype "bidirectional"))
    )
    (net (code "22") (name "I2C_MUX_1") (class "Default")
      (node (ref "IC1") (pin "2") (pinfunction "A1_2") (pintype "bidirectional"))
      (node (ref "U3") (pin "61") (pinfunction "PB8_61") (pintype "bidirectional"))
    )
    (net (code "23") (name "I2C_RESET") (class "Default")
      (node (ref "IC1") (pin "3") (pinfunction "RESET_3") (pintype "bidirectional"))
      (node (ref "R65") (pin "1") (pinfunction "1_1") (pintype "passive"))
      (node (ref "U3") (pin "50") (pinfunction "PA15_50") (pintype "bidirectional"))
    )
    (net (code "24") (name "IREF") (class "Default")
      (node (ref "R70") (pin "2") (pinfunction "2_2") (pintype "passive"))
      (node (ref "X6") (pin "27") (pinfunction "1_27") (pintype "passive"))
    )
    (net (code "25") (name "MCU1_NRST") (class "Default")
      (node (ref "C10") (pin "2") (pinfunction "2_2") (pintype "passive"))
      (node (ref "JP1") (pin "5") (pinfunction "5_5") (pintype "passive"))
      (node (ref "U3") (pin "7") (pinfunction "NRST_7") (pintype "output"))
    )
    (net (code "26") (name "MCU_2_RX") (class "Default")
      (node (ref "U3") (pin "29") (pinfunction "PB10_29") (pintype "bidirectional"))
      (node (ref "U6") (pin "9") (pinfunction "PA3_9") (pintype "bidirectional"))
    )
    (net (code "27") (name "MCU_2_TX") (class "Default")
      (node (ref "U3") (pin "30") (pinfunction "PB11_30") (pintype "bidirectional"))
      (node (ref "U6") (pin "8") (pinfunction "PA2_8") (pintype "bidirectional"))
    )
    (net (code "28") (name "N$177") (class "Default")
      (node (ref "R49") (pin "1") (pinfunction "1_1") (pintype "passive"))
      (node (ref "R50") (pin "2") (pinfunction "2_2") (pintype "passive"))
      (node (ref "X3") (pin "P$1") (pinfunction "1_P$1") (pintype "passive"))
      (node (ref "X4") (pin "P$1") (pinfunction "1_P$1") (pintype "passive"))
    )
    (net (code "29") (name "Net-(C3-Pad2)") (class "Default")
      (node (ref "C3") (pin "2") (pinfunction "2_2") (pintype "passive"))
      (node (ref "C4") (pin "+") (pinfunction "+_+") (pintype "passive"))
      (node (ref "L2") (pin "1") (pinfunction "1_1") (pintype "passive"))
      (node (ref "U2") (pin "VCC") (pinfunction "VCC_VCC") (pintype "bidirectional"))
    )
    (net (code "30") (name "Net-(C6-Pad1)") (class "Default")
      (node (ref "C6") (pin "1") (pinfunction "1_1") (pintype "passive"))
      (node (ref "R3") (pin "1") (pinfunction "1_1") (pintype "passive"))
      (node (ref "R4") (pin "1") (pinfunction "1_1") (pintype "passive"))
    )
    (net (code "31") (name "Net-(C12-Pad2)") (class "Default")
      (node (ref "C12") (pin "2") (pinfunction "2_2") (pintype "passive"))
      (node (ref "Q1") (pin "2") (pinfunction "2_2") (pintype "passive"))
      (node (ref "R5") (pin "1") (pinfunction "1_1") (pintype "passive"))
    )
    (net (code "32") (name "Net-(C24-Pad1)") (class "Default")
      (node (ref "C24") (pin "1") (pinfunction "1_1") (pintype "passive"))
      (node (ref "C26") (pin "+") (pinfunction "+_+") (pintype "passive"))
      (node (ref "D3") (pin "C") (pinfunction "C_C") (pintype "passive"))
      (node (ref "L4") (pin "1") (pinfunction "1_1") (pintype "passive"))
    )
    (net (code "33") (name "Net-(C34-Pad+)") (class "Default")
      (node (ref "C34") (pin "+") (pinfunction "+_+") (pintype "passive"))
      (node (ref "D5") (pin "C") (pinfunction "C_C") (pintype "passive"))
      (node (ref "D6") (pin "C") (pinfunction "C_C") (pintype "passive"))
      (node (ref "R52") (pin "1") (pinfunction "1_1") (pintype "passive"))
      (node (ref "SJ1") (pin "1") (pinfunction "1_1") (pintype "passive"))
      (node (ref "TP3") (pin "TP") (pinfunction "TP_TP") (pintype "input"))
    )
    (net (code "34") (name "Net-(D2-PadC)") (class "Default")
      (node (ref "D2") (pin "C") (pinfunction "C_C") (pintype "passive"))
      (node (ref "D3") (pin "A") (pinfunction "A_A") (pintype "passive"))
      (node (ref "R50") (pin "1") (pinfunction "1_1") (pintype "passive"))
      (node (ref "R51") (pin "1") (pinfunction "1_1") (pintype "passive"))
    )
    (net (code "35") (name "Net-(D4-PadC)") (class "Default")
      (node (ref "D4") (pin "C") (pinfunction "C_C") (pintype "passive"))
      (node (ref "D5") (pin "A") (pinfunction "A_A") (pintype "passive"))
    )
    (net (code "36") (name "Net-(DISPLAY1-IREF)") (class "Default")
      (node (ref "DISPLAY1") (pin "26") (pinfunction "IREF_26") (pintype "bidirectional"))
      (node (ref "R69") (pin "1") (pinfunction "1_1") (pintype "passive"))
    )
    (net (code "37") (name "Net-(DISPLAY1-OPR0)") (class "Default")
      (node (ref "DISPLAY1") (pin "29") (pinfunction "OPR0_29") (pintype "bidirectional"))
      (node (ref "SJ4") (pin "2") (pinfunction "2_2") (pintype "passive"))
    )
    (net (code "38") (name "Net-(DISPLAY1-OPR1)") (class "Default")
      (node (ref "DISPLAY1") (pin "30") (pinfunction "OPR1_30") (pintype "bidirectional"))
      (node (ref "SJ5") (pin "2") (pinfunction "2_2") (pintype "passive"))
    )
    (net (code "39") (name "Net-(DISPLAY1-ROM0)") (class "Default")
      (node (ref "DISPLAY1") (pin "27") (pinfunction "ROM0_27") (pintype "bidirectional"))
      (node (ref "SJ3") (pin "2") (pinfunction "2_2") (pintype "passive"))
    )
    (net (code "40") (name "Net-(DISPLAY1-ROM1)") (class "Default")
      (node (ref "DISPLAY1") (pin "28") (pinfunction "ROM1_28") (pintype "bidirectional"))
      (node (ref "SJ2") (pin "2") (pinfunction "2_2") (pintype "passive"))
    )
    (net (code "41") (name "Net-(DISPLAY1-VCOMH)") (class "Default")
      (node (ref "C44") (pin "2") (pinfunction "2_2") (pintype "passive"))
      (node (ref "DISPLAY1") (pin "31") (pinfunction "VCOMH_31") (pintype "bidirectional"))
    )
    (net (code "42") (name "Net-(L1-Pad2)") (class "Default")
      (node (ref "L1") (pin "2") (pinfunction "2_2") (pintype "passive"))
      (node (ref "SJ8") (pin "2") (pinfunction "2_2") (pintype "passive"))
    )
    (net (code "43") (name "Net-(L8-Pad2)") (class "Default")
      (node (ref "L8") (pin "2") (pinfunction "2_2") (pintype "passive"))
      (node (ref "SJ2") (pin "3") (pinfunction "3_3") (pintype "passive"))
      (node (ref "SJ3") (pin "3") (pinfunction "3_3") (pintype "passive"))
      (node (ref "SJ4") (pin "1") (pinfunction "1_1") (pintype "passive"))
      (node (ref "SJ5") (pin "1") (pinfunction "1_1") (pintype "passive"))
    )
    (net (code "44") (name "Net-(L9-Pad2)") (class "Default")
      (node (ref "L9") (pin "2") (pinfunction "2_2") (pintype "passive"))
      (node (ref "V2") (pin "A") (pinfunction "A_A") (pintype "passive"))
    )
    (net (code "45") (name "Net-(LED1-PadA)") (class "Default")
      (node (ref "LED1") (pin "A") (pinfunction "A_A") (pintype "passive"))
      (node (ref "R12") (pin "1") (pinfunction "1_1") (pintype "passive"))
    )
    (net (code "46") (name "Net-(LED1-PadC)") (class "Default")
      (node (ref "LED1") (pin "C") (pinfunction "C_C") (pintype "passive"))
      (node (ref "LED10") (pin "C") (pinfunction "C_C") (pintype "passive"))
      (node (ref "LED13") (pin "C") (pinfunction "C_C") (pintype "passive"))
      (node (ref "LED16") (pin "C") (pinfunction "C_C") (pintype "passive"))
      (node (ref "LED21") (pin "C") (pinfunction "C_C") (pintype "passive"))
      (node (ref "LED4") (pin "C") (pinfunction "C_C") (pintype "passive"))
      (node (ref "LED7") (pin "C") (pinfunction "C_C") (pintype "passive"))
      (node (ref "T1") (pin "C") (pinfunction "C_C") (pintype "passive"))
    )
    (net (code "47") (name "Net-(LED2-PadA)") (class "Default")
      (node (ref "LED2") (pin "A") (pinfunction "A_A") (pintype "passive"))
      (node (ref "R13") (pin "1") (pinfunction "1_1") (pintype "passive"))
    )
    (net (code "48") (name "Net-(LED3-PadA)") (class "Default")
      (node (ref "LED3") (pin "A") (pinfunction "A_A") (pintype "passive"))
      (node (ref "R14") (pin "1") (pinfunction "1_1") (pintype "passive"))
    )
    (net (code "49") (name "Net-(LED4-PadA)") (class "Default")
      (node (ref "LED4") (pin "A") (pinfunction "A_A") (pintype "passive"))
      (node (ref "R15") (pin "1") (pinfunction "1_1") (pintype "passive"))
    )
    (net (code "50") (name "Net-(LED5-PadA)") (class "Default")
      (node (ref "LED5") (pin "A") (pinfunction "A_A") (pintype "passive"))
      (node (ref "R16") (pin "1") (pinfunction "1_1") (pintype "passive"))
    )
    (net (code "51") (name "Net-(LED6-PadA)") (class "Default")
      (node (ref "LED6") (pin "A") (pinfunction "A_A") (pintype "passive"))
      (node (ref "R17") (pin "1") (pinfunction "1_1") (pintype "passive"))
    )
    (net (code "52") (name "Net-(LED7-PadA)") (class "Default")
      (node (ref "LED7") (pin "A") (pinfunction "A_A") (pintype "passive"))
      (node (ref "R18") (pin "1") (pinfunction "1_1") (pintype "passive"))
    )
    (net (code "53") (name "Net-(LED8-PadA)") (class "Default")
      (node (ref "LED8") (pin "A") (pinfunction "A_A") (pintype "passive"))
      (node (ref "R19") (pin "1") (pinfunction "1_1") (pintype "passive"))
    )
    (net (code "54") (name "Net-(LED9-PadA)") (class "Default")
      (node (ref "LED9") (pin "A") (pinfunction "A_A") (pintype "passive"))
      (node (ref "R20") (pin "1") (pinfunction "1_1") (pintype "passive"))
    )
    (net (code "55") (name "Net-(LED10-PadA)") (class "Default")
      (node (ref "LED10") (pin "A") (pinfunction "A_A") (pintype "passive"))
      (node (ref "R21") (pin "1") (pinfunction "1_1") (pintype "passive"))
    )
    (net (code "56") (name "Net-(LED11-PadA)") (class "Default")
      (node (ref "LED11") (pin "A") (pinfunction "A_A") (pintype "passive"))
      (node (ref "R22") (pin "1") (pinfunction "1_1") (pintype "passive"))
    )
    (net (code "57") (name "Net-(LED11-PadC)") (class "Default")
      (node (ref "LED11") (pin "C") (pinfunction "C_C") (pintype "passive"))
      (node (ref "LED14") (pin "C") (pinfunction "C_C") (pintype "passive"))
      (node (ref "LED17") (pin "C") (pinfunction "C_C") (pintype "passive"))
      (node (ref "LED2") (pin "C") (pinfunction "C_C") (pintype "passive"))
      (node (ref "LED20") (pin "C") (pinfunction "C_C") (pintype "passive"))
      (node (ref "LED5") (pin "C") (pinfunction "C_C") (pintype "passive"))
      (node (ref "LED8") (pin "C") (pinfunction "C_C") (pintype "passive"))
      (node (ref "T2") (pin "C") (pinfunction "C_C") (pintype "passive"))
    )
    (net (code "58") (name "Net-(LED12-PadA)") (class "Default")
      (node (ref "LED12") (pin "A") (pinfunction "A_A") (pintype "passive"))
      (node (ref "R23") (pin "1") (pinfunction "1_1") (pintype "passive"))
    )
    (net (code "59") (name "Net-(LED12-PadC)") (class "Default")
      (node (ref "LED12") (pin "C") (pinfunction "C_C") (pintype "passive"))
      (node (ref "LED15") (pin "C") (pinfunction "C_C") (pintype "passive"))
      (node (ref "LED18") (pin "C") (pinfunction "C_C") (pintype "passive"))
      (node (ref "LED19") (pin "C") (pinfunction "C_C") (pintype "passive"))
      (node (ref "LED22") (pin "C") (pinfunction "C_C") (pintype "passive"))
      (node (ref "LED23") (pin "C") (pinfunction "C_C") (pintype "passive"))
      (node (ref "LED24") (pin "C") (pinfunction "C_C") (pintype "passive"))
      (node (ref "LED25") (pin "C") (pinfunction "C_C") (pintype "passive"))
      (node (ref "LED26") (pin "C") (pinfunction "C_C") (pintype "passive"))
      (node (ref "LED27") (pin "C") (pinfunction "C_C") (pintype "passive"))
      (node (ref "LED28") (pin "C") (pinfunction "C_C") (pintype "passive"))
      (node (ref "LED29") (pin "C") (pinfunction "C_C") (pintype "passive"))
      (node (ref "LED3") (pin "C") (pinfunction "C_C") (pintype "passive"))
      (node (ref "LED30") (pin "C") (pinfunction "C_C") (pintype "passive"))
      (node (ref "LED31") (pin "C") (pinfunction "C_C") (pintype "passive"))
      (node (ref "LED32") (pin "C") (pinfunction "C_C") (pintype "passive"))
      (node (ref "LED33") (pin "C") (pinfunction "C_C") (pintype "passive"))
      (node (ref "LED34") (pin "C") (pinfunction "C_C") (pintype "passive"))
      (node (ref "LED35") (pin "C") (pinfunction "C_C") (pintype "passive"))
      (node (ref "LED36") (pin "C") (pinfunction "C_C") (pintype "passive"))
      (node (ref "LED37") (pin "C") (pinfunction "C_C") (pintype "passive"))
      (node (ref "LED6") (pin "C") (pinfunction "C_C") (pintype "passive"))
      (node (ref "LED9") (pin "C") (pinfunction "C_C") (pintype "passive"))
      (node (ref "T3") (pin "C") (pinfunction "C_C") (pintype "passive"))
    )
    (net (code "60") (name "Net-(LED13-PadA)") (class "Default")
      (node (ref "LED13") (pin "A") (pinfunction "A_A") (pintype "passive"))
      (node (ref "R24") (pin "1") (pinfunction "1_1") (pintype "passive"))
    )
    (net (code "61") (name "Net-(LED14-PadA)") (class "Default")
      (node (ref "LED14") (pin "A") (pinfunction "A_A") (pintype "passive"))
      (node (ref "R25") (pin "1") (pinfunction "1_1") (pintype "passive"))
    )
    (net (code "62") (name "Net-(LED15-PadA)") (class "Default")
      (node (ref "LED15") (pin "A") (pinfunction "A_A") (pintype "passive"))
      (node (ref "R26") (pin "1") (pinfunction "1_1") (pintype "passive"))
    )
    (net (code "63") (name "Net-(LED16-PadA)") (class "Default")
      (node (ref "LED16") (pin "A") (pinfunction "A_A") (pintype "passive"))
      (node (ref "R27") (pin "1") (pinfunction "1_1") (pintype "passive"))
    )
    (net (code "64") (name "Net-(LED17-PadA)") (class "Default")
      (node (ref "LED17") (pin "A") (pinfunction "A_A") (pintype "passive"))
      (node (ref "R28") (pin "1") (pinfunction "1_1") (pintype "passive"))
    )
    (net (code "65") (name "Net-(LED18-PadA)") (class "Default")
      (node (ref "LED18") (pin "A") (pinfunction "A_A") (pintype "passive"))
      (node (ref "R29") (pin "1") (pinfunction "1_1") (pintype "passive"))
    )
    (net (code "66") (name "Net-(LED19-PadA)") (class "Default")
      (node (ref "LED19") (pin "A") (pinfunction "A_A") (pintype "passive"))
      (node (ref "R30") (pin "1") (pinfunction "1_1") (pintype "passive"))
    )
    (net (code "67") (name "Net-(LED20-PadA)") (class "Default")
      (node (ref "LED20") (pin "A") (pinfunction "A_A") (pintype "passive"))
      (node (ref "R31") (pin "1") (pinfunction "1_1") (pintype "passive"))
    )
    (net (code "68") (name "Net-(LED21-PadA)") (class "Default")
      (node (ref "LED21") (pin "A") (pinfunction "A_A") (pintype "passive"))
      (node (ref "R32") (pin "1") (pinfunction "1_1") (pintype "passive"))
    )
    (net (code "69") (name "Net-(LED22-PadA)") (class "Default")
      (node (ref "LED22") (pin "A") (pinfunction "A_A") (pintype "passive"))
      (node (ref "R33") (pin "1") (pinfunction "1_1") (pintype "passive"))
    )
    (net (code "70") (name "Net-(LED23-PadA)") (class "Default")
      (node (ref "LED23") (pin "A") (pinfunction "A_A") (pintype "passive"))
      (node (ref "R34") (pin "1") (pinfunction "1_1") (pintype "passive"))
    )
    (net (code "71") (name "Net-(LED24-PadA)") (class "Default")
      (node (ref "LED24") (pin "A") (pinfunction "A_A") (pintype "passive"))
      (node (ref "R35") (pin "1") (pinfunction "1_1") (pintype "passive"))
    )
    (net (code "72") (name "Net-(LED25-PadA)") (class "Default")
      (node (ref "LED25") (pin "A") (pinfunction "A_A") (pintype "passive"))
      (node (ref "R36") (pin "1") (pinfunction "1_1") (pintype "passive"))
    )
    (net (code "73") (name "Net-(LED26-PadA)") (class "Default")
      (node (ref "LED26") (pin "A") (pinfunction "A_A") (pintype "passive"))
      (node (ref "R37") (pin "1") (pinfunction "1_1") (pintype "passive"))
    )
    (net (code "74") (name "Net-(LED27-PadA)") (class "Default")
      (node (ref "LED27") (pin "A") (pinfunction "A_A") (pintype "passive"))
      (node (ref "R38") (pin "1") (pinfunction "1_1") (pintype "passive"))
    )
    (net (code "75") (name "Net-(LED28-PadA)") (class "Default")
      (node (ref "LED28") (pin "A") (pinfunction "A_A") (pintype "passive"))
      (node (ref "R39") (pin "1") (pinfunction "1_1") (pintype "passive"))
    )
    (net (code "76") (name "Net-(LED29-PadA)") (class "Default")
      (node (ref "LED29") (pin "A") (pinfunction "A_A") (pintype "passive"))
      (node (ref "R40") (pin "1") (pinfunction "1_1") (pintype "passive"))
    )
    (net (code "77") (name "Net-(LED30-PadA)") (class "Default")
      (node (ref "LED30") (pin "A") (pinfunction "A_A") (pintype "passive"))
      (node (ref "R41") (pin "1") (pinfunction "1_1") (pintype "passive"))
    )
    (net (code "78") (name "Net-(LED31-PadA)") (class "Default")
      (node (ref "LED31") (pin "A") (pinfunction "A_A") (pintype "passive"))
      (node (ref "R42") (pin "1") (pinfunction "1_1") (pintype "passive"))
    )
    (net (code "79") (name "Net-(LED32-PadA)") (class "Default")
      (node (ref "LED32") (pin "A") (pinfunction "A_A") (pintype "passive"))
      (node (ref "R43") (pin "1") (pinfunction "1_1") (pintype "passive"))
    )
    (net (code "80") (name "Net-(LED33-PadA)") (class "Default")
      (node (ref "LED33") (pin "A") (pinfunction "A_A") (pintype "passive"))
      (node (ref "R44") (pin "1") (pinfunction "1_1") (pintype "passive"))
    )
    (net (code "81") (name "Net-(LED34-PadA)") (class "Default")
      (node (ref "LED34") (pin "A") (pinfunction "A_A") (pintype "passive"))
      (node (ref "R45") (pin "1") (pinfunction "1_1") (pintype "passive"))
    )
    (net (code "82") (name "Net-(LED35-PadA)") (class "Default")
      (node (ref "LED35") (pin "A") (pinfunction "A_A") (pintype "passive"))
      (node (ref "R46") (pin "1") (pinfunction "1_1") (pintype "passive"))
    )
    (net (code "83") (name "Net-(LED36-PadA)") (class "Default")
      (node (ref "LED36") (pin "A") (pinfunction "A_A") (pintype "passive"))
      (node (ref "R47") (pin "1") (pinfunction "1_1") (pintype "passive"))
    )
    (net (code "84") (name "Net-(LED37-PadA)") (class "Default")
      (node (ref "LED37") (pin "A") (pinfunction "A_A") (pintype "passive"))
      (node (ref "R48") (pin "1") (pinfunction "1_1") (pintype "passive"))
    )
    (net (code "85") (name "Net-(PD1-DOUT)") (class "Default")
      (node (ref "PD1") (pin "2") (pinfunction "DOUT_2") (pintype "output"))
      (node (ref "PD2") (pin "4") (pinfunction "DIN_4") (pintype "input"))
    )
    (net (code "86") (name "Net-(PD2-DOUT)") (class "Default")
      (node (ref "PD2") (pin "2") (pinfunction "DOUT_2") (pintype "output"))
      (node (ref "PD3") (pin "4") (pinfunction "DIN_4") (pintype "input"))
    )
    (net (code "87") (name "Net-(PD3-DOUT)") (class "Default")
      (node (ref "PD3") (pin "2") (pinfunction "DOUT_2") (pintype "output"))
      (node (ref "PD4") (pin "4") (pinfunction "DIN_4") (pintype "input"))
    )
    (net (code "88") (name "Net-(PD4-DOUT)") (class "Default")
      (node (ref "PD4") (pin "2") (pinfunction "DOUT_2") (pintype "output"))
      (node (ref "PD5") (pin "4") (pinfunction "DIN_4") (pintype "input"))
    )
    (net (code "89") (name "Net-(PD5-DOUT)") (class "Default")
      (node (ref "PD5") (pin "2") (pinfunction "DOUT_2") (pintype "output"))
      (node (ref "PD6") (pin "4") (pinfunction "DIN_4") (pintype "input"))
    )
    (net (code "90") (name "Net-(PD6-DOUT)") (class "Default")
      (node (ref "PD6") (pin "2") (pinfunction "DOUT_2") (pintype "output"))
      (node (ref "PD7") (pin "4") (pinfunction "DIN_4") (pintype "input"))
    )
    (net (code "91") (name "Net-(PD7-DOUT)") (class "Default")
      (node (ref "PD7") (pin "2") (pinfunction "DOUT_2") (pintype "output"))
      (node (ref "PD8") (pin "4") (pinfunction "DIN_4") (pintype "input"))
    )
    (net (code "92") (name "Net-(PD8-DOUT)") (class "Default")
      (node (ref "PD8") (pin "2") (pinfunction "DOUT_2") (pintype "output"))
      (node (ref "PD9") (pin "4") (pinfunction "DIN_4") (pintype "input"))
    )
    (net (code "93") (name "Net-(PD10-DIN)") (class "Default")
      (node (ref "PD10") (pin "4") (pinfunction "DIN_4") (pintype "input"))
      (node (ref "PD9") (pin "2") (pinfunction "DOUT_2") (pintype "output"))
    )
    (net (code "94") (name "Net-(PD10-DOUT)") (class "Default")
      (node (ref "PD10") (pin "2") (pinfunction "DOUT_2") (pintype "output"))
      (node (ref "PD11") (pin "4") (pinfunction "DIN_4") (pintype "input"))
    )
    (net (code "95") (name "Net-(PD11-DOUT)") (class "Default")
      (node (ref "PD11") (pin "2") (pinfunction "DOUT_2") (pintype "output"))
      (node (ref "PD12") (pin "4") (pinfunction "DIN_4") (pintype "input"))
    )
    (net (code "96") (name "Net-(PD12-DOUT)") (class "Default")
      (node (ref "PD12") (pin "2") (pinfunction "DOUT_2") (pintype "output"))
      (node (ref "PD13") (pin "4") (pinfunction "DIN_4") (pintype "input"))
    )
    (net (code "97") (name "Net-(PD13-DOUT)") (class "Default")
      (node (ref "PD13") (pin "2") (pinfunction "DOUT_2") (pintype "output"))
      (node (ref "PD14") (pin "4") (pinfunction "DIN_4") (pintype "input"))
    )
    (net (code "98") (name "Net-(PD14-DOUT)") (class "Default")
      (node (ref "PD14") (pin "2") (pinfunction "DOUT_2") (pintype "output"))
      (node (ref "PD15") (pin "4") (pinfunction "DIN_4") (pintype "input"))
    )
    (net (code "99") (name "Net-(PD15-DOUT)") (class "Default")
      (node (ref "PD15") (pin "2") (pinfunction "DOUT_2") (pintype "output"))
      (node (ref "PD16") (pin "4") (pinfunction "DIN_4") (pintype "input"))
    )
    (net (code "100") (name "Net-(PD17-DOUT)") (class "Default")
      (node (ref "PD17") (pin "1") (pinfunction "DOUT_1") (pintype "output"))
      (node (ref "PD18") (pin "3") (pinfunction "DIN_3") (pintype "input"))
    )
    (net (code "101") (name "Net-(PD18-DOUT)") (class "Default")
      (node (ref "PD18") (pin "1") (pinfunction "DOUT_1") (pintype "output"))
      (node (ref "PD19") (pin "3") (pinfunction "DIN_3") (pintype "input"))
    )
    (net (code "102") (name "Net-(PD19-DOUT)") (class "Default")
      (node (ref "PD19") (pin "1") (pinfunction "DOUT_1") (pintype "output"))
      (node (ref "PD20") (pin "3") (pinfunction "DIN_3") (pintype "input"))
    )
    (net (code "103") (name "Net-(PD20-DOUT)") (class "Default")
      (node (ref "PD20") (pin "1") (pinfunction "DOUT_1") (pintype "output"))
      (node (ref "PD21") (pin "3") (pinfunction "DIN_3") (pintype "input"))
    )
    (net (code "104") (name "Net-(PD21-DOUT)") (class "Default")
      (node (ref "PD21") (pin "1") (pinfunction "DOUT_1") (pintype "output"))
      (node (ref "PD22") (pin "3") (pinfunction "DIN_3") (pintype "input"))
    )
    (net (code "105") (name "Net-(PD22-DOUT)") (class "Default")
      (node (ref "PD22") (pin "1") (pinfunction "DOUT_1") (pintype "output"))
      (node (ref "PD23") (pin "3") (pinfunction "DIN_3") (pintype "input"))
    )
    (net (code "106") (name "Net-(PD23-DOUT)") (class "Default")
      (node (ref "PD23") (pin "1") (pinfunction "DOUT_1") (pintype "output"))
      (node (ref "PD24") (pin "3") (pinfunction "DIN_3") (pintype "input"))
    )
    (net (code "107") (name "Net-(PD24-DOUT)") (class "Default")
      (node (ref "PD24") (pin "1") (pinfunction "DOUT_1") (pintype "output"))
      (node (ref "PD25") (pin "3") (pinfunction "DIN_3") (pintype "input"))
    )
    (net (code "108") (name "Net-(PD25-DOUT)") (class "Default")
      (node (ref "PD25") (pin "1") (pinfunction "DOUT_1") (pintype "output"))
      (node (ref "PD26") (pin "3") (pinfunction "DIN_3") (pintype "input"))
    )
    (net (code "109") (name "Net-(PD26-DOUT)") (class "Default")
      (node (ref "PD26") (pin "1") (pinfunction "DOUT_1") (pintype "output"))
      (node (ref "PD27") (pin "3") (pinfunction "DIN_3") (pintype "input"))
    )
    (net (code "110") (name "Net-(PD27-DOUT)") (class "Default")
      (node (ref "PD27") (pin "1") (pinfunction "DOUT_1") (pintype "output"))
      (node (ref "PD28") (pin "3") (pinfunction "DIN_3") (pintype "input"))
    )
    (net (code "111") (name "Net-(PD28-DOUT)") (class "Default")
      (node (ref "PD28") (pin "1") (pinfunction "DOUT_1") (pintype "output"))
      (node (ref "PD29") (pin "3") (pinfunction "DIN_3") (pintype "input"))
    )
    (net (code "112") (name "Net-(PD29-DOUT)") (class "Default")
      (node (ref "PD29") (pin "1") (pinfunction "DOUT_1") (pintype "output"))
      (node (ref "PD30") (pin "3") (pinfunction "DIN_3") (pintype "input"))
    )
    (net (code "113") (name "Net-(PD30-DOUT)") (class "Default")
      (node (ref "PD30") (pin "1") (pinfunction "DOUT_1") (pintype "output"))
      (node (ref "PD31") (pin "3") (pinfunction "DIN_3") (pintype "input"))
    )
    (net (code "114") (name "Net-(PD31-DOUT)") (class "Default")
      (node (ref "PD31") (pin "1") (pinfunction "DOUT_1") (pintype "output"))
      (node (ref "PD32") (pin "3") (pinfunction "DIN_3") (pintype "input"))
    )
    (net (code "115") (name "Net-(PD32-DOUT)") (class "Default")
      (node (ref "PD32") (pin "1") (pinfunction "DOUT_1") (pintype "output"))
      (node (ref "PD33") (pin "3") (pinfunction "DIN_3") (pintype "input"))
    )
    (net (code "116") (name "Net-(PD33-DOUT)") (class "Default")
      (node (ref "PD33") (pin "1") (pinfunction "DOUT_1") (pintype "output"))
      (node (ref "PD34") (pin "3") (pinfunction "DIN_3") (pintype "input"))
    )
    (net (code "117") (name "Net-(PD34-DOUT)") (class "Default")
      (node (ref "PD34") (pin "1") (pinfunction "DOUT_1") (pintype "output"))
      (node (ref "PD35") (pin "3") (pinfunction "DIN_3") (pintype "input"))
    )
    (net (code "118") (name "Net-(PD35-DOUT)") (class "Default")
      (node (ref "PD35") (pin "1") (pinfunction "DOUT_1") (pintype "output"))
      (node (ref "PD36") (pin "3") (pinfunction "DIN_3") (pintype "input"))
    )
    (net (code "119") (name "Net-(PD36-DOUT)") (class "Default")
      (node (ref "PD36") (pin "1") (pinfunction "DOUT_1") (pintype "output"))
      (node (ref "PD37") (pin "3") (pinfunction "DIN_3") (pintype "input"))
    )
    (net (code "120") (name "Net-(PD37-DOUT)") (class "Default")
      (node (ref "PD37") (pin "1") (pinfunction "DOUT_1") (pintype "output"))
      (node (ref "PD38") (pin "3") (pinfunction "DIN_3") (pintype "input"))
    )
    (net (code "121") (name "Net-(PD38-DOUT)") (class "Default")
      (node (ref "PD38") (pin "1") (pinfunction "DOUT_1") (pintype "output"))
      (node (ref "PD39") (pin "3") (pinfunction "DIN_3") (pintype "input"))
    )
    (net (code "122") (name "Net-(PD39-DOUT)") (class "Default")
      (node (ref "PD39") (pin "1") (pinfunction "DOUT_1") (pintype "output"))
      (node (ref "PD40") (pin "3") (pinfunction "DIN_3") (pintype "input"))
    )
    (net (code "123") (name "Net-(PD40-DOUT)") (class "Default")
      (node (ref "PD40") (pin "1") (pinfunction "DOUT_1") (pintype "output"))
      (node (ref "PD41") (pin "3") (pinfunction "DIN_3") (pintype "input"))
    )
    (net (code "124") (name "Net-(PD41-DOUT)") (class "Default")
      (node (ref "PD41") (pin "1") (pinfunction "DOUT_1") (pintype "output"))
      (node (ref "PD42") (pin "3") (pinfunction "DIN_3") (pintype "input"))
    )
    (net (code "125") (name "Net-(PD42-DOUT)") (class "Default")
      (node (ref "PD42") (pin "1") (pinfunction "DOUT_1") (pintype "output"))
      (node (ref "PD43") (pin "3") (pinfunction "DIN_3") (pintype "input"))
    )
    (net (code "126") (name "Net-(PD43-DOUT)") (class "Default")
      (node (ref "PD43") (pin "1") (pinfunction "DOUT_1") (pintype "output"))
      (node (ref "PD44") (pin "3") (pinfunction "DIN_3") (pintype "input"))
    )
    (net (code "127") (name "Net-(PD44-DOUT)") (class "Default")
      (node (ref "PD44") (pin "1") (pinfunction "DOUT_1") (pintype "output"))
      (node (ref "PD45") (pin "3") (pinfunction "DIN_3") (pintype "input"))
    )
    (net (code "128") (name "Net-(PD45-DOUT)") (class "Default")
      (node (ref "PD45") (pin "1") (pinfunction "DOUT_1") (pintype "output"))
      (node (ref "PD46") (pin "3") (pinfunction "DIN_3") (pintype "input"))
    )
    (net (code "129") (name "Net-(PD46-DOUT)") (class "Default")
      (node (ref "PD46") (pin "1") (pinfunction "DOUT_1") (pintype "output"))
      (node (ref "PD47") (pin "3") (pinfunction "DIN_3") (pintype "input"))
    )
    (net (code "130") (name "Net-(PD47-DOUT)") (class "Default")
      (node (ref "PD47") (pin "1") (pinfunction "DOUT_1") (pintype "output"))
      (node (ref "PD48") (pin "3") (pinfunction "DIN_3") (pintype "input"))
    )
    (net (code "131") (name "Net-(PD48-DOUT)") (class "Default")
      (node (ref "PD48") (pin "1") (pinfunction "DOUT_1") (pintype "output"))
      (node (ref "PD49") (pin "3") (pinfunction "DIN_3") (pintype "input"))
    )
    (net (code "132") (name "Net-(PD49-DOUT)") (class "Default")
      (node (ref "PD49") (pin "1") (pinfunction "DOUT_1") (pintype "output"))
      (node (ref "PD50") (pin "3") (pinfunction "DIN_3") (pintype "input"))
    )
    (net (code "133") (name "Net-(PD50-DOUT)") (class "Default")
      (node (ref "PD50") (pin "1") (pinfunction "DOUT_1") (pintype "output"))
      (node (ref "PD51") (pin "3") (pinfunction "DIN_3") (pintype "input"))
    )
    (net (code "134") (name "Net-(PD51-DOUT)") (class "Default")
      (node (ref "PD51") (pin "1") (pinfunction "DOUT_1") (pintype "output"))
      (node (ref "PD52") (pin "3") (pinfunction "DIN_3") (pintype "input"))
    )
    (net (code "135") (name "Net-(PD52-DOUT)") (class "Default")
      (node (ref "PD52") (pin "1") (pinfunction "DOUT_1") (pintype "output"))
      (node (ref "PD53") (pin "3") (pinfunction "DIN_3") (pintype "input"))
    )
    (net (code "136") (name "Net-(PD53-DOUT)") (class "Default")
      (node (ref "PD53") (pin "1") (pinfunction "DOUT_1") (pintype "output"))
      (node (ref "PD54") (pin "3") (pinfunction "DIN_3") (pintype "input"))
    )
    (net (code "137") (name "Net-(PD54-DOUT)") (class "Default")
      (node (ref "PD54") (pin "1") (pinfunction "DOUT_1") (pintype "output"))
      (node (ref "PD55") (pin "3") (pinfunction "DIN_3") (pintype "input"))
    )
    (net (code "138") (name "Net-(PD55-DOUT)") (class "Default")
      (node (ref "PD55") (pin "1") (pinfunction "DOUT_1") (pintype "output"))
      (node (ref "PD56") (pin "3") (pinfunction "DIN_3") (pintype "input"))
    )
    (net (code "139") (name "Net-(PD56-DOUT)") (class "Default")
      (node (ref "PD56") (pin "1") (pinfunction "DOUT_1") (pintype "output"))
      (node (ref "PD57") (pin "3") (pinfunction "DIN_3") (pintype "input"))
    )
    (net (code "140") (name "Net-(PD57-DOUT)") (class "Default")
      (node (ref "PD57") (pin "1") (pinfunction "DOUT_1") (pintype "output"))
      (node (ref "PD58") (pin "3") (pinfunction "DIN_3") (pintype "input"))
    )
    (net (code "141") (name "Net-(PD58-DOUT)") (class "Default")
      (node (ref "PD58") (pin "1") (pinfunction "DOUT_1") (pintype "output"))
      (node (ref "PD59") (pin "3") (pinfunction "DIN_3") (pintype "input"))
    )
    (net (code "142") (name "Net-(PD59-DOUT)") (class "Default")
      (node (ref "PD59") (pin "1") (pinfunction "DOUT_1") (pintype "output"))
      (node (ref "PD60") (pin "3") (pinfunction "DIN_3") (pintype "input"))
    )
    (net (code "143") (name "Net-(PD60-DOUT)") (class "Default")
      (node (ref "PD60") (pin "1") (pinfunction "DOUT_1") (pintype "output"))
      (node (ref "PD61") (pin "3") (pinfunction "DIN_3") (pintype "input"))
    )
    (net (code "144") (name "Net-(PD61-DOUT)") (class "Default")
      (node (ref "PD61") (pin "1") (pinfunction "DOUT_1") (pintype "output"))
      (node (ref "PD62") (pin "3") (pinfunction "DIN_3") (pintype "input"))
    )
    (net (code "145") (name "Net-(PD62-DOUT)") (class "Default")
      (node (ref "PD62") (pin "1") (pinfunction "DOUT_1") (pintype "output"))
      (node (ref "PD63") (pin "3") (pinfunction "DIN_3") (pintype "input"))
    )
    (net (code "146") (name "Net-(PD63-DOUT)") (class "Default")
      (node (ref "PD63") (pin "1") (pinfunction "DOUT_1") (pintype "output"))
      (node (ref "PD64") (pin "3") (pinfunction "DIN_3") (pintype "input"))
    )
    (net (code "147") (name "Net-(PD64-DOUT)") (class "Default")
      (node (ref "PD64") (pin "1") (pinfunction "DOUT_1") (pintype "output"))
      (node (ref "PD65") (pin "3") (pinfunction "DIN_3") (pintype "input"))
    )
    (net (code "148") (name "Net-(PD65-DOUT)") (class "Default")
      (node (ref "PD65") (pin "1") (pinfunction "DOUT_1") (pintype "output"))
      (node (ref "PD66") (pin "3") (pinfunction "DIN_3") (pintype "input"))
    )
    (net (code "149") (name "Net-(PD66-DOUT)") (class "Default")
      (node (ref "PD66") (pin "1") (pinfunction "DOUT_1") (pintype "output"))
      (node (ref "PD67") (pin "3") (pinfunction "DIN_3") (pintype "input"))
    )
    (net (code "150") (name "Net-(PD67-DOUT)") (class "Default")
      (node (ref "PD67") (pin "1") (pinfunction "DOUT_1") (pintype "output"))
      (node (ref "PD68") (pin "3") (pinfunction "DIN_3") (pintype "input"))
    )
    (net (code "151") (name "Net-(PD68-DOUT)") (class "Default")
      (node (ref "PD68") (pin "1") (pinfunction "DOUT_1") (pintype "output"))
      (node (ref "PD69") (pin "3") (pinfunction "DIN_3") (pintype "input"))
    )
    (net (code "152") (name "Net-(PD69-DOUT)") (class "Default")
      (node (ref "PD69") (pin "1") (pinfunction "DOUT_1") (pintype "output"))
      (node (ref "PD70") (pin "3") (pinfunction "DIN_3") (pintype "input"))
    )
    (net (code "153") (name "Net-(PD70-DOUT)") (class "Default")
      (node (ref "PD70") (pin "1") (pinfunction "DOUT_1") (pintype "output"))
      (node (ref "PD71") (pin "3") (pinfunction "DIN_3") (pintype "input"))
    )
    (net (code "154") (name "Net-(PD71-DOUT)") (class "Default")
      (node (ref "PD71") (pin "1") (pinfunction "DOUT_1") (pintype "output"))
      (node (ref "PD72") (pin "3") (pinfunction "DIN_3") (pintype "input"))
    )
    (net (code "155") (name "Net-(PD72-DOUT)") (class "Default")
      (node (ref "PD72") (pin "1") (pinfunction "DOUT_1") (pintype "output"))
      (node (ref "PD73") (pin "3") (pinfunction "DIN_3") (pintype "input"))
    )
    (net (code "156") (name "Net-(PD73-DOUT)") (class "Default")
      (node (ref "PD73") (pin "1") (pinfunction "DOUT_1") (pintype "output"))
      (node (ref "PD74") (pin "3") (pinfunction "DIN_3") (pintype "input"))
    )
    (net (code "157") (name "Net-(PD74-DOUT)") (class "Default")
      (node (ref "PD74") (pin "1") (pinfunction "DOUT_1") (pintype "output"))
      (node (ref "PD75") (pin "3") (pinfunction "DIN_3") (pintype "input"))
    )
    (net (code "158") (name "Net-(PD75-DOUT)") (class "Default")
      (node (ref "PD75") (pin "1") (pinfunction "DOUT_1") (pintype "output"))
      (node (ref "PD76") (pin "3") (pinfunction "DIN_3") (pintype "input"))
    )
    (net (code "159") (name "Net-(PD76-DOUT)") (class "Default")
      (node (ref "PD76") (pin "1") (pinfunction "DOUT_1") (pintype "output"))
      (node (ref "PD77") (pin "3") (pinfunction "DIN_3") (pintype "input"))
    )
    (net (code "160") (name "Net-(PD77-DOUT)") (class "Default")
      (node (ref "PD77") (pin "1") (pinfunction "DOUT_1") (pintype "output"))
      (node (ref "PD78") (pin "3") (pinfunction "DIN_3") (pintype "input"))
    )
    (net (code "161") (name "Net-(PD78-DOUT)") (class "Default")
      (node (ref "PD78") (pin "1") (pinfunction "DOUT_1") (pintype "output"))
      (node (ref "PD79") (pin "3") (pinfunction "DIN_3") (pintype "input"))
    )
    (net (code "162") (name "Net-(PD79-DOUT)") (class "Default")
      (node (ref "PD79") (pin "1") (pinfunction "DOUT_1") (pintype "output"))
      (node (ref "PD80") (pin "3") (pinfunction "DIN_3") (pintype "input"))
    )
    (net (code "163") (name "Net-(PD80-DOUT)") (class "Default")
      (node (ref "PD80") (pin "1") (pinfunction "DOUT_1") (pintype "output"))
      (node (ref "PD81") (pin "3") (pinfunction "DIN_3") (pintype "input"))
    )
    (net (code "164") (name "Net-(PD81-DOUT)") (class "Default")
      (node (ref "PD81") (pin "1") (pinfunction "DOUT_1") (pintype "output"))
      (node (ref "PD82") (pin "3") (pinfunction "DIN_3") (pintype "input"))
    )
    (net (code "165") (name "Net-(PD82-DOUT)") (class "Default")
      (node (ref "PD82") (pin "1") (pinfunction "DOUT_1") (pintype "output"))
      (node (ref "PD83") (pin "3") (pinfunction "DIN_3") (pintype "input"))
    )
    (net (code "166") (name "Net-(PD83-DOUT)") (class "Default")
      (node (ref "PD83") (pin "1") (pinfunction "DOUT_1") (pintype "output"))
      (node (ref "PD84") (pin "3") (pinfunction "DIN_3") (pintype "input"))
    )
    (net (code "167") (name "Net-(PD84-DOUT)") (class "Default")
      (node (ref "PD84") (pin "1") (pinfunction "DOUT_1") (pintype "output"))
      (node (ref "PD85") (pin "3") (pinfunction "DIN_3") (pintype "input"))
    )
    (net (code "168") (name "Net-(PD85-DOUT)") (class "Default")
      (node (ref "PD85") (pin "1") (pinfunction "DOUT_1") (pintype "output"))
      (node (ref "PD86") (pin "3") (pinfunction "DIN_3") (pintype "input"))
    )
    (net (code "169") (name "Net-(PD86-DOUT)") (class "Default")
      (node (ref "PD86") (pin "1") (pinfunction "DOUT_1") (pintype "output"))
      (node (ref "PD87") (pin "3") (pinfunction "DIN_3") (pintype "input"))
    )
    (net (code "170") (name "Net-(PD87-DOUT)") (class "Default")
      (node (ref "PD87") (pin "1") (pinfunction "DOUT_1") (pintype "output"))
      (node (ref "PD88") (pin "3") (pinfunction "DIN_3") (pintype "input"))
    )
    (net (code "171") (name "Net-(PD88-DOUT)") (class "Default")
      (node (ref "PD88") (pin "1") (pinfunction "DOUT_1") (pintype "output"))
      (node (ref "PD89") (pin "3") (pinfunction "DIN_3") (pintype "input"))
    )
    (net (code "172") (name "Net-(PD89-DOUT)") (class "Default")
      (node (ref "PD89") (pin "1") (pinfunction "DOUT_1") (pintype "output"))
      (node (ref "PD90") (pin "3") (pinfunction "DIN_3") (pintype "input"))
    )
    (net (code "173") (name "Net-(PD90-DOUT)") (class "Default")
      (node (ref "PD90") (pin "1") (pinfunction "DOUT_1") (pintype "output"))
      (node (ref "PD91") (pin "3") (pinfunction "DIN_3") (pintype "input"))
    )
    (net (code "174") (name "Net-(PD91-DOUT)") (class "Default")
      (node (ref "PD91") (pin "1") (pinfunction "DOUT_1") (pintype "output"))
      (node (ref "PD92") (pin "3") (pinfunction "DIN_3") (pintype "input"))
    )
    (net (code "175") (name "Net-(PD92-DOUT)") (class "Default")
      (node (ref "PD92") (pin "1") (pinfunction "DOUT_1") (pintype "output"))
      (node (ref "PD93") (pin "3") (pinfunction "DIN_3") (pintype "input"))
    )
    (net (code "176") (name "Net-(PD93-DOUT)") (class "Default")
      (node (ref "PD93") (pin "1") (pinfunction "DOUT_1") (pintype "output"))
      (node (ref "PD94") (pin "3") (pinfunction "DIN_3") (pintype "input"))
    )
    (net (code "177") (name "Net-(PD94-DOUT)") (class "Default")
      (node (ref "PD94") (pin "1") (pinfunction "DOUT_1") (pintype "output"))
      (node (ref "PD95") (pin "3") (pinfunction "DIN_3") (pintype "input"))
    )
    (net (code "178") (name "Net-(PD95-DOUT)") (class "Default")
      (node (ref "PD95") (pin "1") (pinfunction "DOUT_1") (pintype "output"))
      (node (ref "PD96") (pin "3") (pinfunction "DIN_3") (pintype "input"))
    )
    (net (code "179") (name "Net-(PD96-DOUT)") (class "Default")
      (node (ref "PD96") (pin "1") (pinfunction "DOUT_1") (pintype "output"))
      (node (ref "PD97") (pin "3") (pinfunction "DIN_3") (pintype "input"))
    )
    (net (code "180") (name "Net-(PD97-DOUT)") (class "Default")
      (node (ref "PD97") (pin "1") (pinfunction "DOUT_1") (pintype "output"))
      (node (ref "PD98") (pin "3") (pinfunction "DIN_3") (pintype "input"))
    )
    (net (code "181") (name "Net-(PD98-DOUT)") (class "Default")
      (node (ref "PD98") (pin "1") (pinfunction "DOUT_1") (pintype "output"))
      (node (ref "PD99") (pin "3") (pinfunction "DIN_3") (pintype "input"))
    )
    (net (code "182") (name "Net-(PD100-DIN)") (class "Default")
      (node (ref "PD100") (pin "3") (pinfunction "DIN_3") (pintype "input"))
      (node (ref "PD99") (pin "1") (pinfunction "DOUT_1") (pintype "output"))
    )
    (net (code "183") (name "Net-(PD100-DOUT)") (class "Default")
      (node (ref "PD100") (pin "1") (pinfunction "DOUT_1") (pintype "output"))
      (node (ref "PD101") (pin "3") (pinfunction "DIN_3") (pintype "input"))
    )
    (net (code "184") (name "Net-(PD101-DOUT)") (class "Default")
      (node (ref "PD101") (pin "1") (pinfunction "DOUT_1") (pintype "output"))
      (node (ref "PD102") (pin "3") (pinfunction "DIN_3") (pintype "input"))
    )
    (net (code "185") (name "Net-(PD102-DOUT)") (class "Default")
      (node (ref "PD102") (pin "1") (pinfunction "DOUT_1") (pintype "output"))
      (node (ref "PD103") (pin "3") (pinfunction "DIN_3") (pintype "input"))
    )
    (net (code "186") (name "Net-(PD103-DOUT)") (class "Default")
      (node (ref "PD103") (pin "1") (pinfunction "DOUT_1") (pintype "output"))
      (node (ref "PD104") (pin "3") (pinfunction "DIN_3") (pintype "input"))
    )
    (net (code "187") (name "Net-(PD104-DOUT)") (class "Default")
      (node (ref "PD104") (pin "1") (pinfunction "DOUT_1") (pintype "output"))
      (node (ref "PD105") (pin "3") (pinfunction "DIN_3") (pintype "input"))
    )
    (net (code "188") (name "Net-(PD105-DOUT)") (class "Default")
      (node (ref "PD105") (pin "1") (pinfunction "DOUT_1") (pintype "output"))
      (node (ref "PD106") (pin "3") (pinfunction "DIN_3") (pintype "input"))
    )
    (net (code "189") (name "Net-(PD106-DOUT)") (class "Default")
      (node (ref "PD106") (pin "1") (pinfunction "DOUT_1") (pintype "output"))
      (node (ref "PD107") (pin "3") (pinfunction "DIN_3") (pintype "input"))
    )
    (net (code "190") (name "Net-(PD107-DOUT)") (class "Default")
      (node (ref "PD107") (pin "1") (pinfunction "DOUT_1") (pintype "output"))
      (node (ref "PD108") (pin "3") (pinfunction "DIN_3") (pintype "input"))
    )
    (net (code "191") (name "Net-(PD108-DOUT)") (class "Default")
      (node (ref "PD108") (pin "1") (pinfunction "DOUT_1") (pintype "output"))
      (node (ref "PD109") (pin "3") (pinfunction "DIN_3") (pintype "input"))
    )
    (net (code "192") (name "Net-(PD109-DOUT)") (class "Default")
      (node (ref "PD109") (pin "1") (pinfunction "DOUT_1") (pintype "output"))
      (node (ref "PD110") (pin "3") (pinfunction "DIN_3") (pintype "input"))
    )
    (net (code "193") (name "Net-(Q2-2)") (class "Default")
      (node (ref "C13") (pin "2") (pinfunction "2_2") (pintype "passive"))
      (node (ref "Q2") (pin "4") (pinfunction "2_4") (pintype "passive"))
      (node (ref "U3") (pin "3") (pinfunction "PC14-OSC32_IN_3") (pintype "input"))
    )
    (net (code "194") (name "Net-(R1-Pad2)") (class "Default")
      (node (ref "R1") (pin "2") (pinfunction "2_2") (pintype "passive"))
      (node (ref "U2") (pin "RX") (pinfunction "RX_RX") (pintype "bidirectional"))
    )
    (net (code "195") (name "Net-(R9-Pad2)") (class "Default")
      (node (ref "R9") (pin "2") (pinfunction "2_2") (pintype "passive"))
      (node (ref "T1") (pin "B") (pinfunction "B_B") (pintype "passive"))
    )
    (net (code "196") (name "Net-(R10-Pad2)") (class "Default")
      (node (ref "R10") (pin "2") (pinfunction "2_2") (pintype "passive"))
      (node (ref "T2") (pin "B") (pinfunction "B_B") (pintype "passive"))
    )
    (net (code "197") (name "Net-(R11-Pad2)") (class "Default")
      (node (ref "R11") (pin "2") (pinfunction "2_2") (pintype "passive"))
      (node (ref "T3") (pin "B") (pinfunction "B_B") (pintype "passive"))
    )
    (net (code "198") (name "Net-(R68-Pad1)") (class "Default")
      (node (ref "R68") (pin "1") (pinfunction "1_1") (pintype "passive"))
      (node (ref "R69") (pin "2") (pinfunction "2_2") (pintype "passive"))
    )
    (net (code "199") (name "Net-(R70-Pad1)") (class "Default")
      (node (ref "R70") (pin "1") (pinfunction "1_1") (pintype "passive"))
      (node (ref "R71") (pin "2") (pinfunction "2_2") (pintype "passive"))
    )
    (net (code "200") (name "Net-(U1-STB)") (class "Default")
      (node (ref "R2") (pin "2") (pinfunction "2_2") (pintype "passive"))
      (node (ref "U1") (pin "8") (pinfunction "STB_8") (pintype "bidirectional"))
    )
    (net (code "201") (name "Net-(U1-VCC)") (class "Default")
      (node (ref "C1") (pin "+") (pinfunction "+_+") (pintype "passive"))
      (node (ref "C2") (pin "2") (pinfunction "2_2") (pintype "passive"))
      (node (ref "L1") (pin "1") (pinfunction "1_1") (pintype "passive"))
      (node (ref "U1") (pin "3") (pinfunction "VCC_3") (pintype "bidirectional"))
    )
    (net (code "202") (name "Net-(U2-SPK_1)") (class "Default")
      (node (ref "P1") (pin "2") (pinfunction "2_2") (pintype "passive"))
      (node (ref "U2") (pin "SPK1") (pinfunction "SPK_1_SPK1") (pintype "bidirectional"))
    )
    (net (code "203") (name "Net-(U2-SPK_2)") (class "Default")
      (node (ref "P1") (pin "1") (pinfunction "1_1") (pintype "passive"))
      (node (ref "U2") (pin "SPK2") (pinfunction "SPK_2_SPK2") (pintype "bidirectional"))
    )
    (net (code "204") (name "Net-(U3-PC15-OSC32_OUT)") (class "Default")
      (node (ref "C14") (pin "2") (pinfunction "2_2") (pintype "passive"))
      (node (ref "Q2") (pin "1") (pinfunction "1_1") (pintype "passive"))
      (node (ref "U3") (pin "4") (pinfunction "PC15-OSC32_OUT_4") (pintype "output"))
    )
    (net (code "205") (name "Net-(U3-PD0_OSC_IN)") (class "Default")
      (node (ref "C11") (pin "2") (pinfunction "2_2") (pintype "passive"))
      (node (ref "Q1") (pin "1") (pinfunction "1_1") (pintype "passive"))
      (node (ref "U3") (pin "5") (pinfunction "PD0_OSC_IN_5") (pintype "input"))
    )
    (net (code "206") (name "Net-(U3-PD1_OSC_OUT)") (class "Default")
      (node (ref "R5") (pin "2") (pinfunction "2_2") (pintype "passive"))
      (node (ref "U3") (pin "6") (pinfunction "PD1_OSC_OUT_6") (pintype "output"))
    )
    (net (code "207") (name "Net-(U3-VBAT)") (class "Default")
      (node (ref "C7") (pin "+") (pinfunction "+_+") (pintype "passive"))
      (node (ref "C8") (pin "1") (pinfunction "1_1") (pintype "passive"))
      (node (ref "C9") (pin "1") (pinfunction "1_1") (pintype "passive"))
      (node (ref "L3") (pin "1") (pinfunction "1_1") (pintype "passive"))
      (node (ref "U3") (pin "1") (pinfunction "VBAT_1") (pintype "input"))
      (node (ref "U3") (pin "13") (pinfunction "VDDA_13") (pintype "power_in"))
      (node (ref "U3") (pin "19") (pinfunction "VDD_4_19") (pintype "power_in"))
      (node (ref "U3") (pin "32") (pinfunction "VDD_1_32") (pintype "power_in"))
      (node (ref "U3") (pin "48") (pinfunction "VDD_2_48") (pintype "power_in"))
      (node (ref "U3") (pin "64") (pinfunction "VDD_3_64") (pintype "power_in"))
    )
    (net (code "208") (name "Net-(U4-VIN)") (class "Default")
      (node (ref "C27") (pin "+") (pinfunction "+_+") (pintype "passive"))
      (node (ref "C28") (pin "1") (pinfunction "1_1") (pintype "passive"))
      (node (ref "C29") (pin "2") (pinfunction "2_2") (pintype "passive"))
      (node (ref "C30") (pin "2") (pinfunction "2_2") (pintype "passive"))
      (node (ref "C31") (pin "2") (pinfunction "2_2") (pintype "passive"))
      (node (ref "L4") (pin "2") (pinfunction "2_2") (pintype "passive"))
      (node (ref "U4") (pin "1") (pinfunction "VIN_1") (pintype "input"))
      (node (ref "U5") (pin "1") (pinfunction "VIN_1") (pintype "input"))
    )
    (net (code "209") (name "Net-(U6-NRST)") (class "Default")
      (node (ref "C39") (pin "2") (pinfunction "2_2") (pintype "passive"))
      (node (ref "JP3") (pin "5") (pinfunction "5_5") (pintype "passive"))
      (node (ref "R53") (pin "1") (pinfunction "1_1") (pintype "passive"))
      (node (ref "U6") (pin "4") (pinfunction "NRST_4") (pintype "bidirectional"))
    )
    (net (code "210") (name "Net-(U6-PA5)") (class "Default")
      (node (ref "U6") (pin "11") (pinfunction "PA5_11") (pintype "bidirectional"))
      (node (ref "U6") (pin "12") (pinfunction "PA6_12") (pintype "bidirectional"))
    )
    (net (code "211") (name "Net-(U6-PA7)") (class "Default")
      (node (ref "U6") (pin "13") (pinfunction "PA7_13") (pintype "bidirectional"))
      (node (ref "U6") (pin "2") (pinfunction "PF0/OSC_IN_2") (pintype "bidirectional"))
    )
    (net (code "212") (name "Net-(U6-PA9)") (class "Default")
      (node (ref "R54") (pin "2") (pinfunction "2_2") (pintype "passive"))
      (node (ref "U6") (pin "17") (pinfunction "PA9_17") (pintype "bidirectional"))
      (node (ref "U8") (pin "6") (pinfunction "SCL_6") (pintype "input"))
    )
    (net (code "213") (name "Net-(U6-PA10)") (class "Default")
      (node (ref "R58") (pin "1") (pinfunction "1_1") (pintype "passive"))
      (node (ref "U6") (pin "18") (pinfunction "PA10_18") (pintype "bidirectional"))
      (node (ref "U8") (pin "5") (pinfunction "SDA_5") (pintype "bidirectional"))
    )
    (net (code "214") (name "Net-(U6-PA13)") (class "Default")
      (node (ref "JP3") (pin "4") (pinfunction "4_4") (pintype "passive"))
      (node (ref "U6") (pin "19") (pinfunction "PA13_19") (pintype "bidirectional"))
    )
    (net (code "215") (name "Net-(U6-PA14)") (class "Default")
      (node (ref "JP3") (pin "2") (pinfunction "2_2") (pintype "passive"))
      (node (ref "U6") (pin "20") (pinfunction "PA14_20") (pintype "bidirectional"))
    )
    (net (code "216") (name "Net-(U6-VDD)") (class "Default")
      (node (ref "C37") (pin "2") (pinfunction "2_2") (pintype "passive"))
      (node (ref "C38") (pin "+") (pinfunction "+_+") (pintype "passive"))
      (node (ref "L5") (pin "2") (pinfunction "2_2") (pintype "passive"))
      (node (ref "U6") (pin "16") (pinfunction "VDD_16") (pintype "bidirectional"))
      (node (ref "U6") (pin "5") (pinfunction "VDDA_5") (pintype "bidirectional"))
    )
    (net (code "217") (name "Net-(U7-DIR)") (class "Default")
      (node (ref "R55") (pin "2") (pinfunction "2_2") (pintype "passive"))
      (node (ref "U7") (pin "5") (pinfunction "DIR_5") (pintype "input"))
    )
    (net (code "218") (name "Net-(U7-VCCA)") (class "Default")
      (node (ref "L7") (pin "2") (pinfunction "2_2") (pintype "passive"))
      (node (ref "R55") (pin "1") (pinfunction "1_1") (pintype "passive"))
      (node (ref "U7") (pin "1") (pinfunction "VCCA_1") (pintype "power_in"))
    )
    (net (code "219") (name "Net-(U7-VCCB)") (class "Default")
      (node (ref "L6") (pin "2") (pinfunction "2_2") (pintype "passive"))
      (node (ref "U7") (pin "6") (pinfunction "VCCB_6") (pintype "power_in"))
    )
    (net (code "220") (name "Net-(V1-+VOUT)") (class "Default")
      (node (ref "D4") (pin "A") (pinfunction "A_A") (pintype "passive"))
      (node (ref "V1") (pin "4") (pinfunction "+VOUT_4") (pintype "passive"))
    )
    (net (code "221") (name "Net-(X1-3)") (class "Default")
      (node (ref "X1") (pin "P$3") (pinfunction "3_P$3") (pintype "passive"))
      (node (ref "X2") (pin "P$3") (pinfunction "3_P$3") (pintype "passive"))
    )
    (net (code "222") (name "Net-(X3-3)") (class "Default")
      (node (ref "X3") (pin "P$3") (pinfunction "3_P$3") (pintype "passive"))
      (node (ref "X4") (pin "P$3") (pinfunction "3_P$3") (pintype "passive"))
    )
    (net (code "223") (name "Net-(X3-4)") (class "Default")
      (node (ref "X3") (pin "P$4") (pinfunction "4_P$4") (pintype "passive"))
      (node (ref "X4") (pin "P$4") (pinfunction "4_P$4") (pintype "passive"))
    )
    (net (code "224") (name "Net-(X6V-1)") (class "Default")
      (node (ref "L10") (pin "2") (pinfunction "2_2") (pintype "passive"))
      (node (ref "X6") (pin "29") (pinfunction "1_29") (pintype "passive"))
    )
    (net (code "225") (name "OLED_16X2_CLK") (class "Default")
      (node (ref "DISPLAY1") (pin "18") (pinfunction "D0_18") (pintype "bidirectional"))
      (node (ref "U3") (pin "34") (pinfunction "PB13_34") (pintype "bidirectional"))
    )
    (net (code "226") (name "OLED_16X2_DC") (class "Default")
      (node (ref "DISPLAY1") (pin "15") (pinfunction "D/C#_15") (pintype "bidirectional"))
      (node (ref "U3") (pin "35") (pinfunction "PB14_35") (pintype "bidirectional"))
    )
    (net (code "227") (name "OLED_16X2_MOSI") (class "Default")
      (node (ref "DISPLAY1") (pin "19") (pinfunction "D1_19") (pintype "bidirectional"))
      (node (ref "U3") (pin "36") (pinfunction "PB15_36") (pintype "bidirectional"))
    )
    (net (code "228") (name "OLED_16X2_RST") (class "Default")
      (node (ref "DISPLAY1") (pin "14") (pinfunction "RES#_14") (pintype "bidirectional"))
      (node (ref "U3") (pin "33") (pinfunction "PB12_33") (pintype "bidirectional"))
    )
    (net (code "229") (name "OLED_BIG_CLK") (class "Default")
      (node (ref "U3") (pin "55") (pinfunction "PB3_55") (pintype "bidirectional"))
      (node (ref "X6") (pin "19") (pinfunction "1_19") (pintype "passive"))
    )
    (net (code "230") (name "OLED_BIG_CS") (class "Default")
      (node (ref "U3") (pin "51") (pinfunction "PC10_51") (pintype "bidirectional"))
      (node (ref "X6") (pin "14") (pinfunction "1_14") (pintype "passive"))
    )
    (net (code "231") (name "OLED_BIG_DC") (class "Default")
      (node (ref "U3") (pin "54") (pinfunction "PD2_54") (pintype "bidirectional"))
      (node (ref "X6") (pin "16") (pinfunction "1_16") (pintype "passive"))
    )
    (net (code "232") (name "OLED_BIG_MOSI") (class "Default")
      (node (ref "U3") (pin "57") (pinfunction "PB5_57") (pintype "bidirectional"))
      (node (ref "X6") (pin "20") (pinfunction "1_20") (pintype "passive"))
    )
    (net (code "233") (name "OLED_BIG_RES") (class "Default")
      (node (ref "U3") (pin "53") (pinfunction "PC12_53") (pintype "bidirectional"))
      (node (ref "X6") (pin "15") (pinfunction "1_15") (pintype "passive"))
    )
    (net (code "234") (name "PLAYER_RX") (class "Default")
      (node (ref "R1") (pin "1") (pinfunction "1_1") (pintype "passive"))
      (node (ref "U3") (pin "16") (pinfunction "PA2_16") (pintype "bidirectional"))
    )
    (net (code "235") (name "PLAYER_TX") (class "Default")
      (node (ref "U2") (pin "TX") (pinfunction "TX_TX") (pintype "bidirectional"))
      (node (ref "U3") (pin "17") (pinfunction "PA3_17") (pintype "bidirectional"))
    )
    (net (code "236") (name "SCL_OLED1") (class "Default")
      (node (ref "IC1") (pin "5") (pinfunction "SC0_5") (pintype "bidirectional"))
      (node (ref "P4") (pin "3") (pinfunction "3_3") (pintype "passive"))
      (node (ref "R60") (pin "1") (pinfunction "1_1") (pintype "passive"))
      (node (ref "U11") (pin "3") (pinfunction "SCL_3") (pintype "bidirectional"))
    )
    (net (code "237") (name "SCL_OLED2") (class "Default")
      (node (ref "IC1") (pin "7") (pinfunction "SC1_7") (pintype "bidirectional"))
      (node (ref "P3") (pin "3") (pinfunction "3_3") (pintype "passive"))
      (node (ref "R62") (pin "1") (pinfunction "1_1") (pintype "passive"))
      (node (ref "U10") (pin "3") (pinfunction "SCL_3") (pintype "bidirectional"))
    )
    (net (code "238") (name "SCL_OLED3") (class "Default")
      (node (ref "IC1") (pin "9") (pinfunction "SC2_9") (pintype "bidirectional"))
      (node (ref "P2") (pin "3") (pinfunction "3_3") (pintype "passive"))
      (node (ref "R64") (pin "1") (pinfunction "1_1") (pintype "passive"))
      (node (ref "U9") (pin "3") (pinfunction "SCL_3") (pintype "bidirectional"))
    )
    (net (code "239") (name "SDA_OLED1") (class "Default")
      (node (ref "IC1") (pin "4") (pinfunction "SD0_4") (pintype "bidirectional"))
      (node (ref "P4") (pin "4") (pinfunction "4_4") (pintype "passive"))
      (node (ref "R59") (pin "1") (pinfunction "1_1") (pintype "passive"))
      (node (ref "U11") (pin "4") (pinfunction "SDA_4") (pintype "bidirectional"))
    )
    (net (code "240") (name "SDA_OLED2") (class "Default")
      (node (ref "IC1") (pin "6") (pinfunction "SD1_6") (pintype "bidirectional"))
      (node (ref "P3") (pin "4") (pinfunction "4_4") (pintype "passive"))
      (node (ref "R61") (pin "1") (pinfunction "1_1") (pintype "passive"))
      (node (ref "U10") (pin "4") (pinfunction "SDA_4") (pintype "bidirectional"))
    )
    (net (code "241") (name "SDA_OLED3") (class "Default")
      (node (ref "IC1") (pin "8") (pinfunction "SD2_8") (pintype "bidirectional"))
      (node (ref "P2") (pin "4") (pinfunction "4_4") (pintype "passive"))
      (node (ref "R63") (pin "1") (pinfunction "1_1") (pintype "passive"))
      (node (ref "U9") (pin "4") (pinfunction "SDA_4") (pintype "bidirectional"))
    )
    (net (code "242") (name "SWCLK") (class "Default")
      (node (ref "JP1") (pin "2") (pinfunction "2_2") (pintype "passive"))
      (node (ref "U3") (pin "49") (pinfunction "PA14_49") (pintype "bidirectional"))
    )
    (net (code "243") (name "SWDIO") (class "Default")
      (node (ref "JP1") (pin "4") (pinfunction "4_4") (pintype "passive"))
      (node (ref "U3") (pin "46") (pinfunction "PA13_46") (pintype "bidirectional"))
    )
    (net (code "244") (name "VCOMH") (class "Default")
      (node (ref "C45") (pin "2") (pinfunction "2_2") (pintype "passive"))
      (node (ref "X6") (pin "28") (pinfunction "1_28") (pintype "passive"))
    )
    (net (code "245") (name "VDD") (class "Default")
      (node (ref "V2") (pin "C") (pinfunction "C_C") (pintype "passive"))
      (node (ref "X6") (pin "10") (pinfunction "1_10") (pintype "passive"))
    )
    (net (code "246") (name "unconnected-(DISPLAY1-GPIO-Pad12)") (class "Default")
      (node (ref "DISPLAY1") (pin "12") (pinfunction "GPIO_12") (pintype "bidirectional"))
    )
    (net (code "247") (name "unconnected-(DISPLAY1-NC1-Pad1)") (class "Default")
      (node (ref "DISPLAY1") (pin "1") (pinfunction "NC1_1") (pintype "bidirectional"))
    )
    (net (code "248") (name "unconnected-(DISPLAY1-NC2-Pad33)") (class "Default")
      (node (ref "DISPLAY1") (pin "33") (pinfunction "NC2_33") (pintype "bidirectional"))
    )
    (net (code "249") (name "unconnected-(DISPLAY1-VSL-Pad2)") (class "Default")
      (node (ref "DISPLAY1") (pin "2") (pinfunction "VSL_2") (pintype "bidirectional"))
    )
    (net (code "250") (name "unconnected-(IC1-SC3-Pad11)") (class "Default")
      (node (ref "IC1") (pin "11") (pinfunction "SC3_11") (pintype "bidirectional"))
    )
    (net (code "251") (name "unconnected-(IC1-SC4-Pad14)") (class "Default")
      (node (ref "IC1") (pin "14") (pinfunction "SC4_14") (pintype "bidirectional"))
    )
    (net (code "252") (name "unconnected-(IC1-SC5-Pad16)") (class "Default")
      (node (ref "IC1") (pin "16") (pinfunction "SC5_16") (pintype "bidirectional"))
    )
    (net (code "253") (name "unconnected-(IC1-SC6-Pad18)") (class "Default")
      (node (ref "IC1") (pin "18") (pinfunction "SC6_18") (pintype "bidirectional"))
    )
    (net (code "254") (name "unconnected-(IC1-SC7-Pad20)") (class "Default")
      (node (ref "IC1") (pin "20") (pinfunction "SC7_20") (pintype "bidirectional"))
    )
    (net (code "255") (name "unconnected-(IC1-SD3-Pad10)") (class "Default")
      (node (ref "IC1") (pin "10") (pinfunction "SD3_10") (pintype "bidirectional"))
    )
    (net (code "256") (name "unconnected-(IC1-SD4-Pad13)") (class "Default")
      (node (ref "IC1") (pin "13") (pinfunction "SD4_13") (pintype "bidirectional"))
    )
    (net (code "257") (name "unconnected-(IC1-SD5-Pad15)") (class "Default")
      (node (ref "IC1") (pin "15") (pinfunction "SD5_15") (pintype "bidirectional"))
    )
    (net (code "258") (name "unconnected-(IC1-SD6-Pad17)") (class "Default")
      (node (ref "IC1") (pin "17") (pinfunction "SD6_17") (pintype "bidirectional"))
    )
    (net (code "259") (name "unconnected-(IC1-SD7-Pad19)") (class "Default")
      (node (ref "IC1") (pin "19") (pinfunction "SD7_19") (pintype "bidirectional"))
    )
    (net (code "260") (name "unconnected-(JP1-Pad6)") (class "Default")
      (node (ref "JP1") (pin "6") (pinfunction "6_6") (pintype "passive"))
    )
    (net (code "261") (name "unconnected-(JP3-Pad6)") (class "Default")
      (node (ref "JP3") (pin "6") (pinfunction "6_6") (pintype "passive"))
    )
    (net (code "262") (name "unconnected-(PD110-DOUT-Pad1)") (class "Default")
      (node (ref "PD110") (pin "1") (pinfunction "DOUT_1") (pintype "output"))
    )
    (net (code "263") (name "unconnected-(U2-ADKEY_1-PadADKEY1)") (class "Default")
      (node (ref "U2") (pin "ADKEY1") (pinfunction "ADKEY_1_ADKEY1") (pintype "bidirectional"))
    )
    (net (code "264") (name "unconnected-(U2-ADKEY_2-PadADKEY2)") (class "Default")
      (node (ref "U2") (pin "ADKEY2") (pinfunction "ADKEY_2_ADKEY2") (pintype "bidirectional"))
    )
    (net (code "265") (name "unconnected-(U2-IO_1-PadIO1)") (class "Default")
      (node (ref "U2") (pin "IO1") (pinfunction "IO_1_IO1") (pintype "bidirectional"))
    )
    (net (code "266") (name "unconnected-(U2-IO_2-PadIO2)") (class "Default")
      (node (ref "U2") (pin "IO2") (pinfunction "IO_2_IO2") (pintype "bidirectional"))
    )
    (net (code "267") (name "unconnected-(U2-PadBUSY)") (class "Default")
      (node (ref "U2") (pin "BUSY") (pinfunction "BUSY_BUSY") (pintype "bidirectional"))
    )
    (net (code "268") (name "unconnected-(U2-PadDAC_L)") (class "Default")
      (node (ref "U2") (pin "DAC_L") (pinfunction "DAC_L_DAC_L") (pintype "bidirectional"))
    )
    (net (code "269") (name "unconnected-(U2-PadDAC_R)") (class "Default")
      (node (ref "U2") (pin "DAC_R") (pinfunction "DAC_R_DAC_R") (pintype "bidirectional"))
    )
    (net (code "270") (name "unconnected-(U2-PadUSB+)") (class "Default")
      (node (ref "U2") (pin "USB+") (pinfunction "USB+_USB+") (pintype "bidirectional"))
    )
    (net (code "271") (name "unconnected-(U2-PadUSB-)") (class "Default")
      (node (ref "U2") (pin "USB-") (pinfunction "USB-_USB-") (pintype "bidirectional"))
    )
    (net (code "272") (name "unconnected-(U3-PA0-WKUP-Pad14)") (class "Default")
      (node (ref "U3") (pin "14") (pinfunction "PA0-WKUP_14") (pintype "bidirectional"))
    )
    (net (code "273") (name "unconnected-(U3-PA1-Pad15)") (class "Default")
      (node (ref "U3") (pin "15") (pinfunction "PA1_15") (pintype "bidirectional"))
    )
    (net (code "274") (name "unconnected-(U3-PA4-Pad20)") (class "Default")
      (node (ref "U3") (pin "20") (pinfunction "PA4_20") (pintype "bidirectional"))
    )
    (net (code "275") (name "unconnected-(U3-PA5-Pad21)") (class "Default")
      (node (ref "U3") (pin "21") (pinfunction "PA5_21") (pintype "bidirectional"))
    )
    (net (code "276") (name "unconnected-(U3-PA8-Pad41)") (class "Default")
      (node (ref "U3") (pin "41") (pinfunction "PA8_41") (pintype "bidirectional"))
    )
    (net (code "277") (name "unconnected-(U3-PB1-Pad27)") (class "Default")
      (node (ref "U3") (pin "27") (pinfunction "PB1_27") (pintype "bidirectional"))
    )
    (net (code "278") (name "unconnected-(U3-PB4-Pad56)") (class "Default")
      (node (ref "U3") (pin "56") (pinfunction "PB4_56") (pintype "bidirectional"))
    )
    (net (code "279") (name "unconnected-(U3-PC0-Pad8)") (class "Default")
      (node (ref "U3") (pin "8") (pinfunction "PC0_8") (pintype "bidirectional"))
    )
    (net (code "280") (name "unconnected-(U3-PC1-Pad9)") (class "Default")
      (node (ref "U3") (pin "9") (pinfunction "PC1_9") (pintype "bidirectional"))
    )
    (net (code "281") (name "unconnected-(U3-PC2-Pad10)") (class "Default")
      (node (ref "U3") (pin "10") (pinfunction "PC2_10") (pintype "bidirectional"))
    )
    (net (code "282") (name "unconnected-(U3-PC3-Pad11)") (class "Default")
      (node (ref "U3") (pin "11") (pinfunction "PC3_11") (pintype "bidirectional"))
    )
    (net (code "283") (name "unconnected-(U3-PC4-Pad24)") (class "Default")
      (node (ref "U3") (pin "24") (pinfunction "PC4_24") (pintype "passive"))
    )
    (net (code "284") (name "unconnected-(U3-PC5-Pad25)") (class "Default")
      (node (ref "U3") (pin "25") (pinfunction "PC5_25") (pintype "bidirectional"))
    )
    (net (code "285") (name "unconnected-(U3-PC6-Pad37)") (class "Default")
      (node (ref "U3") (pin "37") (pinfunction "PC6_37") (pintype "bidirectional"))
    )
    (net (code "286") (name "unconnected-(U3-PC7-Pad38)") (class "Default")
      (node (ref "U3") (pin "38") (pinfunction "PC7_38") (pintype "bidirectional"))
    )
    (net (code "287") (name "unconnected-(U3-PC8-Pad39)") (class "Default")
      (node (ref "U3") (pin "39") (pinfunction "PC8_39") (pintype "bidirectional"))
    )
    (net (code "288") (name "unconnected-(U3-PC9-Pad40)") (class "Default")
      (node (ref "U3") (pin "40") (pinfunction "PC9_40") (pintype "bidirectional"))
    )
    (net (code "289") (name "unconnected-(U3-PC11-Pad52)") (class "Default")
      (node (ref "U3") (pin "52") (pinfunction "PC11_52") (pintype "bidirectional"))
    )
    (net (code "290") (name "unconnected-(U3-PC13-TAMPER-RTC-Pad2)") (class "Default")
      (node (ref "U3") (pin "2") (pinfunction "PC13-TAMPER-RTC_2") (pintype "input"))
    )
    (net (code "291") (name "unconnected-(U6-PA0-Pad6)") (class "Default")
      (node (ref "U6") (pin "6") (pinfunction "PA0_6") (pintype "bidirectional"))
    )
    (net (code "292") (name "unconnected-(U6-PA1-Pad7)") (class "Default")
      (node (ref "U6") (pin "7") (pinfunction "PA1_7") (pintype "bidirectional"))
    )
    (net (code "293") (name "unconnected-(U6-PA4-Pad10)") (class "Default")
      (node (ref "U6") (pin "10") (pinfunction "PA4_10") (pintype "bidirectional"))
    )
    (net (code "294") (name "unconnected-(U6-PF1{slash}OSC_OUT-Pad3)") (class "Default")
      (node (ref "U6") (pin "3") (pinfunction "PF1/OSC_OUT_3") (pintype "bidirectional"))
    )
    (net (code "295") (name "unconnected-(X6-Pad1)") (class "Default")
      (node (ref "X6") (pin "1") (pinfunction "1_1") (pintype "passive"))
    )
    (net (code "296") (name "unconnected-(X6AA-1-Pad6)") (class "Default")
      (node (ref "X6") (pin "6") (pinfunction "1_6") (pintype "passive"))
    )
    (net (code "297") (name "unconnected-(X6AB-1-Pad7)") (class "Default")
      (node (ref "X6") (pin "7") (pinfunction "1_7") (pintype "passive"))
    )
    (net (code "298") (name "unconnected-(X6AC-1-Pad8)") (class "Default")
      (node (ref "X6") (pin "8") (pinfunction "1_8") (pintype "passive"))
    )
    (net (code "299") (name "unconnected-(X6AD-1-Pad9)") (class "Default")
      (node (ref "X6") (pin "9") (pinfunction "1_9") (pintype "passive"))
    )
    (net (code "300") (name "unconnected-(X6E-1-Pad13)") (class "Default")
      (node (ref "X6") (pin "13") (pinfunction "1_13") (pintype "passive"))
    )
    (net (code "301") (name "unconnected-(X6N-1-Pad21)") (class "Default")
      (node (ref "X6") (pin "21") (pinfunction "1_21") (pintype "passive"))
    )
    (net (code "302") (name "unconnected-(X6O-1-Pad22)") (class "Default")
      (node (ref "X6") (pin "22") (pinfunction "1_22") (pintype "passive"))
    )
    (net (code "303") (name "unconnected-(X6P-1-Pad23)") (class "Default")
      (node (ref "X6") (pin "23") (pinfunction "1_23") (pintype "passive"))
    )
    (net (code "304") (name "unconnected-(X6Q-1-Pad24)") (class "Default")
      (node (ref "X6") (pin "24") (pinfunction "1_24") (pintype "passive"))
    )
    (net (code "305") (name "unconnected-(X6R-1-Pad25)") (class "Default")
      (node (ref "X6") (pin "25") (pinfunction "1_25") (pintype "passive"))
    )
    (net (code "306") (name "unconnected-(X6S-1-Pad26)") (class "Default")
      (node (ref "X6") (pin "26") (pinfunction "1_26") (pintype "passive"))
    )
    (net (code "307") (name "unconnected-(X6W-1-Pad3)") (class "Default")
      (node (ref "X6") (pin "3") (pinfunction "1_3") (pintype "passive"))
    )
    (net (code "308") (name "unconnected-(X6X-1-Pad30)") (class "Default")
      (node (ref "X6") (pin "30") (pinfunction "1_30") (pintype "passive"))
    )
    (net (code "309") (name "unconnected-(X6Y-1-Pad4)") (class "Default")
      (node (ref "X6") (pin "4") (pinfunction "1_4") (pintype "passive"))
    )
    (net (code "310") (name "unconnected-(X6Z-1-Pad5)") (class "Default")
      (node (ref "X6") (pin "5") (pinfunction "1_5") (pintype "passive"))
    )
  )
)
